# cw-lite-main.net
KiCad netlist of a schematic drawn in EAGLE
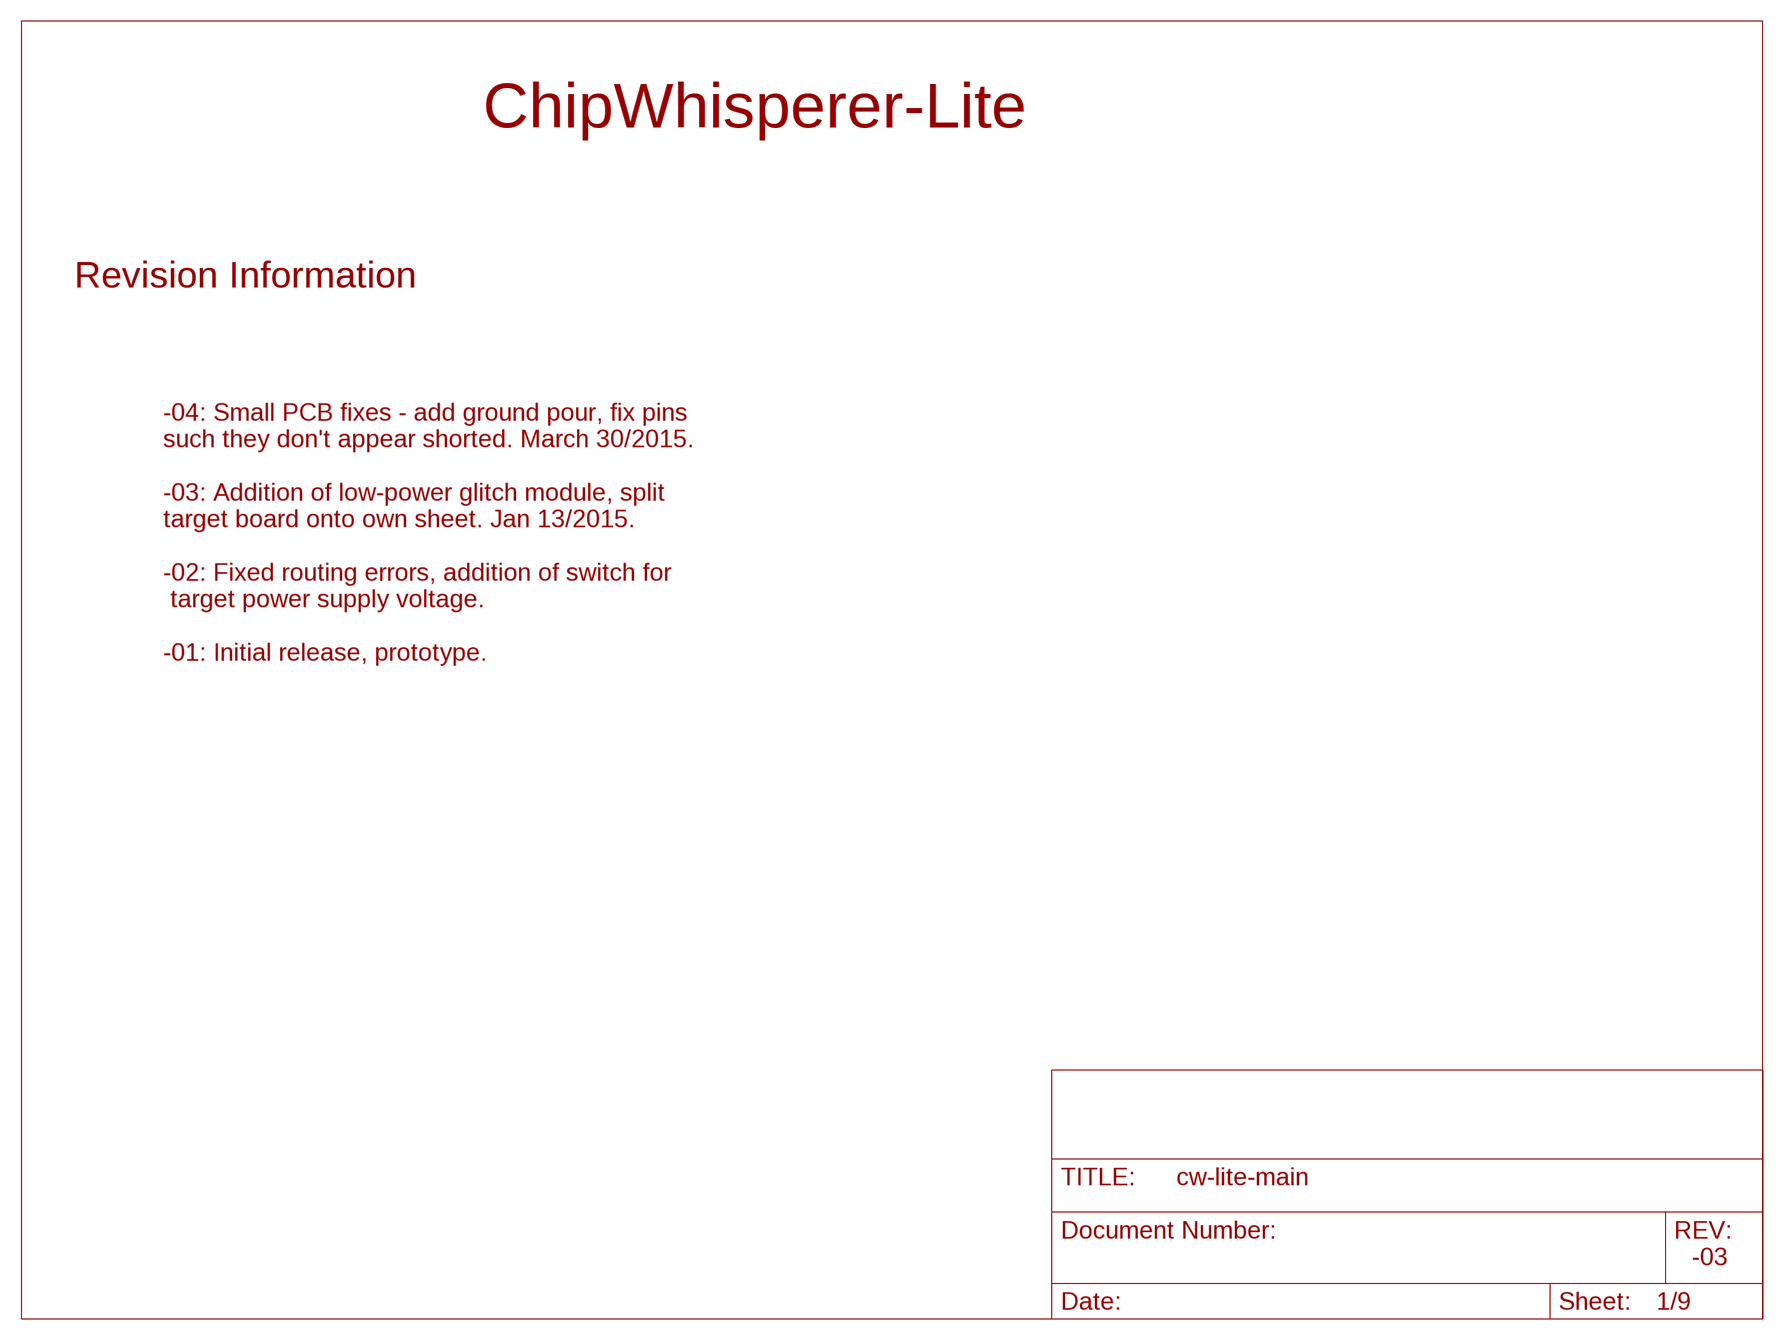
[diagram p0: schematic, sheet 1]
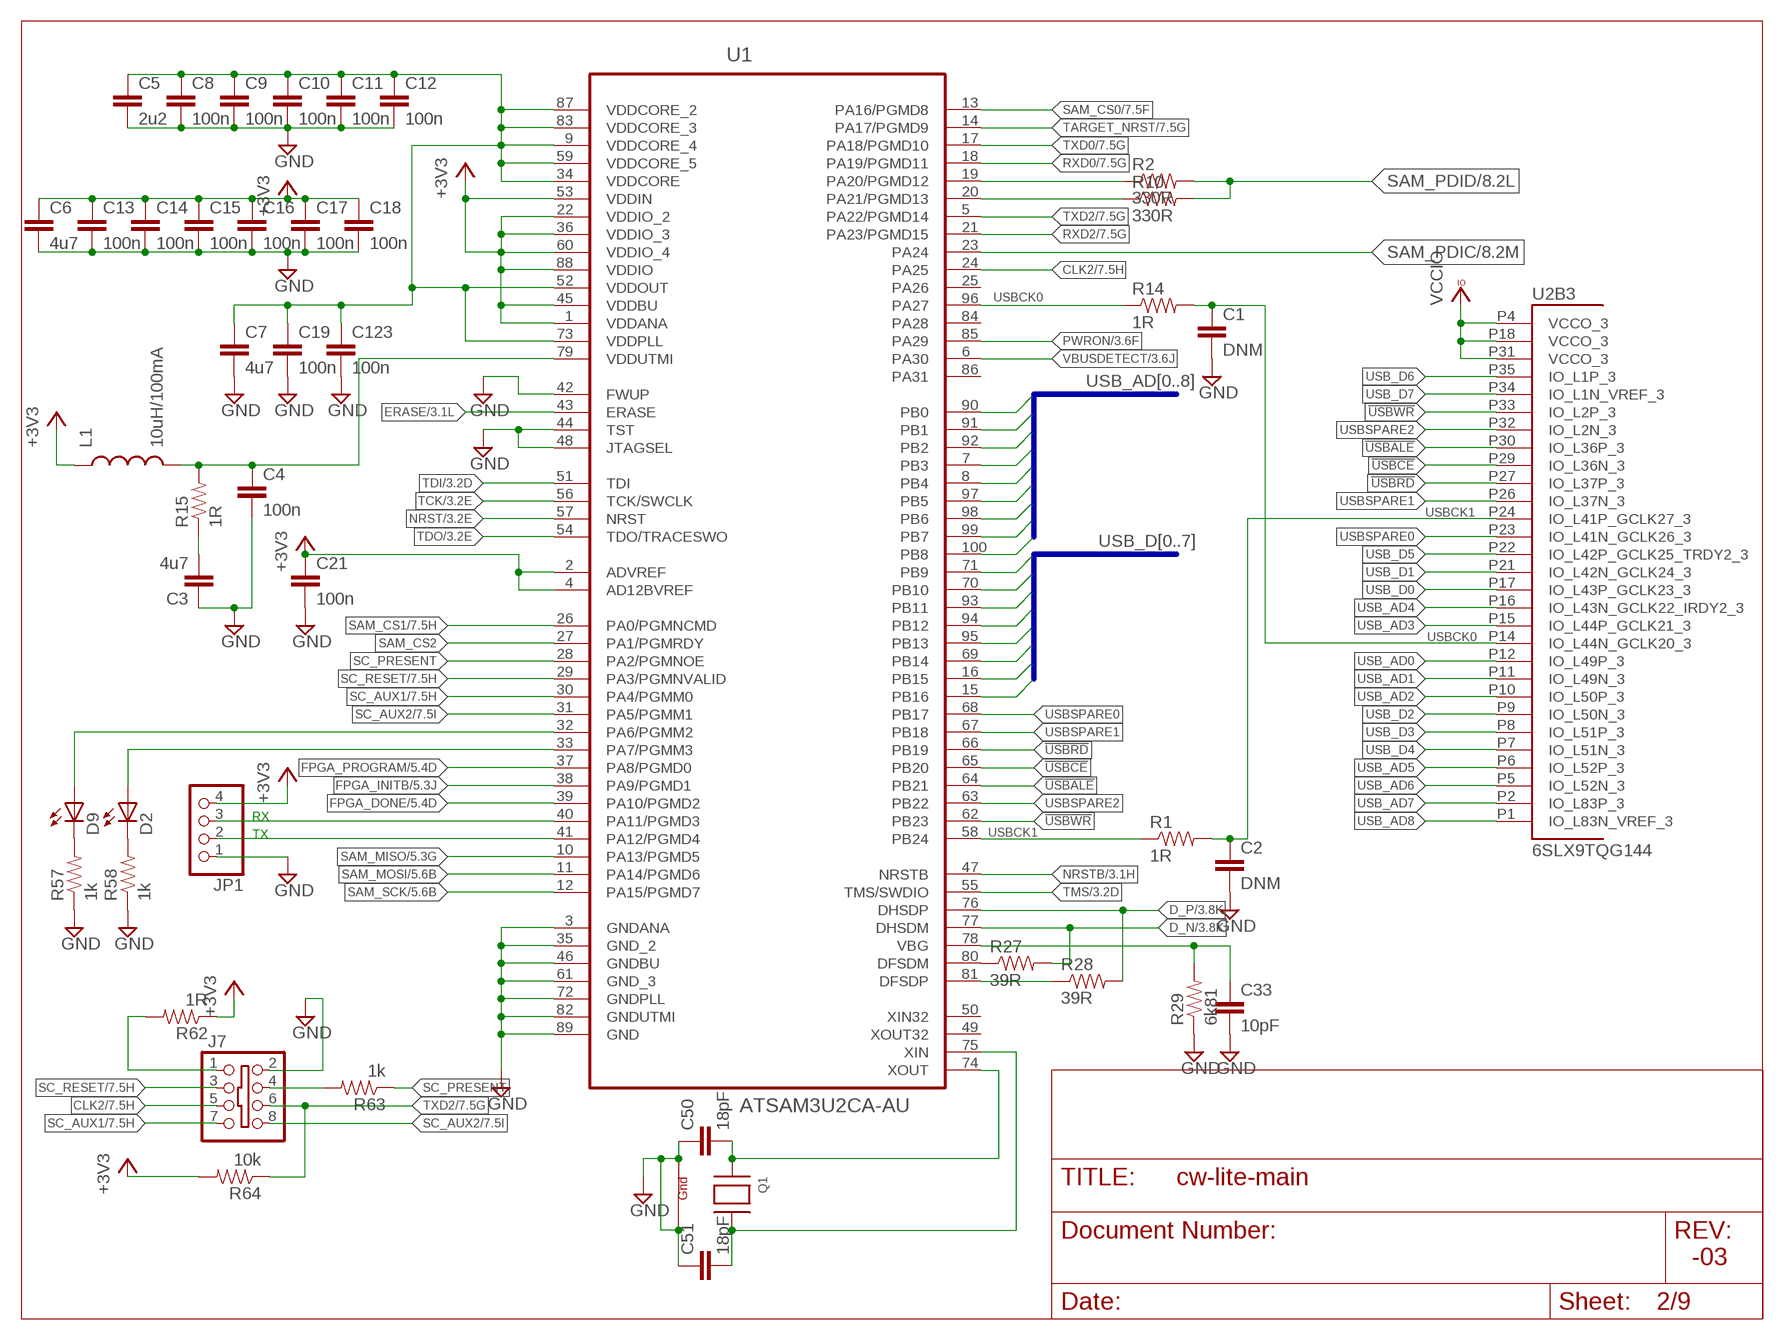
[diagram p1: schematic, sheet 2]
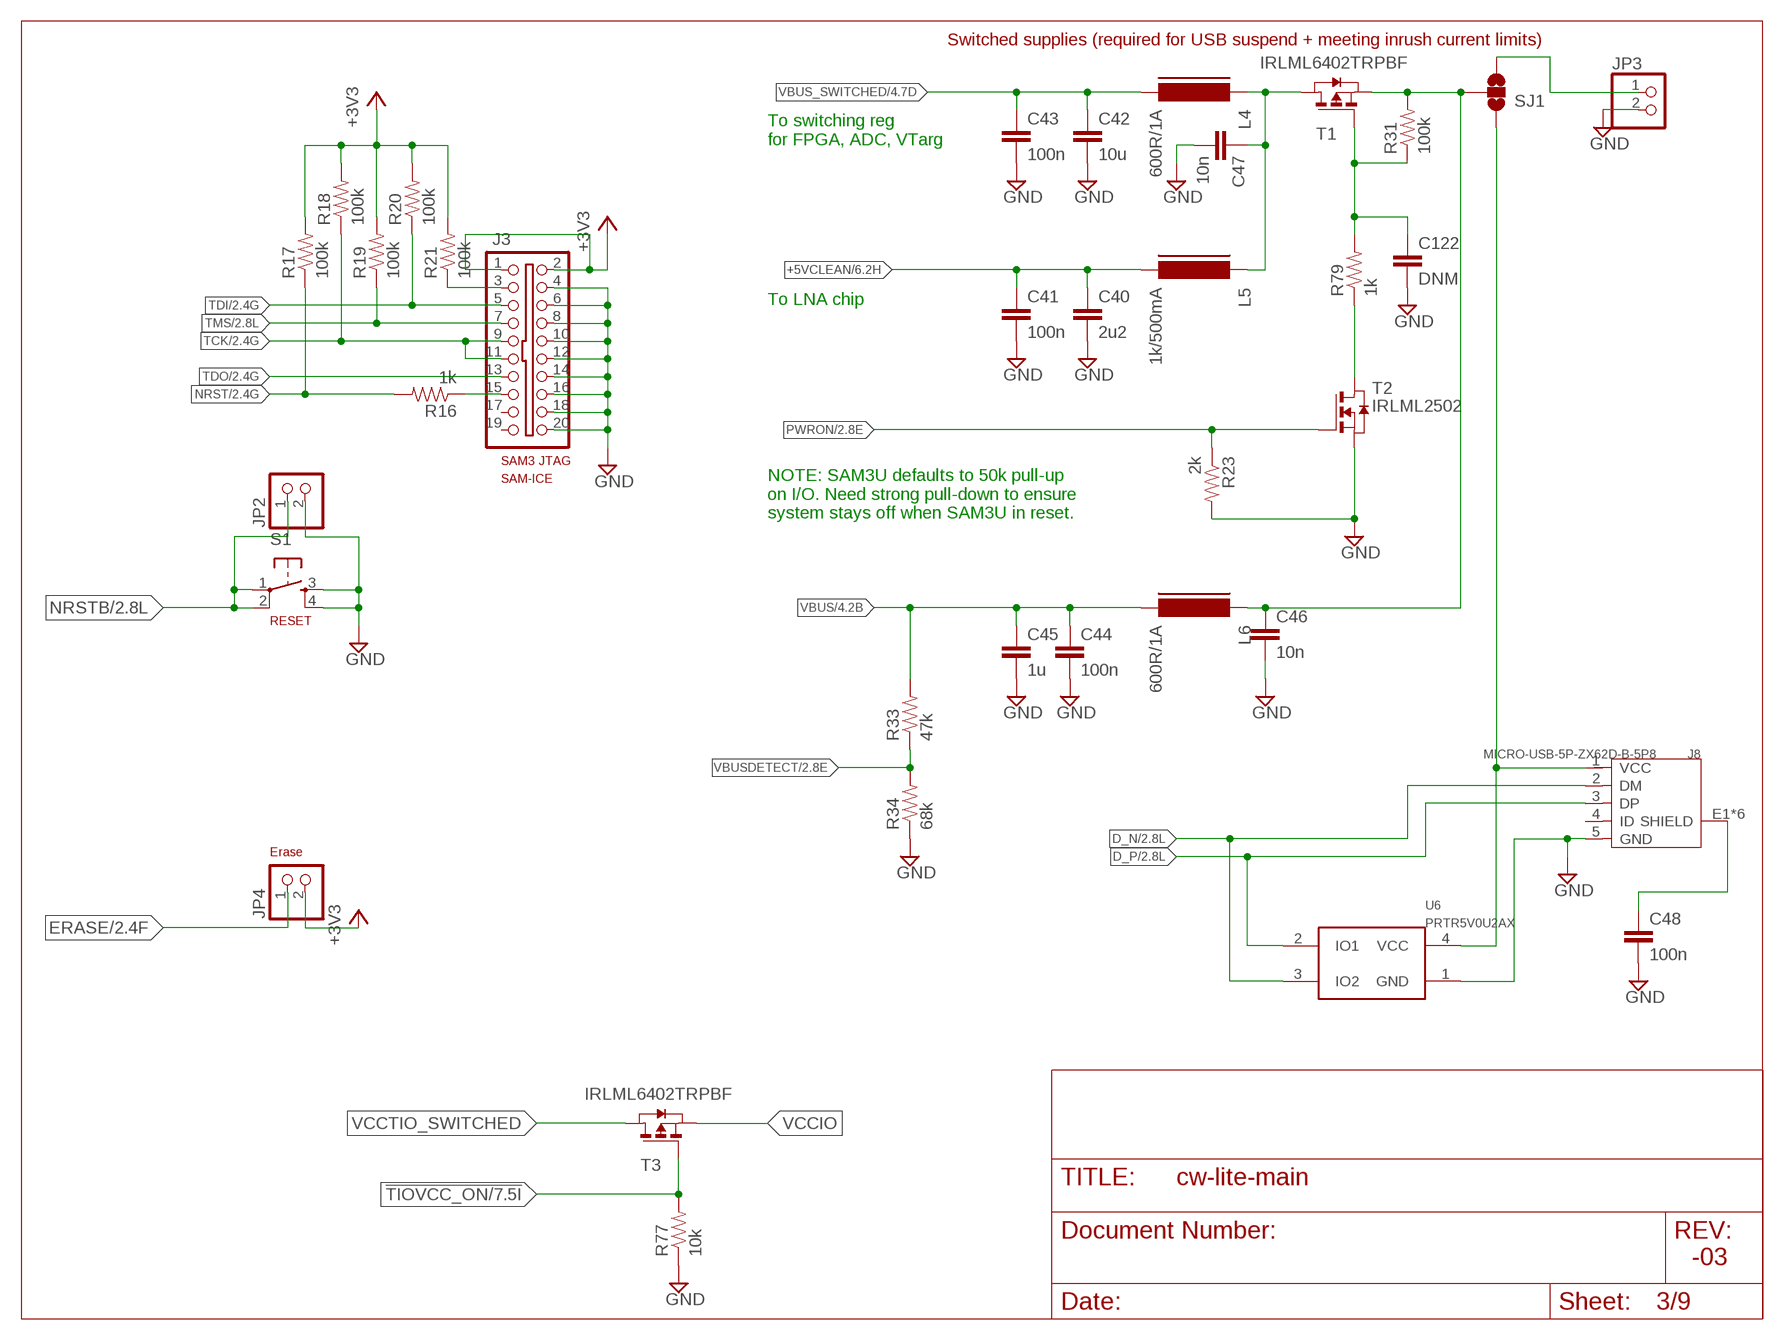
[diagram p2: schematic, sheet 3]
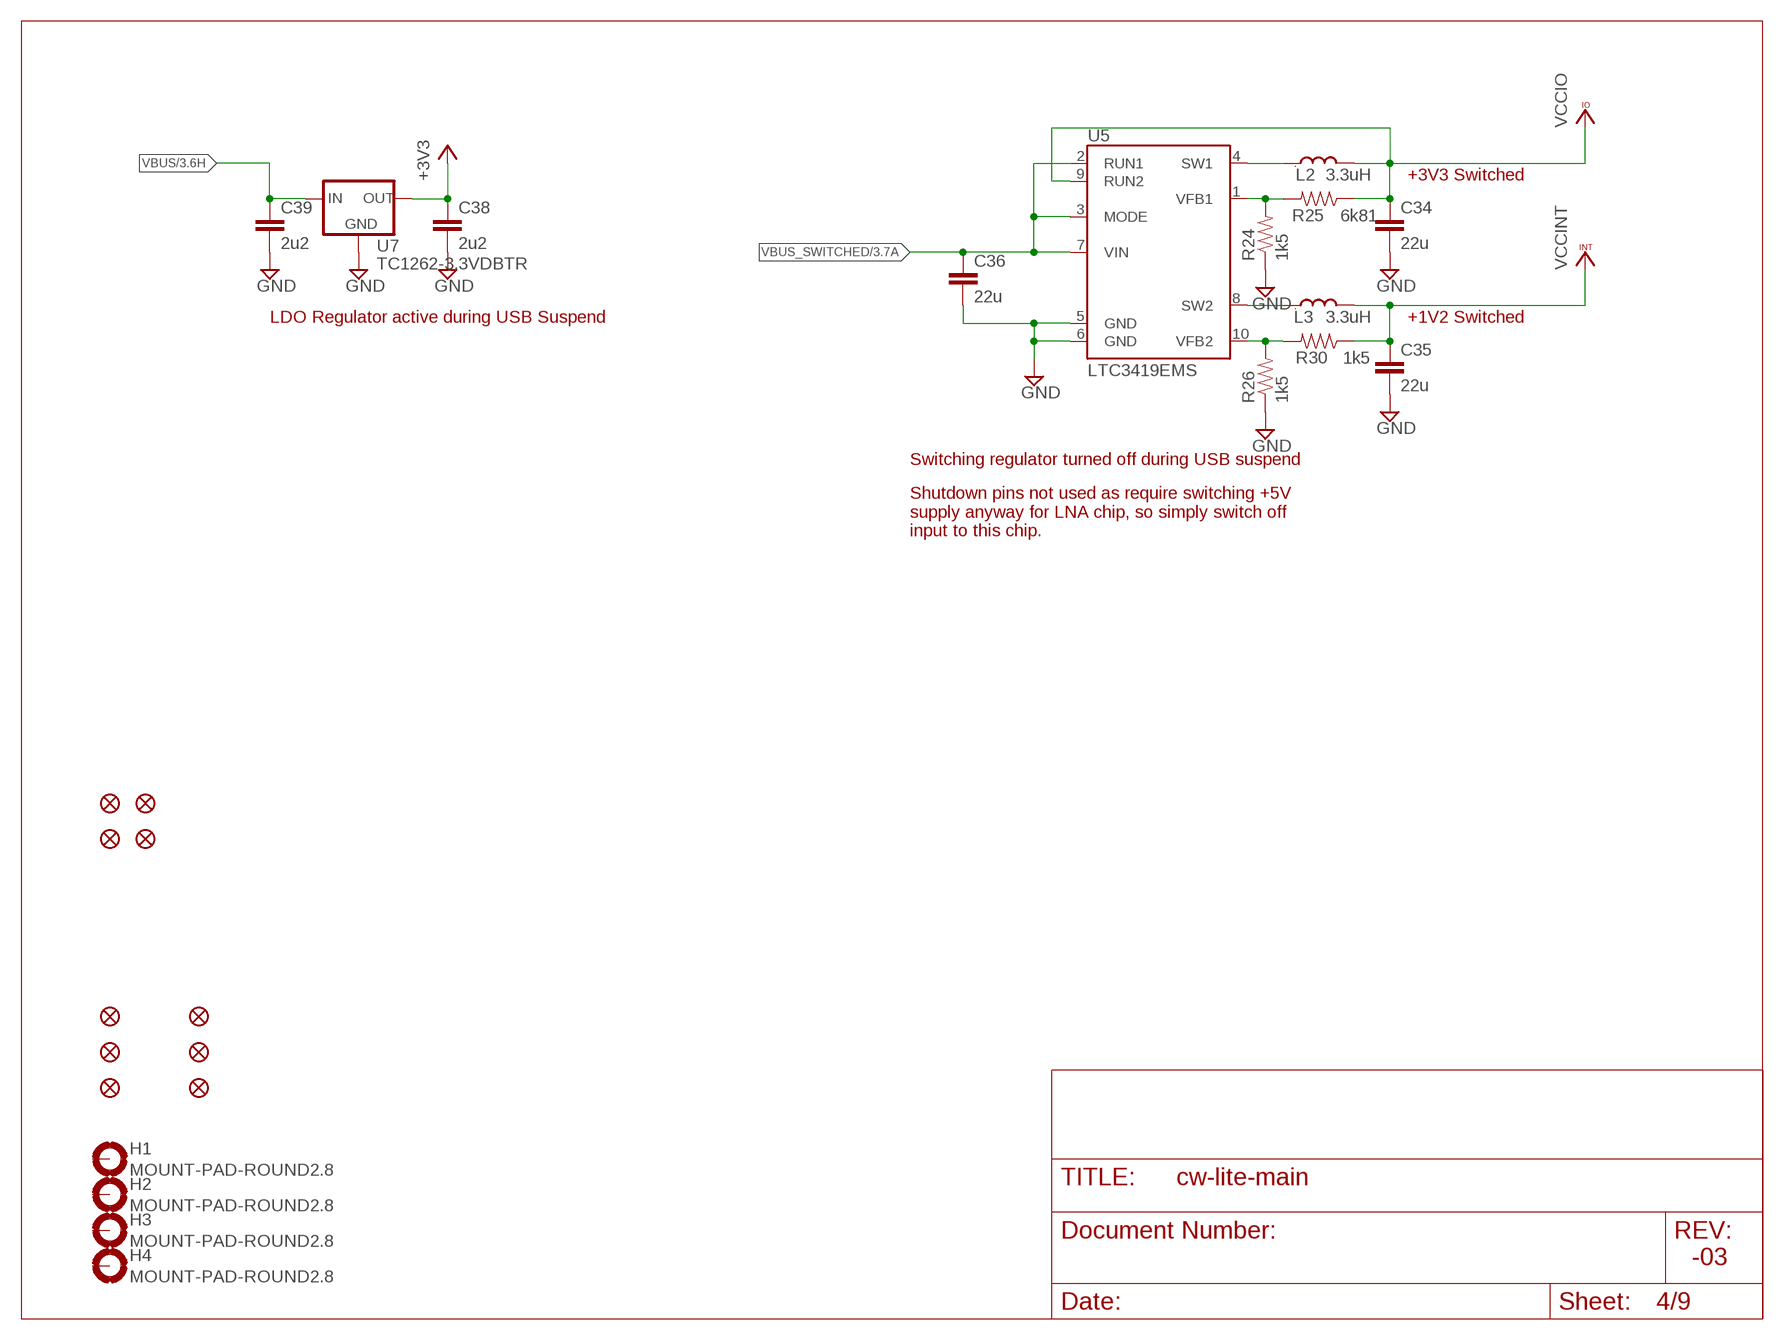
[diagram p3: schematic, sheet 4]
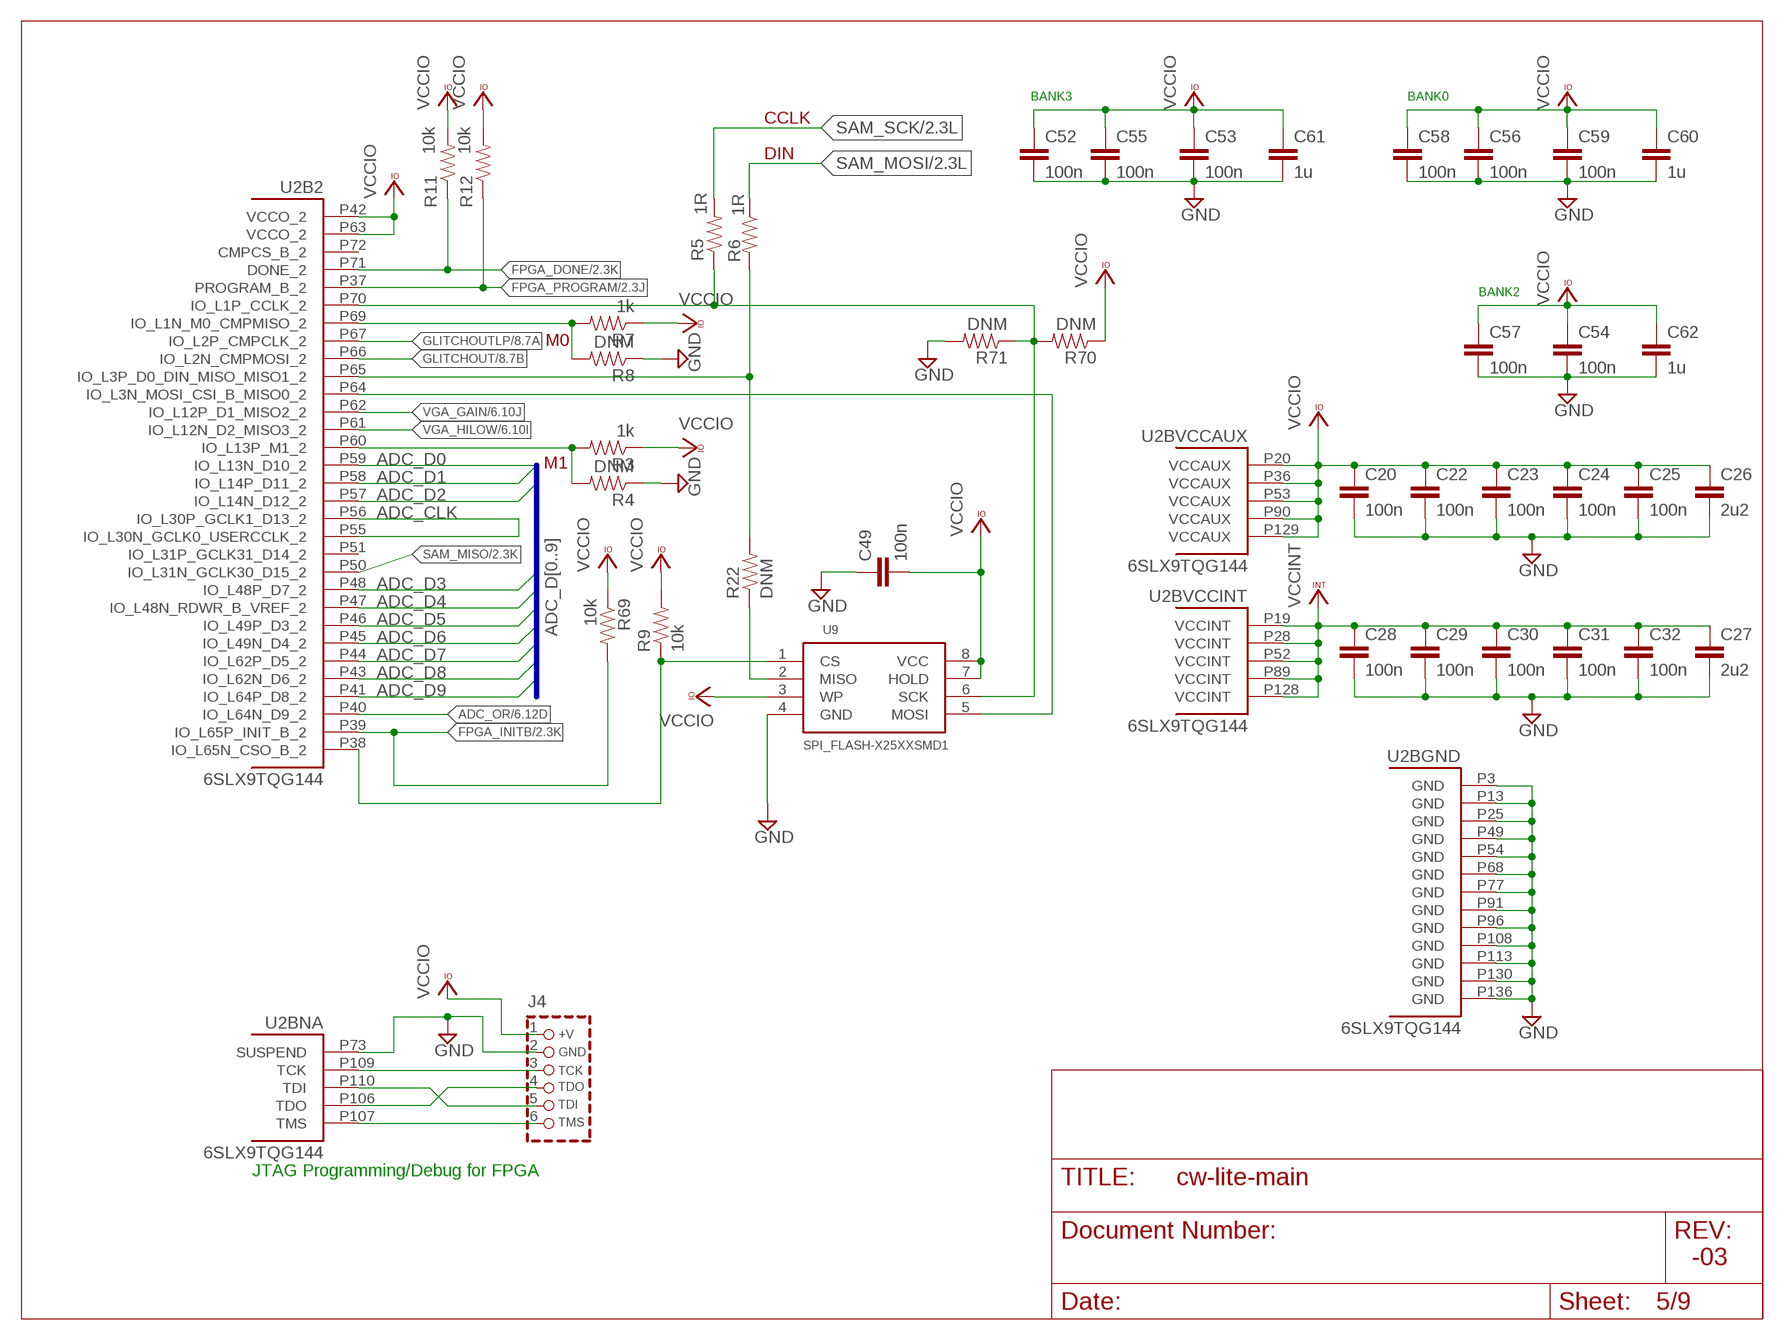
[diagram p4: schematic, sheet 5]
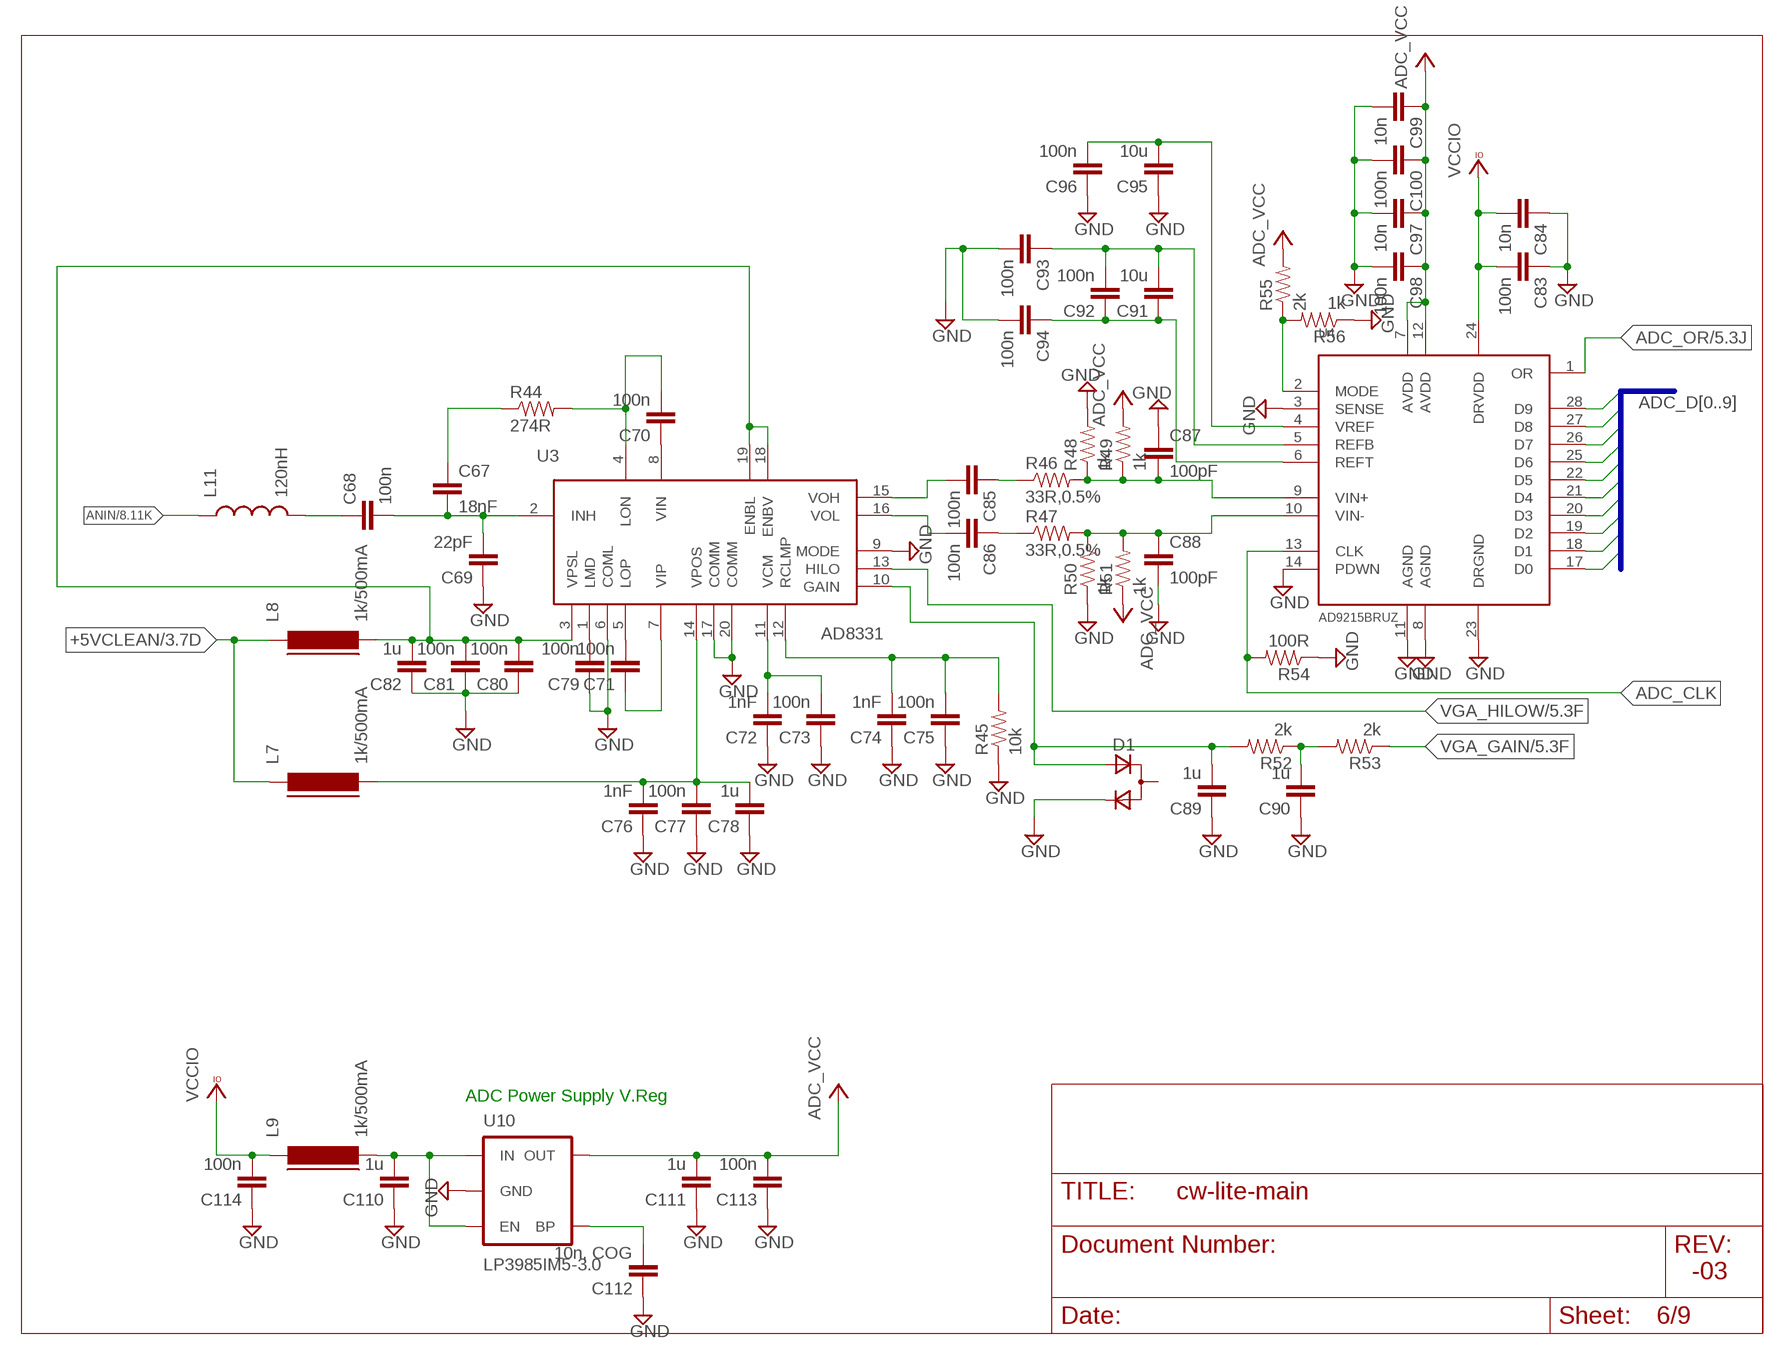
[diagram p5: schematic, sheet 6]
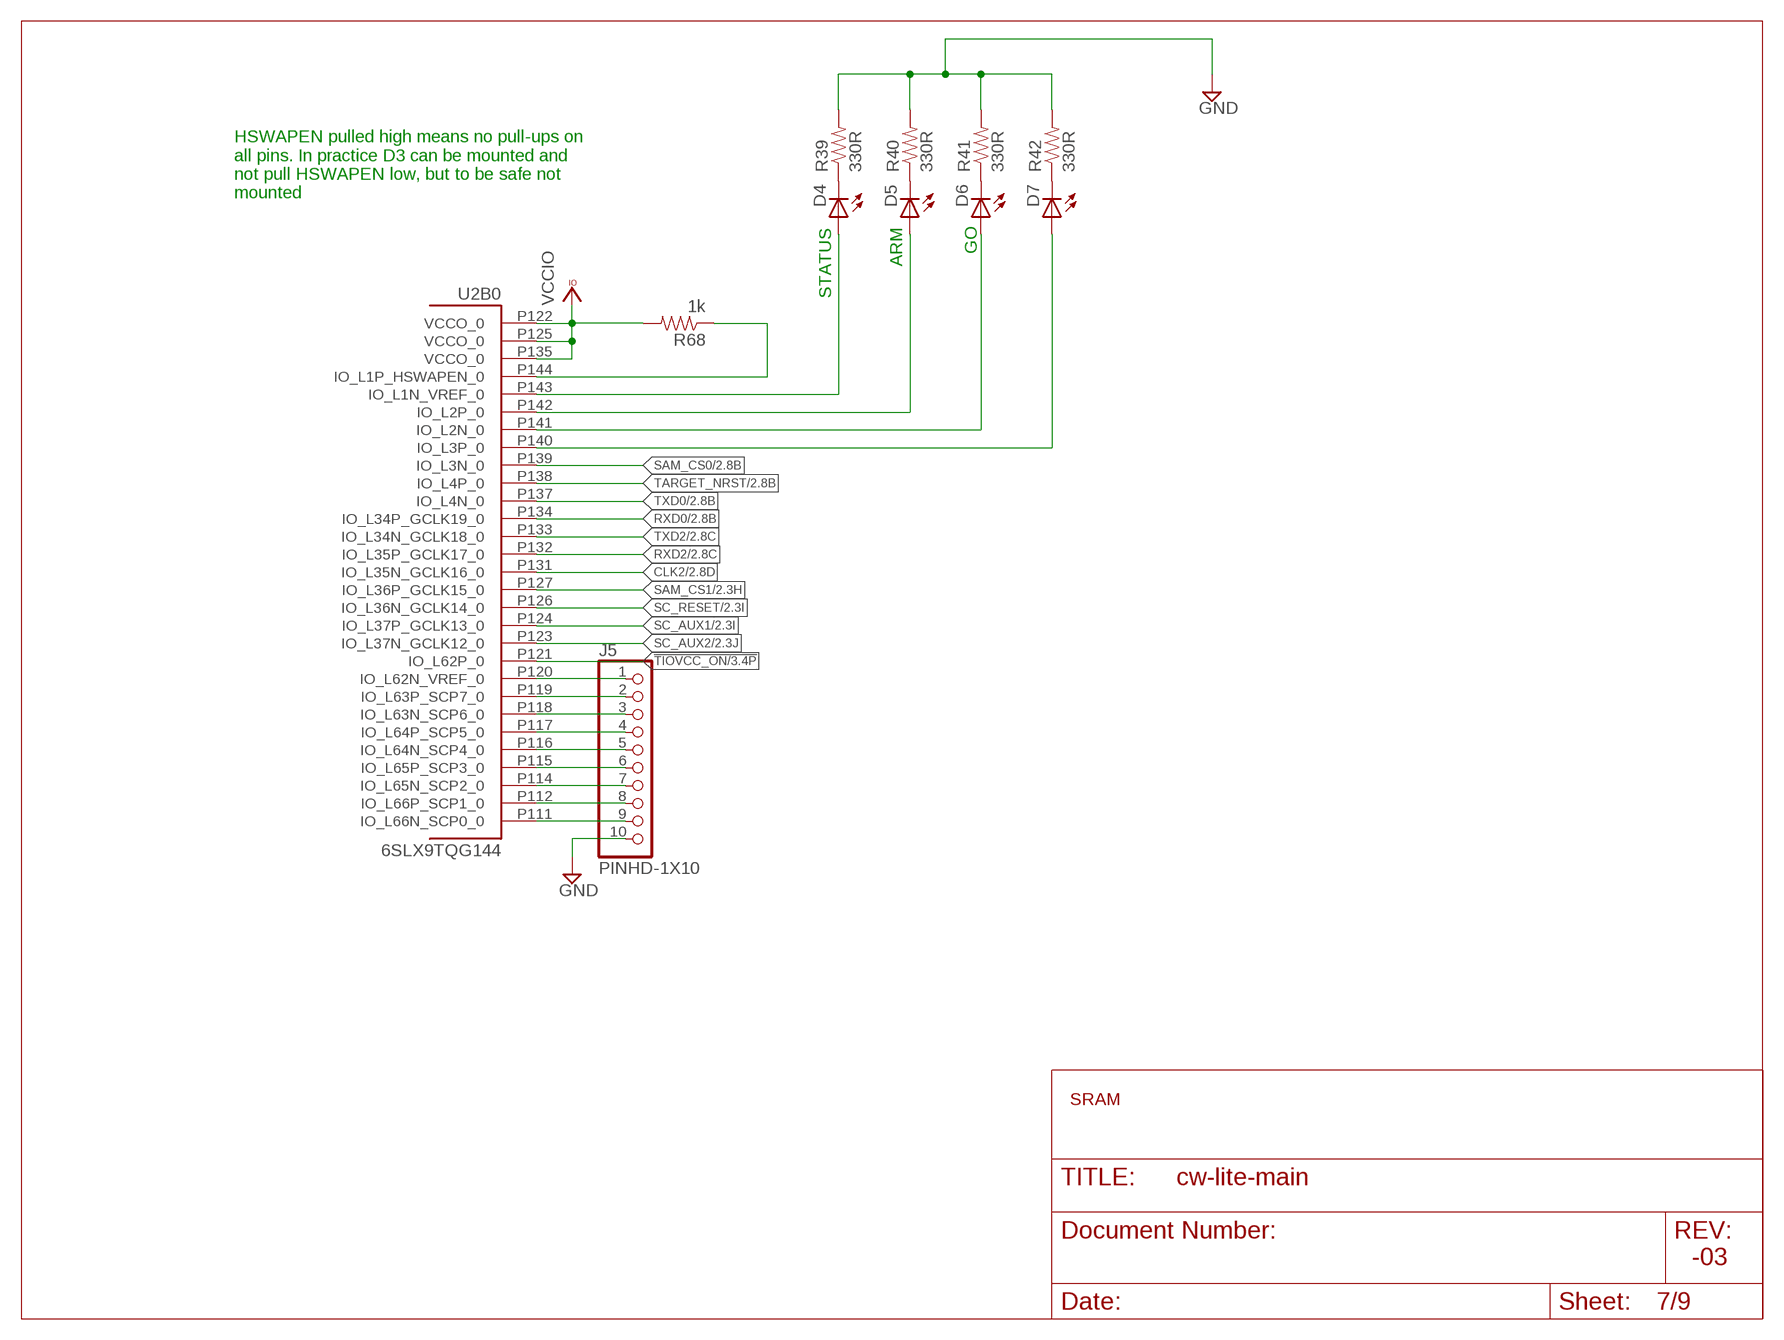
[diagram p6: schematic, sheet 7]
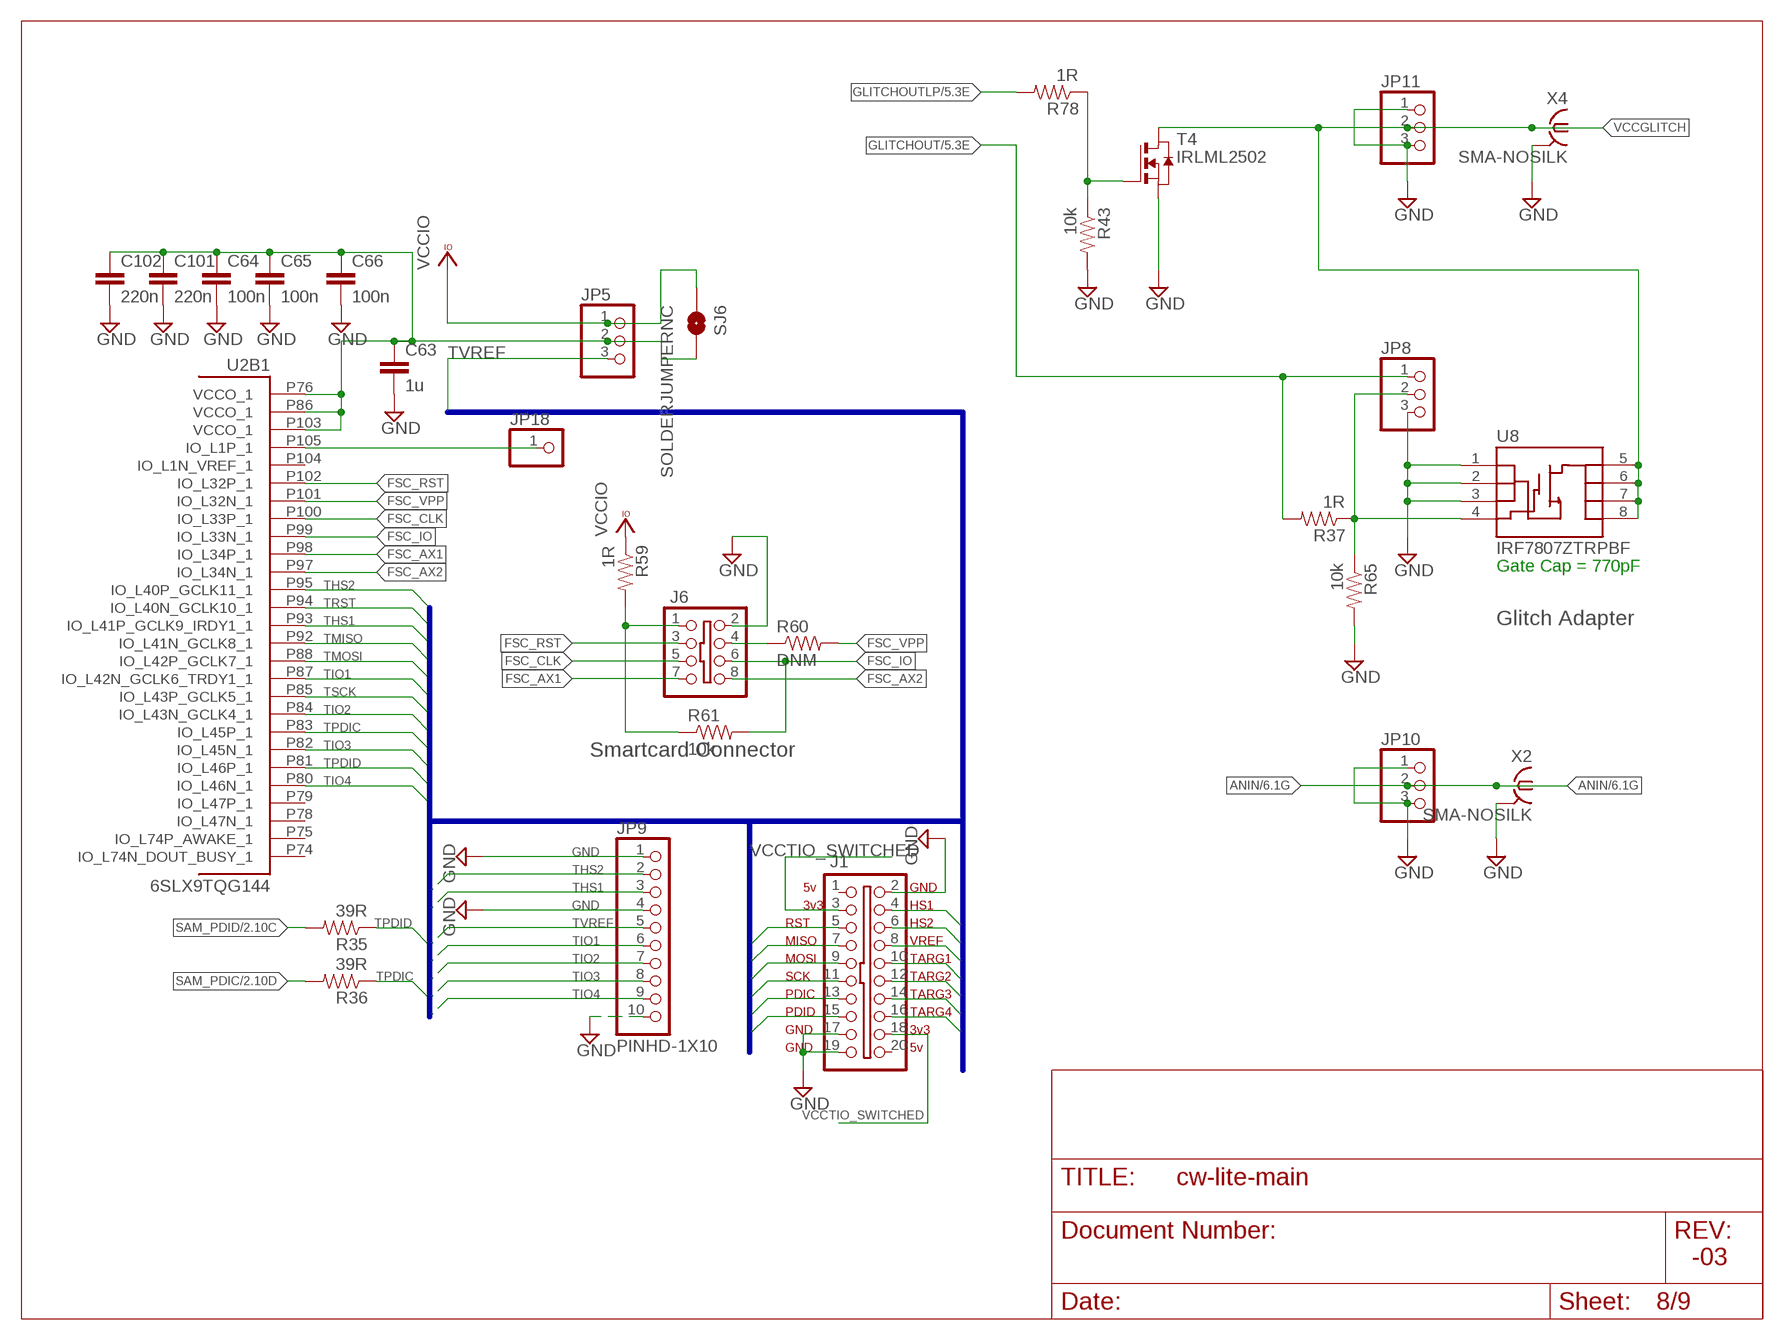
[diagram p7: schematic, sheet 8]
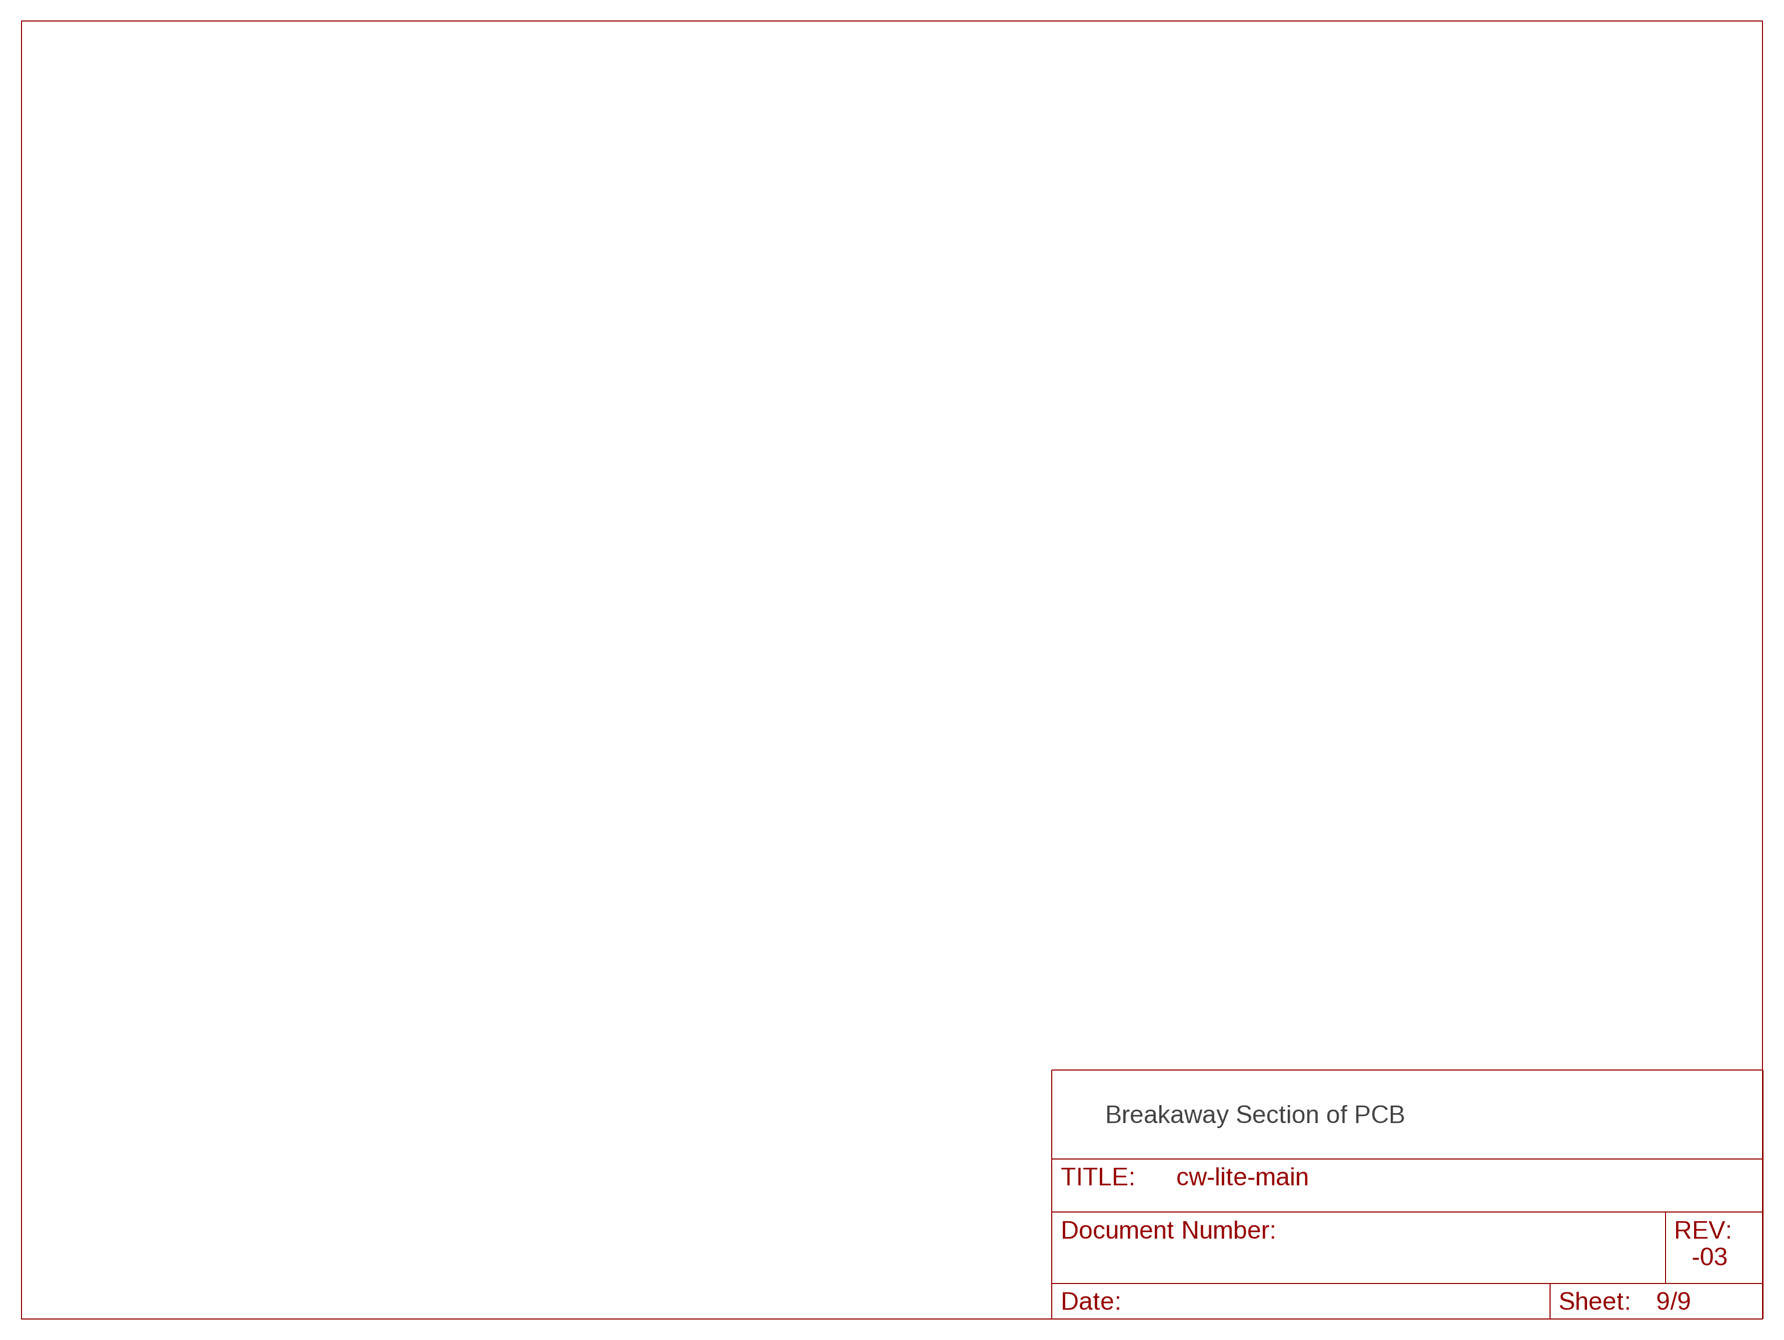
[diagram p8: schematic, sheet 9]

(export (version "E")
  (design (tool "Eeschema 10.0.6"))
  (components
    (comp (ref "C40")
      (value "2u2")
      (footprint "eagle-import:0603C")
      (libsource (lib "eagle-import") (part "custom-std_CAP0603-CAP"))
    )
    (comp (ref "C41")
      (value "100n")
      (footprint "eagle-import:0603C")
      (libsource (lib "eagle-import") (part "custom-std_CAP0603-CAP"))
    )
    (comp (ref "C42")
      (value "10u")
      (footprint "eagle-import:0603C")
      (libsource (lib "eagle-import") (part "custom-std_CAP0603-CAP"))
    )
    (comp (ref "C43")
      (value "100n")
      (footprint "eagle-import:0603C")
      (libsource (lib "eagle-import") (part "custom-std_CAP0603-CAP"))
    )
    (comp (ref "C44")
      (value "100n")
      (footprint "eagle-import:0603C")
      (libsource (lib "eagle-import") (part "custom-std_CAP0603-CAP"))
    )
    (comp (ref "C45")
      (value "1u")
      (footprint "eagle-import:0603C")
      (libsource (lib "eagle-import") (part "custom-std_CAP0603-CAP"))
    )
    (comp (ref "C46")
      (value "10n")
      (footprint "eagle-import:0603C")
      (libsource (lib "eagle-import") (part "custom-std_CAP0603-CAP"))
    )
    (comp (ref "C47")
      (value "10n")
      (footprint "eagle-import:0603C")
      (libsource (lib "eagle-import") (part "custom-std_CAP0603-CAP"))
    )
    (comp (ref "C48")
      (value "100n")
      (footprint "eagle-import:0603C")
      (libsource (lib "eagle-import") (part "custom-std_CAP0603-CAP"))
    )
    (comp (ref "C122")
      (value "DNM")
      (footprint "eagle-import:0603C")
      (libsource (lib "eagle-import") (part "custom-std_CAP0603-CAP"))
    )
    (comp (ref "J3")
      (value "SHROUD_2X10-SHROUDED")
      (footprint "eagle-import:PINSHRD_PTH_2X10")
      (libsource (lib "eagle-import") (part "SHROUD_2X10-SHROUDED"))
    )
    (comp (ref "J8")
      (value "MICRO-USB-5P-ZX62D-B-5P8")
      (footprint "eagle-import:B-SMD-5P-TH")
      (fields (field (name "MPN") "ZX62D-B-5P8") (field (name "OC_DIGIKEY") "H11610CT-ND"))
      (libsource (lib "eagle-import") (part "MICRO-USB-5P-ZX62D-B-5P8"))
    )
    (comp (ref "JP2")
      (value "PINHD-1X2")
      (footprint "eagle-import:1X02")
      (libsource (lib "eagle-import") (part "PINHD-1X2"))
    )
    (comp (ref "JP3")
      (value "PINHD-1X2")
      (footprint "eagle-import:1X02")
      (libsource (lib "eagle-import") (part "PINHD-1X2"))
    )
    (comp (ref "JP4")
      (value "PINHD-1X2")
      (footprint "eagle-import:1X02")
      (libsource (lib "eagle-import") (part "PINHD-1X2"))
    )
    (comp (ref "L4")
      (value "600R/1A")
      (footprint "eagle-import:FB603")
      (libsource (lib "eagle-import") (part "FERRITE-0603"))
    )
    (comp (ref "L5")
      (value "1k/500mA")
      (footprint "eagle-import:FB603")
      (libsource (lib "eagle-import") (part "FERRITE-0603"))
    )
    (comp (ref "L6")
      (value "600R/1A")
      (footprint "eagle-import:FB603")
      (libsource (lib "eagle-import") (part "FERRITE-0603"))
    )
    (comp (ref "R16")
      (value "1k")
      (footprint "eagle-import:0402R")
      (libsource (lib "eagle-import") (part "RES0402-RES"))
    )
    (comp (ref "R17")
      (value "100k")
      (footprint "eagle-import:0402R")
      (libsource (lib "eagle-import") (part "RES0402-RES"))
    )
    (comp (ref "R18")
      (value "100k")
      (footprint "eagle-import:0402R")
      (libsource (lib "eagle-import") (part "RES0402-RES"))
    )
    (comp (ref "R19")
      (value "100k")
      (footprint "eagle-import:0402R")
      (libsource (lib "eagle-import") (part "RES0402-RES"))
    )
    (comp (ref "R20")
      (value "100k")
      (footprint "eagle-import:0402R")
      (libsource (lib "eagle-import") (part "RES0402-RES"))
    )
    (comp (ref "R21")
      (value "100k")
      (footprint "eagle-import:0402R")
      (libsource (lib "eagle-import") (part "RES0402-RES"))
    )
    (comp (ref "R23")
      (value "2k")
      (footprint "eagle-import:0603R")
      (libsource (lib "eagle-import") (part "custom-std_RES0603-RES"))
    )
    (comp (ref "R31")
      (value "100k")
      (footprint "eagle-import:0402R")
      (libsource (lib "eagle-import") (part "custom-std_RES0402-RES"))
    )
    (comp (ref "R33")
      (value "47k")
      (footprint "eagle-import:0402R")
      (libsource (lib "eagle-import") (part "custom-std_RES0402-RES"))
    )
    (comp (ref "R34")
      (value "68k")
      (footprint "eagle-import:0402R")
      (libsource (lib "eagle-import") (part "custom-std_RES0402-RES"))
    )
    (comp (ref "R77")
      (value "10k")
      (footprint "eagle-import:0402R")
      (libsource (lib "eagle-import") (part "custom-std_RES0402-RES"))
    )
    (comp (ref "R79")
      (value "1k")
      (footprint "eagle-import:0603R")
      (libsource (lib "eagle-import") (part "custom-std_RES0603-RES"))
    )
    (comp (ref "S1")
      (value "TAC_SWITCHSMD")
      (footprint "eagle-import:TACTILE_SWITCH_SMD")
      (libsource (lib "eagle-import") (part "TAC_SWITCHSMD"))
    )
    (comp (ref "SJ1")
      (value "SOLDERJUMPER_2WAYPASTE1&2")
      (footprint "eagle-import:SJ_3_PASTE1&2")
      (libsource (lib "eagle-import") (part "SOLDERJUMPER_2WAYPASTE1&2"))
    )
    (comp (ref "T1")
      (value "IRLML6402TRPBF")
      (footprint "eagle-import:SOT-23")
      (fields (field (name "MPN") "IRLML6402TRPBF") (field (name "OC_DIGIKEY") "IRLML6402PBFCT-ND"))
      (libsource (lib "eagle-import") (part "PMOSSOT23"))
    )
    (comp (ref "T2")
      (value "IRLML2502")
      (footprint "eagle-import:SOT-23")
      (fields (field (name "MPN") "IRLML2502TRPBF") (field (name "OC_DIGIKEY") "IRLML2502PBFCT-ND"))
      (libsource (lib "eagle-import") (part "NMOSSOT23"))
    )
    (comp (ref "T3")
      (value "IRLML6402TRPBF")
      (footprint "eagle-import:SOT-23")
      (fields (field (name "MPN") "IRLML6402TRPBF") (field (name "OC_DIGIKEY") "IRLML6402PBFCT-ND"))
      (libsource (lib "eagle-import") (part "PMOSSOT23"))
    )
    (comp (ref "U6")
      (value "PRTR5V0U2AX")
      (footprint "eagle-import:SOT143B")
      (fields (field (name "MPN") "PRTR5V0U2AX,215") (field (name "OC_DIGIKEY") "568-4139-1-ND"))
      (libsource (lib "eagle-import") (part "PRTR5V0U2AX"))
    )
    (comp (ref "C1")
      (value "DNM")
      (footprint "eagle-import:0402C")
      (libsource (lib "eagle-import") (part "CAP0402-CAP"))
    )
    (comp (ref "C2")
      (value "DNM")
      (footprint "eagle-import:0402C")
      (libsource (lib "eagle-import") (part "CAP0402-CAP"))
    )
    (comp (ref "C3")
      (value "4u7")
      (footprint "eagle-import:0603C")
      (libsource (lib "eagle-import") (part "CAP0603-CAP"))
    )
    (comp (ref "C4")
      (value "100n")
      (footprint "eagle-import:0402C")
      (libsource (lib "eagle-import") (part "CAP0402-CAP"))
    )
    (comp (ref "C5")
      (value "2u2")
      (footprint "eagle-import:0603C")
      (libsource (lib "eagle-import") (part "CAP0603-CAP"))
    )
    (comp (ref "C6")
      (value "4u7")
      (footprint "eagle-import:0603C")
      (libsource (lib "eagle-import") (part "CAP0603-CAP"))
    )
    (comp (ref "C7")
      (value "4u7")
      (footprint "eagle-import:0603C")
      (libsource (lib "eagle-import") (part "CAP0603-CAP"))
    )
    (comp (ref "C8")
      (value "100n")
      (footprint "eagle-import:0402C")
      (libsource (lib "eagle-import") (part "CAP0402-CAP"))
    )
    (comp (ref "C9")
      (value "100n")
      (footprint "eagle-import:0402C")
      (libsource (lib "eagle-import") (part "CAP0402-CAP"))
    )
    (comp (ref "C10")
      (value "100n")
      (footprint "eagle-import:0402C")
      (libsource (lib "eagle-import") (part "CAP0402-CAP"))
    )
    (comp (ref "C11")
      (value "100n")
      (footprint "eagle-import:0402C")
      (libsource (lib "eagle-import") (part "CAP0402-CAP"))
    )
    (comp (ref "C12")
      (value "100n")
      (footprint "eagle-import:0402C")
      (libsource (lib "eagle-import") (part "CAP0402-CAP"))
    )
    (comp (ref "C13")
      (value "100n")
      (footprint "eagle-import:0402C")
      (libsource (lib "eagle-import") (part "CAP0402-CAP"))
    )
    (comp (ref "C14")
      (value "100n")
      (footprint "eagle-import:0402C")
      (libsource (lib "eagle-import") (part "CAP0402-CAP"))
    )
    (comp (ref "C15")
      (value "100n")
      (footprint "eagle-import:0402C")
      (libsource (lib "eagle-import") (part "CAP0402-CAP"))
    )
    (comp (ref "C16")
      (value "100n")
      (footprint "eagle-import:0402C")
      (libsource (lib "eagle-import") (part "CAP0402-CAP"))
    )
    (comp (ref "C17")
      (value "100n")
      (footprint "eagle-import:0402C")
      (libsource (lib "eagle-import") (part "CAP0402-CAP"))
    )
    (comp (ref "C18")
      (value "100n")
      (footprint "eagle-import:0402C")
      (libsource (lib "eagle-import") (part "CAP0402-CAP"))
    )
    (comp (ref "C19")
      (value "100n")
      (footprint "eagle-import:0402C")
      (libsource (lib "eagle-import") (part "CAP0402-CAP"))
    )
    (comp (ref "C21")
      (value "100n")
      (footprint "eagle-import:0402C")
      (libsource (lib "eagle-import") (part "CAP0402-CAP"))
    )
    (comp (ref "C33")
      (value "10pF")
      (footprint "eagle-import:0603C")
      (libsource (lib "eagle-import") (part "CAP0603-CAP"))
    )
    (comp (ref "C50")
      (value "18pF")
      (footprint "eagle-import:0402C")
      (libsource (lib "eagle-import") (part "CAP0402-CAP"))
    )
    (comp (ref "C51")
      (value "18pF")
      (footprint "eagle-import:0402C")
      (libsource (lib "eagle-import") (part "CAP0402-CAP"))
    )
    (comp (ref "C123")
      (value "100n")
      (footprint "eagle-import:0402C")
      (libsource (lib "eagle-import") (part "CAP0402-CAP"))
    )
    (comp (ref "D2")
      (value "LED0603")
      (footprint "eagle-import:LED-0603")
      (libsource (lib "eagle-import") (part "LED0603"))
    )
    (comp (ref "D9")
      (value "LED0603")
      (footprint "eagle-import:LED-0603")
      (libsource (lib "eagle-import") (part "LED0603"))
    )
    (comp (ref "J7")
      (value "SHROUD_2X4EDGE")
      (footprint "eagle-import:PINSHRD_EDGE_2X04.PAC")
      (libsource (lib "eagle-import") (part "SHROUD_2X4EDGE"))
    )
    (comp (ref "JP1")
      (value "PINHD-1X4")
      (footprint "eagle-import:1X04")
      (libsource (lib "eagle-import") (part "PINHD-1X4"))
    )
    (comp (ref "L1")
      (value "10uH/100mA")
      (footprint "eagle-import:0603")
      (libsource (lib "eagle-import") (part "INDUCTOR0603"))
    )
    (comp (ref "Q1")
      (value "XTAL-4ABM8G")
      (footprint "eagle-import:NX3225")
      (fields (field (name "MPN") "ABM8G-12.000MHZ-4Y-T3") (field (name "OC_DIGIKEY") "535-10901-1-ND"))
      (libsource (lib "eagle-import") (part "XTAL-4ABM8G"))
    )
    (comp (ref "R1")
      (value "1R")
      (footprint "eagle-import:0402R")
      (libsource (lib "eagle-import") (part "RES0402-RES"))
    )
    (comp (ref "R2")
      (value "330R")
      (footprint "eagle-import:0402R")
      (libsource (lib "eagle-import") (part "RES0402-RES"))
    )
    (comp (ref "R10")
      (value "330R")
      (footprint "eagle-import:0402R")
      (libsource (lib "eagle-import") (part "RES0402-RES"))
    )
    (comp (ref "R14")
      (value "1R")
      (footprint "eagle-import:0402R")
      (libsource (lib "eagle-import") (part "RES0402-RES"))
    )
    (comp (ref "R15")
      (value "1R")
      (footprint "eagle-import:0603R")
      (libsource (lib "eagle-import") (part "RES0603-RES"))
    )
    (comp (ref "R27")
      (value "39R")
      (footprint "eagle-import:0603R")
      (libsource (lib "eagle-import") (part "RES0603-RES"))
    )
    (comp (ref "R28")
      (value "39R")
      (footprint "eagle-import:0603R")
      (libsource (lib "eagle-import") (part "RES0603-RES"))
    )
    (comp (ref "R29")
      (value "6k81")
      (footprint "eagle-import:0402R")
      (libsource (lib "eagle-import") (part "RES0402-RES"))
    )
    (comp (ref "R57")
      (value "1k")
      (footprint "eagle-import:0603R")
      (libsource (lib "eagle-import") (part "RES0603-RES"))
    )
    (comp (ref "R58")
      (value "1k")
      (footprint "eagle-import:0603R")
      (libsource (lib "eagle-import") (part "RES0603-RES"))
    )
    (comp (ref "R62")
      (value "1R")
      (footprint "eagle-import:0603R")
      (libsource (lib "eagle-import") (part "RES0603-RES"))
    )
    (comp (ref "R63")
      (value "1k")
      (footprint "eagle-import:0603R")
      (libsource (lib "eagle-import") (part "RES0603-RES"))
    )
    (comp (ref "R64")
      (value "10k")
      (footprint "eagle-import:0603R")
      (libsource (lib "eagle-import") (part "RES0603-RES"))
    )
    (comp (ref "U1")
      (value "ATSAM3U2CA-AU")
      (footprint "eagle-import:QFP50P1600X1600X160-100N")
      (fields (field (name "OC_DIGIKEY") "ATSAM3U2CA-AU-ND"))
      (libsource (lib "eagle-import") (part "ATSAM3U2CA-AU"))
    )
    (comp (ref "U2")
      (value "6SLX9TQG144")
      (footprint "eagle-import:TQ144")
      (fields (field (name "MPN") "XC6SLX9-3TQG144C") (field (name "OC_DIGIKEY") "122-1748-ND"))
      (libsource (lib "eagle-import") (part "6SLX9TQG144"))
    )
    (comp (ref "C67")
      (value "18nF")
      (footprint "eagle-import:0603C")
      (libsource (lib "eagle-import") (part "custom-std_CAP0603-CAP"))
    )
    (comp (ref "C68")
      (value "100n")
      (footprint "eagle-import:0603C")
      (libsource (lib "eagle-import") (part "custom-std_CAP0603-CAP"))
    )
    (comp (ref "C69")
      (value "22pF")
      (footprint "eagle-import:0603C")
      (libsource (lib "eagle-import") (part "custom-std_CAP0603-CAP"))
    )
    (comp (ref "C70")
      (value "100n")
      (footprint "eagle-import:0402C")
      (libsource (lib "eagle-import") (part "custom-std_CAP0402-CAP"))
    )
    (comp (ref "C71")
      (value "100n")
      (footprint "eagle-import:0402C")
      (libsource (lib "eagle-import") (part "custom-std_CAP0402-CAP"))
    )
    (comp (ref "C72")
      (value "1nF")
      (footprint "eagle-import:0402C")
      (libsource (lib "eagle-import") (part "custom-std_CAP0402-CAP"))
    )
    (comp (ref "C73")
      (value "100n")
      (footprint "eagle-import:0402C")
      (libsource (lib "eagle-import") (part "custom-std_CAP0402-CAP"))
    )
    (comp (ref "C74")
      (value "1nF")
      (footprint "eagle-import:0402C")
      (libsource (lib "eagle-import") (part "custom-std_CAP0402-CAP"))
    )
    (comp (ref "C75")
      (value "100n")
      (footprint "eagle-import:0402C")
      (libsource (lib "eagle-import") (part "custom-std_CAP0402-CAP"))
    )
    (comp (ref "C76")
      (value "1nF")
      (footprint "eagle-import:0402C")
      (libsource (lib "eagle-import") (part "custom-std_CAP0402-CAP"))
    )
    (comp (ref "C77")
      (value "100n")
      (footprint "eagle-import:0402C")
      (libsource (lib "eagle-import") (part "custom-std_CAP0402-CAP"))
    )
    (comp (ref "C78")
      (value "1u")
      (footprint "eagle-import:0603C")
      (libsource (lib "eagle-import") (part "custom-std_CAP0603-CAP"))
    )
    (comp (ref "C79")
      (value "100n")
      (footprint "eagle-import:0402C")
      (libsource (lib "eagle-import") (part "custom-std_CAP0402-CAP"))
    )
    (comp (ref "C80")
      (value "100n")
      (footprint "eagle-import:0402C")
      (libsource (lib "eagle-import") (part "custom-std_CAP0402-CAP"))
    )
    (comp (ref "C81")
      (value "100n")
      (footprint "eagle-import:0402C")
      (libsource (lib "eagle-import") (part "custom-std_CAP0402-CAP"))
    )
    (comp (ref "C82")
      (value "1u")
      (footprint "eagle-import:0603C")
      (libsource (lib "eagle-import") (part "custom-std_CAP0603-CAP"))
    )
    (comp (ref "C83")
      (value "100n")
      (footprint "eagle-import:0402C")
      (libsource (lib "eagle-import") (part "custom-std_CAP0402-CAP"))
    )
    (comp (ref "C84")
      (value "10n")
      (footprint "eagle-import:0402C")
      (libsource (lib "eagle-import") (part "custom-std_CAP0402-CAP"))
    )
    (comp (ref "C85")
      (value "100n")
      (footprint "eagle-import:0603C")
      (libsource (lib "eagle-import") (part "custom-std_CAP0603-CAP"))
    )
    (comp (ref "C86")
      (value "100n")
      (footprint "eagle-import:0603C")
      (libsource (lib "eagle-import") (part "custom-std_CAP0603-CAP"))
    )
    (comp (ref "C87")
      (value "100pF")
      (footprint "eagle-import:0603C")
      (libsource (lib "eagle-import") (part "custom-std_CAP0603-CAP"))
    )
    (comp (ref "C88")
      (value "100pF")
      (footprint "eagle-import:0603C")
      (libsource (lib "eagle-import") (part "custom-std_CAP0603-CAP"))
    )
    (comp (ref "C89")
      (value "1u")
      (footprint "eagle-import:0603C")
      (libsource (lib "eagle-import") (part "custom-std_CAP0603-CAP"))
    )
    (comp (ref "C90")
      (value "1u")
      (footprint "eagle-import:0603C")
      (libsource (lib "eagle-import") (part "custom-std_CAP0603-CAP"))
    )
    (comp (ref "C91")
      (value "10u")
      (footprint "eagle-import:0603C")
      (libsource (lib "eagle-import") (part "custom-std_CAP0603-CAP"))
    )
    (comp (ref "C92")
      (value "100n")
      (footprint "eagle-import:0402C")
      (libsource (lib "eagle-import") (part "custom-std_CAP0402-CAP"))
    )
    (comp (ref "C93")
      (value "100n")
      (footprint "eagle-import:0402C")
      (libsource (lib "eagle-import") (part "custom-std_CAP0402-CAP"))
    )
    (comp (ref "C94")
      (value "100n")
      (footprint "eagle-import:0402C")
      (libsource (lib "eagle-import") (part "custom-std_CAP0402-CAP"))
    )
    (comp (ref "C95")
      (value "10u")
      (footprint "eagle-import:0603C")
      (libsource (lib "eagle-import") (part "custom-std_CAP0603-CAP"))
    )
    (comp (ref "C96")
      (value "100n")
      (footprint "eagle-import:0402C")
      (libsource (lib "eagle-import") (part "custom-std_CAP0402-CAP"))
    )
    (comp (ref "C97")
      (value "10n")
      (footprint "eagle-import:0402C")
      (libsource (lib "eagle-import") (part "custom-std_CAP0402-CAP"))
    )
    (comp (ref "C98")
      (value "100n")
      (footprint "eagle-import:0402C")
      (libsource (lib "eagle-import") (part "custom-std_CAP0402-CAP"))
    )
    (comp (ref "C99")
      (value "10n")
      (footprint "eagle-import:0402C")
      (libsource (lib "eagle-import") (part "custom-std_CAP0402-CAP"))
    )
    (comp (ref "C100")
      (value "100n")
      (footprint "eagle-import:0402C")
      (libsource (lib "eagle-import") (part "custom-std_CAP0402-CAP"))
    )
    (comp (ref "C110")
      (value "1u")
      (footprint "eagle-import:0603C")
      (libsource (lib "eagle-import") (part "custom-std_CAP0603-CAP"))
    )
    (comp (ref "C111")
      (value "1u")
      (footprint "eagle-import:0603C")
      (libsource (lib "eagle-import") (part "custom-std_CAP0603-CAP"))
    )
    (comp (ref "C112")
      (value "10n, COG")
      (footprint "eagle-import:0402C")
      (libsource (lib "eagle-import") (part "custom-std_CAP0402-CAP"))
    )
    (comp (ref "C113")
      (value "100n")
      (footprint "eagle-import:0402C")
      (libsource (lib "eagle-import") (part "custom-std_CAP0402-CAP"))
    )
    (comp (ref "C114")
      (value "100n")
      (footprint "eagle-import:0402C")
      (libsource (lib "eagle-import") (part "custom-std_CAP0402-CAP"))
    )
    (comp (ref "D1")
      (value "D_ACACSOT23")
      (footprint "eagle-import:SOT-23")
      (fields (field (name "MPN") "BAV99-7F"))
      (libsource (lib "eagle-import") (part "D_ACACSOT23"))
    )
    (comp (ref "L7")
      (value "1k/500mA")
      (footprint "eagle-import:FB603")
      (libsource (lib "eagle-import") (part "FERRITE-0603"))
    )
    (comp (ref "L8")
      (value "1k/500mA")
      (footprint "eagle-import:FB603")
      (libsource (lib "eagle-import") (part "FERRITE-0603"))
    )
    (comp (ref "L9")
      (value "1k/500mA")
      (footprint "eagle-import:FB603")
      (libsource (lib "eagle-import") (part "FERRITE-0603"))
    )
    (comp (ref "L11")
      (value "120nH")
      (footprint "eagle-import:0603")
      (libsource (lib "eagle-import") (part "INDUCTOR0603"))
    )
    (comp (ref "R44")
      (value "274R")
      (footprint "eagle-import:0603R")
      (libsource (lib "eagle-import") (part "custom-std_RES0603-RES"))
    )
    (comp (ref "R45")
      (value "10k")
      (footprint "eagle-import:0603R")
      (libsource (lib "eagle-import") (part "custom-std_RES0603-RES"))
    )
    (comp (ref "R46")
      (value "33R,0.5%")
      (footprint "eagle-import:0603R")
      (libsource (lib "eagle-import") (part "custom-std_RES0603-RES"))
    )
    (comp (ref "R47")
      (value "33R,0.5%")
      (footprint "eagle-import:0603R")
      (libsource (lib "eagle-import") (part "custom-std_RES0603-RES"))
    )
    (comp (ref "R48")
      (value "1k")
      (footprint "eagle-import:0402R")
      (libsource (lib "eagle-import") (part "custom-std_RES0402-RES"))
    )
    (comp (ref "R49")
      (value "1k")
      (footprint "eagle-import:0402R")
      (libsource (lib "eagle-import") (part "custom-std_RES0402-RES"))
    )
    (comp (ref "R50")
      (value "1k")
      (footprint "eagle-import:0402R")
      (libsource (lib "eagle-import") (part "custom-std_RES0402-RES"))
    )
    (comp (ref "R51")
      (value "1k")
      (footprint "eagle-import:0402R")
      (libsource (lib "eagle-import") (part "custom-std_RES0402-RES"))
    )
    (comp (ref "R52")
      (value "2k")
      (footprint "eagle-import:0603R")
      (libsource (lib "eagle-import") (part "custom-std_RES0603-RES"))
    )
    (comp (ref "R53")
      (value "2k")
      (footprint "eagle-import:0603R")
      (libsource (lib "eagle-import") (part "custom-std_RES0603-RES"))
    )
    (comp (ref "R54")
      (value "100R")
      (footprint "eagle-import:0603R")
      (libsource (lib "eagle-import") (part "custom-std_RES0603-RES"))
    )
    (comp (ref "R55")
      (value "2k")
      (footprint "eagle-import:0603R")
      (libsource (lib "eagle-import") (part "custom-std_RES0603-RES"))
    )
    (comp (ref "R56")
      (value "1k")
      (footprint "eagle-import:0603R")
      (libsource (lib "eagle-import") (part "custom-std_RES0603-RES"))
    )
    (comp (ref "U3")
      (value "AD8331")
      (footprint "eagle-import:QSOP20")
      (fields (field (name "MPN") "AD8331ARQZ") (field (name "OC_DIGIKEY") "AD8331ARQZ-R7CT-ND"))
      (libsource (lib "eagle-import") (part "AD8331"))
    )
    (comp (ref "U4")
      (value "AD9215BRUZ")
      (footprint "eagle-import:TSSOP28")
      (fields (field (name "MPN") "AD9215BRUZ-105") (field (name "OC_DIGIKEY") "AD9215BRUZ-105-ND"))
      (libsource (lib "eagle-import") (part "AD9215BRUZ"))
    )
    (comp (ref "U10")
      (value "LP3985IM5-3.0")
      (footprint "eagle-import:SOT23-5")
      (fields
        (field (name "MPN") "LP3985IM5X-3.0/NOPB")
        (field (name "OC_DIGIKEY") "LP3985IM5X-3.0/NOPBCT-ND")
      )
      (libsource (lib "eagle-import") (part "V_REG_LDOSMD"))
    )
    (comp (ref "C20")
      (value "100n")
      (footprint "eagle-import:0402C")
      (libsource (lib "eagle-import") (part "CAP0402-CAP"))
    )
    (comp (ref "C22")
      (value "100n")
      (footprint "eagle-import:0402C")
      (libsource (lib "eagle-import") (part "CAP0402-CAP"))
    )
    (comp (ref "C23")
      (value "100n")
      (footprint "eagle-import:0402C")
      (libsource (lib "eagle-import") (part "CAP0402-CAP"))
    )
    (comp (ref "C24")
      (value "100n")
      (footprint "eagle-import:0402C")
      (libsource (lib "eagle-import") (part "CAP0402-CAP"))
    )
    (comp (ref "C25")
      (value "100n")
      (footprint "eagle-import:0402C")
      (libsource (lib "eagle-import") (part "CAP0402-CAP"))
    )
    (comp (ref "C26")
      (value "2u2")
      (footprint "eagle-import:0603C")
      (libsource (lib "eagle-import") (part "CAP0603-CAP"))
    )
    (comp (ref "C27")
      (value "2u2")
      (footprint "eagle-import:0603C")
      (libsource (lib "eagle-import") (part "CAP0603-CAP"))
    )
    (comp (ref "C28")
      (value "100n")
      (footprint "eagle-import:0402C")
      (libsource (lib "eagle-import") (part "CAP0402-CAP"))
    )
    (comp (ref "C29")
      (value "100n")
      (footprint "eagle-import:0402C")
      (libsource (lib "eagle-import") (part "CAP0402-CAP"))
    )
    (comp (ref "C30")
      (value "100n")
      (footprint "eagle-import:0402C")
      (libsource (lib "eagle-import") (part "CAP0402-CAP"))
    )
    (comp (ref "C31")
      (value "100n")
      (footprint "eagle-import:0402C")
      (libsource (lib "eagle-import") (part "CAP0402-CAP"))
    )
    (comp (ref "C32")
      (value "100n")
      (footprint "eagle-import:0402C")
      (libsource (lib "eagle-import") (part "CAP0402-CAP"))
    )
    (comp (ref "C49")
      (value "100n")
      (footprint "eagle-import:0603C")
      (libsource (lib "eagle-import") (part "CAP0603-CAP"))
    )
    (comp (ref "C52")
      (value "100n")
      (footprint "eagle-import:0402C")
      (libsource (lib "eagle-import") (part "custom-std_CAP0402-CAP"))
    )
    (comp (ref "C53")
      (value "100n")
      (footprint "eagle-import:0402C")
      (libsource (lib "eagle-import") (part "custom-std_CAP0402-CAP"))
    )
    (comp (ref "C54")
      (value "100n")
      (footprint "eagle-import:0402C")
      (libsource (lib "eagle-import") (part "custom-std_CAP0402-CAP"))
    )
    (comp (ref "C55")
      (value "100n")
      (footprint "eagle-import:0402C")
      (libsource (lib "eagle-import") (part "custom-std_CAP0402-CAP"))
    )
    (comp (ref "C56")
      (value "100n")
      (footprint "eagle-import:0402C")
      (libsource (lib "eagle-import") (part "custom-std_CAP0402-CAP"))
    )
    (comp (ref "C57")
      (value "100n")
      (footprint "eagle-import:0402C")
      (libsource (lib "eagle-import") (part "custom-std_CAP0402-CAP"))
    )
    (comp (ref "C58")
      (value "100n")
      (footprint "eagle-import:0402C")
      (libsource (lib "eagle-import") (part "custom-std_CAP0402-CAP"))
    )
    (comp (ref "C59")
      (value "100n")
      (footprint "eagle-import:0402C")
      (libsource (lib "eagle-import") (part "custom-std_CAP0402-CAP"))
    )
    (comp (ref "C60")
      (value "1u")
      (footprint "eagle-import:0603C")
      (libsource (lib "eagle-import") (part "custom-std_CAP0603-CAP"))
    )
    (comp (ref "C61")
      (value "1u")
      (footprint "eagle-import:0603C")
      (libsource (lib "eagle-import") (part "custom-std_CAP0603-CAP"))
    )
    (comp (ref "C62")
      (value "1u")
      (footprint "eagle-import:0603C")
      (libsource (lib "eagle-import") (part "custom-std_CAP0603-CAP"))
    )
    (comp (ref "J4")
      (value "CON_HEADER_PRG_XILINX_JTAG6")
      (footprint "eagle-import:HEADER_PRG_1X06")
      (libsource (lib "eagle-import") (part "CON_HEADER_PRG_XILINX_JTAG6"))
    )
    (comp (ref "R3")
      (value "1k")
      (footprint "eagle-import:0603R")
      (libsource (lib "eagle-import") (part "RES0603-RES"))
    )
    (comp (ref "R4")
      (value "DNM")
      (footprint "eagle-import:0603R")
      (libsource (lib "eagle-import") (part "RES0603-RES"))
    )
    (comp (ref "R5")
      (value "1R")
      (footprint "eagle-import:0402R")
      (libsource (lib "eagle-import") (part "RES0402-RES"))
    )
    (comp (ref "R6")
      (value "1R")
      (footprint "eagle-import:0402R")
      (libsource (lib "eagle-import") (part "RES0402-RES"))
    )
    (comp (ref "R7")
      (value "1k")
      (footprint "eagle-import:0603R")
      (libsource (lib "eagle-import") (part "RES0603-RES"))
    )
    (comp (ref "R8")
      (value "DNM")
      (footprint "eagle-import:0603R")
      (libsource (lib "eagle-import") (part "RES0603-RES"))
    )
    (comp (ref "R9")
      (value "10k")
      (footprint "eagle-import:0402R")
      (libsource (lib "eagle-import") (part "RES0402-RES"))
    )
    (comp (ref "R11")
      (value "10k")
      (footprint "eagle-import:0402R")
      (libsource (lib "eagle-import") (part "RES0402-RES"))
    )
    (comp (ref "R12")
      (value "10k")
      (footprint "eagle-import:0402R")
      (libsource (lib "eagle-import") (part "RES0402-RES"))
    )
    (comp (ref "R22")
      (value "DNM")
      (footprint "eagle-import:0603R")
      (libsource (lib "eagle-import") (part "RES0603-RES"))
    )
    (comp (ref "R69")
      (value "10k")
      (footprint "eagle-import:0402R")
      (libsource (lib "eagle-import") (part "RES0402-RES"))
    )
    (comp (ref "R70")
      (value "DNM")
      (footprint "eagle-import:0402R")
      (libsource (lib "eagle-import") (part "RES0402-RES"))
    )
    (comp (ref "R71")
      (value "DNM")
      (footprint "eagle-import:0402R")
      (libsource (lib "eagle-import") (part "RES0402-RES"))
    )
    (comp (ref "U9")
      (value "SPI_FLASH-X25XXSMD1")
      (footprint "eagle-import:SO08-EIAJ")
      (libsource (lib "eagle-import") (part "SPI_FLASH-X25XXSMD1"))
    )
    (comp (ref "C63")
      (value "1u")
      (footprint "eagle-import:0603C")
      (libsource (lib "eagle-import") (part "custom-std_CAP0603-CAP"))
    )
    (comp (ref "C64")
      (value "100n")
      (footprint "eagle-import:0402C")
      (libsource (lib "eagle-import") (part "custom-std_CAP0402-CAP"))
    )
    (comp (ref "C65")
      (value "100n")
      (footprint "eagle-import:0402C")
      (libsource (lib "eagle-import") (part "custom-std_CAP0402-CAP"))
    )
    (comp (ref "C66")
      (value "100n")
      (footprint "eagle-import:0402C")
      (libsource (lib "eagle-import") (part "custom-std_CAP0402-CAP"))
    )
    (comp (ref "C101")
      (value "220n")
      (footprint "eagle-import:0402C")
      (libsource (lib "eagle-import") (part "custom-std_CAP0402-CAP"))
    )
    (comp (ref "C102")
      (value "220n")
      (footprint "eagle-import:0402C")
      (libsource (lib "eagle-import") (part "custom-std_CAP0402-CAP"))
    )
    (comp (ref "J1")
      (value "SHROUD_2X10-SHROUDED")
      (footprint "eagle-import:PINSHRD_PTH_2X10")
      (libsource (lib "eagle-import") (part "SHROUD_2X10-SHROUDED"))
    )
    (comp (ref "J6")
      (value "SHROUD_2X4SHROUD")
      (footprint "eagle-import:PINSHRD_PTH_2X04")
      (libsource (lib "eagle-import") (part "SHROUD_2X4SHROUD"))
    )
    (comp (ref "JP5")
      (value "PINHD-1X3")
      (footprint "eagle-import:1X03")
      (libsource (lib "eagle-import") (part "pinhead_PINHD-1X3"))
    )
    (comp (ref "JP8")
      (value "PINHD-1X3")
      (footprint "eagle-import:1X03")
      (libsource (lib "eagle-import") (part "PINHD-1X3"))
    )
    (comp (ref "JP9")
      (value "PINHD-1X10")
      (footprint "eagle-import:1X10-BIG")
      (libsource (lib "eagle-import") (part "PINHD-1X10"))
    )
    (comp (ref "JP10")
      (value "PINHD-1X3")
      (footprint "eagle-import:1X03")
      (libsource (lib "eagle-import") (part "PINHD-1X3"))
    )
    (comp (ref "JP11")
      (value "PINHD-1X3")
      (footprint "eagle-import:1X03")
      (libsource (lib "eagle-import") (part "PINHD-1X3"))
    )
    (comp (ref "JP18")
      (value "PINHD-1X1")
      (footprint "eagle-import:1X01")
      (libsource (lib "eagle-import") (part "PINHD-1X1"))
    )
    (comp (ref "R35")
      (value "39R")
      (footprint "eagle-import:0603R")
      (libsource (lib "eagle-import") (part "custom-std_RES0603-RES"))
    )
    (comp (ref "R36")
      (value "39R")
      (footprint "eagle-import:0603R")
      (libsource (lib "eagle-import") (part "custom-std_RES0603-RES"))
    )
    (comp (ref "R37")
      (value "1R")
      (footprint "eagle-import:0603R")
      (libsource (lib "eagle-import") (part "custom-std_RES0603-RES"))
    )
    (comp (ref "R43")
      (value "10k")
      (footprint "eagle-import:0603R")
      (libsource (lib "eagle-import") (part "custom-std_RES0603-RES"))
    )
    (comp (ref "R59")
      (value "1R")
      (footprint "eagle-import:0603R")
      (libsource (lib "eagle-import") (part "custom-std_RES0603-RES"))
    )
    (comp (ref "R60")
      (value "DNM")
      (footprint "eagle-import:0603R")
      (libsource (lib "eagle-import") (part "custom-std_RES0603-RES"))
    )
    (comp (ref "R61")
      (value "10k")
      (footprint "eagle-import:0603R")
      (libsource (lib "eagle-import") (part "custom-std_RES0603-RES"))
    )
    (comp (ref "R65")
      (value "10k")
      (footprint "eagle-import:0603R")
      (libsource (lib "eagle-import") (part "custom-std_RES0603-RES"))
    )
    (comp (ref "R78")
      (value "1R")
      (footprint "eagle-import:0603R")
      (libsource (lib "eagle-import") (part "custom-std_RES0603-RES"))
    )
    (comp (ref "SJ6")
      (value "SOLDERJUMPERNC")
      (footprint "eagle-import:SJ_2S")
      (libsource (lib "eagle-import") (part "SOLDERJUMPERNC"))
    )
    (comp (ref "T4")
      (value "IRLML2502")
      (footprint "eagle-import:SOT-23")
      (fields (field (name "MPN") "IRLML2502TRPBF") (field (name "OC_DIGIKEY") "IRLML2502PBFCT-ND"))
      (libsource (lib "eagle-import") (part "NMOSSOT23"))
    )
    (comp (ref "U8")
      (value "IRF7807ZTRPBF")
      (footprint "eagle-import:SO08")
      (libsource (lib "eagle-import") (part "MOSFET-NCHANNEL-SOIC8"))
    )
    (comp (ref "X2")
      (value "SMA-NOSILK")
      (footprint "eagle-import:J502-ND-142-0711-821_826-NOSILK")
      (libsource (lib "eagle-import") (part "SMA-NOSILK"))
    )
    (comp (ref "X4")
      (value "SMA-NOSILK")
      (footprint "eagle-import:J502-ND-142-0711-821_826-NOSILK")
      (libsource (lib "eagle-import") (part "SMA-NOSILK"))
    )
    (comp (ref "C34")
      (value "22u")
      (footprint "eagle-import:0805")
      (libsource (lib "eagle-import") (part "custom-std_CAP0805"))
    )
    (comp (ref "C35")
      (value "22u")
      (footprint "eagle-import:0805")
      (libsource (lib "eagle-import") (part "custom-std_CAP0805"))
    )
    (comp (ref "C36")
      (value "22u")
      (footprint "eagle-import:0805")
      (libsource (lib "eagle-import") (part "custom-std_CAP0805"))
    )
    (comp (ref "C38")
      (value "2u2")
      (footprint "eagle-import:0603C")
      (libsource (lib "eagle-import") (part "custom-std_CAP0603-CAP"))
    )
    (comp (ref "C39")
      (value "2u2")
      (footprint "eagle-import:0603C")
      (libsource (lib "eagle-import") (part "custom-std_CAP0603-CAP"))
    )
    (comp (ref "FID1")
      (value "FIDUCIAL1.5X3")
      (footprint "eagle-import:FIDUCIAL-1.5X3")
      (libsource (lib "eagle-import") (part "FIDUCIAL1.5X3"))
    )
    (comp (ref "FID2")
      (value "FIDUCIAL1.5X3")
      (footprint "eagle-import:FIDUCIAL-1.5X3")
      (libsource (lib "eagle-import") (part "FIDUCIAL1.5X3"))
    )
    (comp (ref "FID3")
      (value "FIDUCIAL1.5X3")
      (footprint "eagle-import:FIDUCIAL-1.5X3")
      (libsource (lib "eagle-import") (part "FIDUCIAL1.5X3"))
    )
    (comp (ref "FID4")
      (value "FIDUCIAL1.5X3")
      (footprint "eagle-import:FIDUCIAL-1.5X3")
      (libsource (lib "eagle-import") (part "FIDUCIAL1.5X3"))
    )
    (comp (ref "FID5")
      (value "FIDUCIAL1.5X3")
      (footprint "eagle-import:FIDUCIAL-1.5X3")
      (libsource (lib "eagle-import") (part "FIDUCIAL1.5X3"))
    )
    (comp (ref "FID6")
      (value "FIDUCIAL1.5X3")
      (footprint "eagle-import:FIDUCIAL-1.5X3")
      (libsource (lib "eagle-import") (part "FIDUCIAL1.5X3"))
    )
    (comp (ref "H1")
      (value "MOUNT-PAD-ROUND2.8")
      (footprint "eagle-import:2,8-PAD")
      (libsource (lib "eagle-import") (part "MOUNT-PAD-ROUND2.8"))
    )
    (comp (ref "H2")
      (value "MOUNT-PAD-ROUND2.8")
      (footprint "eagle-import:2,8-PAD")
      (libsource (lib "eagle-import") (part "MOUNT-PAD-ROUND2.8"))
    )
    (comp (ref "H3")
      (value "MOUNT-PAD-ROUND2.8")
      (footprint "eagle-import:2,8-PAD")
      (libsource (lib "eagle-import") (part "MOUNT-PAD-ROUND2.8"))
    )
    (comp (ref "H4")
      (value "MOUNT-PAD-ROUND2.8")
      (footprint "eagle-import:2,8-PAD")
      (libsource (lib "eagle-import") (part "MOUNT-PAD-ROUND2.8"))
    )
    (comp (ref "L2")
      (value "3.3uH")
      (footprint "eagle-import:VLS3015")
      (fields (field (name "OC_DIGIKEY") "445-6677-1-ND"))
      (libsource (lib "eagle-import") (part "L_VLS3015"))
    )
    (comp (ref "L3")
      (value "3.3uH")
      (footprint "eagle-import:VLS3015")
      (fields (field (name "MPN") "VLS3015ET-3R3M") (field (name "OC_DIGIKEY") "445-6677-1-ND"))
      (libsource (lib "eagle-import") (part "L_VLS3015"))
    )
    (comp (ref "MFID1")
      (value "FIDUCIALUFIDUCIAL")
      (footprint "eagle-import:MICRO-FIDUCIAL")
      (libsource (lib "eagle-import") (part "FIDUCIALUFIDUCIAL"))
    )
    (comp (ref "MFID2")
      (value "FIDUCIALUFIDUCIAL")
      (footprint "eagle-import:MICRO-FIDUCIAL")
      (libsource (lib "eagle-import") (part "FIDUCIALUFIDUCIAL"))
    )
    (comp (ref "MFID3")
      (value "FIDUCIALUFIDUCIAL")
      (footprint "eagle-import:MICRO-FIDUCIAL")
      (libsource (lib "eagle-import") (part "FIDUCIALUFIDUCIAL"))
    )
    (comp (ref "MFID4")
      (value "FIDUCIALUFIDUCIAL")
      (footprint "eagle-import:MICRO-FIDUCIAL")
      (libsource (lib "eagle-import") (part "FIDUCIALUFIDUCIAL"))
    )
    (comp (ref "R24")
      (value "1k5")
      (footprint "eagle-import:0402R")
      (libsource (lib "eagle-import") (part "custom-std_RES0402-RES"))
    )
    (comp (ref "R25")
      (value "6k81")
      (footprint "eagle-import:0402R")
      (libsource (lib "eagle-import") (part "custom-std_RES0402-RES"))
    )
    (comp (ref "R26")
      (value "1k5")
      (footprint "eagle-import:0402R")
      (libsource (lib "eagle-import") (part "custom-std_RES0402-RES"))
    )
    (comp (ref "R30")
      (value "1k5")
      (footprint "eagle-import:0402R")
      (libsource (lib "eagle-import") (part "custom-std_RES0402-RES"))
    )
    (comp (ref "U5")
      (value "LTC3419EMS")
      (footprint "eagle-import:MSOP10")
      (fields (field (name "MPN") "LTC3419EMS#PBF") (field (name "OC_DIGIKEY") "LTC3419EMS#PBF-ND"))
      (libsource (lib "eagle-import") (part "LTC3419MSE"))
    )
    (comp (ref "U7")
      (value "TC1262-3.3VDBTR")
      (footprint "eagle-import:SOT223")
      (fields (field (name "MPN") "TC1262-3.3VDBTR") (field (name "OC_DIGIKEY") "TC1262-3.3VDBCT-ND"))
      (libsource (lib "eagle-import") (part "V_REG_MIC2920"))
    )
    (comp (ref "D4")
      (value "LED0603")
      (footprint "eagle-import:LED-0603")
      (libsource (lib "eagle-import") (part "LED0603"))
    )
    (comp (ref "D5")
      (value "LED0603")
      (footprint "eagle-import:LED-0603")
      (libsource (lib "eagle-import") (part "LED0603"))
    )
    (comp (ref "D6")
      (value "LED0603")
      (footprint "eagle-import:LED-0603")
      (libsource (lib "eagle-import") (part "LED0603"))
    )
    (comp (ref "D7")
      (value "LED0603")
      (footprint "eagle-import:LED-0603")
      (libsource (lib "eagle-import") (part "LED0603"))
    )
    (comp (ref "J5")
      (value "PINHD-1X10")
      (footprint "eagle-import:1X10-BIG")
      (libsource (lib "eagle-import") (part "PINHD-1X10"))
    )
    (comp (ref "R39")
      (value "330R")
      (footprint "eagle-import:0402R")
      (libsource (lib "eagle-import") (part "custom-std_RES0402-RES"))
    )
    (comp (ref "R40")
      (value "330R")
      (footprint "eagle-import:0402R")
      (libsource (lib "eagle-import") (part "custom-std_RES0402-RES"))
    )
    (comp (ref "R41")
      (value "330R")
      (footprint "eagle-import:0402R")
      (libsource (lib "eagle-import") (part "custom-std_RES0402-RES"))
    )
    (comp (ref "R42")
      (value "330R")
      (footprint "eagle-import:0402R")
      (libsource (lib "eagle-import") (part "custom-std_RES0402-RES"))
    )
    (comp (ref "R68")
      (value "1k")
      (footprint "eagle-import:0402R")
      (libsource (lib "eagle-import") (part "custom-std_RES0402-RES"))
    )
  )
  (nets
    (net (code "1") (name "+3V3") (class "Default")
      (node (ref "C13") (pin "1") (pinfunction "1_1") (pintype "passive"))
      (node (ref "C14") (pin "1") (pinfunction "1_1") (pintype "passive"))
      (node (ref "C15") (pin "1") (pinfunction "1_1") (pintype "passive"))
      (node (ref "C16") (pin "1") (pinfunction "1_1") (pintype "passive"))
      (node (ref "C17") (pin "1") (pinfunction "1_1") (pintype "passive"))
      (node (ref "C18") (pin "1") (pinfunction "1_1") (pintype "passive"))
      (node (ref "C21") (pin "1") (pinfunction "1_1") (pintype "passive"))
      (node (ref "C38") (pin "1") (pinfunction "1_1") (pintype "passive"))
      (node (ref "C6") (pin "1") (pinfunction "1_1") (pintype "passive"))
      (node (ref "J3") (pin "1") (pinfunction "1_1") (pintype "passive"))
      (node (ref "J3") (pin "2") (pinfunction "2_2") (pintype "passive"))
      (node (ref "JP1") (pin "4") (pinfunction "4_4") (pintype "passive"))
      (node (ref "JP4") (pin "2") (pinfunction "2_2") (pintype "passive"))
      (node (ref "L1") (pin "1") (pinfunction "1_1") (pintype "passive"))
      (node (ref "R17") (pin "2") (pinfunction "2_2") (pintype "passive"))
      (node (ref "R18") (pin "2") (pinfunction "2_2") (pintype "passive"))
      (node (ref "R19") (pin "2") (pinfunction "2_2") (pintype "passive"))
      (node (ref "R20") (pin "2") (pinfunction "2_2") (pintype "passive"))
      (node (ref "R21") (pin "2") (pinfunction "2_2") (pintype "passive"))
      (node (ref "R62") (pin "1") (pinfunction "1_1") (pintype "passive"))
      (node (ref "R64") (pin "2") (pinfunction "2_2") (pintype "passive"))
      (node (ref "U1") (pin "1") (pinfunction "VDDANA_1") (pintype "power_in"))
      (node (ref "U1") (pin "2") (pinfunction "ADVREF_2") (pintype "passive"))
      (node (ref "U1") (pin "22") (pinfunction "VDDIO_2_22") (pintype "power_in"))
      (node (ref "U1") (pin "36") (pinfunction "VDDIO_3_36") (pintype "power_in"))
      (node (ref "U1") (pin "4") (pinfunction "AD12BVREF_4") (pintype "passive"))
      (node (ref "U1") (pin "45") (pinfunction "VDDBU_45") (pintype "power_in"))
      (node (ref "U1") (pin "53") (pinfunction "VDDIN_53") (pintype "power_in"))
      (node (ref "U1") (pin "60") (pinfunction "VDDIO_4_60") (pintype "power_in"))
      (node (ref "U1") (pin "88") (pinfunction "VDDIO_88") (pintype "power_in"))
      (node (ref "U7") (pin "3") (pinfunction "OUT_3") (pintype "output"))
    )
    (net (code "2") (name "+5VCLEAN") (class "Default")
      (node (ref "C40") (pin "1") (pinfunction "1_1") (pintype "passive"))
      (node (ref "C41") (pin "1") (pinfunction "1_1") (pintype "passive"))
      (node (ref "L5") (pin "2") (pinfunction "2_2") (pintype "passive"))
      (node (ref "L7") (pin "1") (pinfunction "1_1") (pintype "passive"))
      (node (ref "L8") (pin "1") (pinfunction "1_1") (pintype "passive"))
    )
    (net (code "7") (name "ADC_CLK") (class "Default")
      (node (ref "R54") (pin "2") (pinfunction "2_2") (pintype "passive"))
      (node (ref "U2") (pin "P55") (pinfunction "IO_L30N_GCLK0_USERCCLK_2_P55") (pintype "bidirectional"))
      (node (ref "U2") (pin "P56") (pinfunction "IO_L30P_GCLK1_D13_2_P56") (pintype "bidirectional"))
      (node (ref "U4") (pin "13") (pinfunction "CLK_13") (pintype "bidirectional"))
    )
    (net (code "8") (name "ADC_D0") (class "Default")
      (node (ref "U2") (pin "P59") (pinfunction "IO_L13N_D10_2_P59") (pintype "bidirectional"))
      (node (ref "U4") (pin "17") (pinfunction "D0_17") (pintype "bidirectional"))
    )
    (net (code "9") (name "ADC_D1") (class "Default")
      (node (ref "U2") (pin "P58") (pinfunction "IO_L14P_D11_2_P58") (pintype "bidirectional"))
      (node (ref "U4") (pin "18") (pinfunction "D1_18") (pintype "bidirectional"))
    )
    (net (code "10") (name "ADC_D2") (class "Default")
      (node (ref "U2") (pin "P57") (pinfunction "IO_L14N_D12_2_P57") (pintype "bidirectional"))
      (node (ref "U4") (pin "19") (pinfunction "D2_19") (pintype "bidirectional"))
    )
    (net (code "11") (name "ADC_D3") (class "Default")
      (node (ref "U2") (pin "P48") (pinfunction "IO_L48P_D7_2_P48") (pintype "bidirectional"))
      (node (ref "U4") (pin "20") (pinfunction "D3_20") (pintype "bidirectional"))
    )
    (net (code "12") (name "ADC_D4") (class "Default")
      (node (ref "U2") (pin "P47") (pinfunction "IO_L48N_RDWR_B_VREF_2_P47") (pintype "bidirectional"))
      (node (ref "U4") (pin "21") (pinfunction "D4_21") (pintype "bidirectional"))
    )
    (net (code "13") (name "ADC_D5") (class "Default")
      (node (ref "U2") (pin "P46") (pinfunction "IO_L49P_D3_2_P46") (pintype "bidirectional"))
      (node (ref "U4") (pin "22") (pinfunction "D5_22") (pintype "bidirectional"))
    )
    (net (code "14") (name "ADC_D6") (class "Default")
      (node (ref "U2") (pin "P45") (pinfunction "IO_L49N_D4_2_P45") (pintype "bidirectional"))
      (node (ref "U4") (pin "25") (pinfunction "D6_25") (pintype "bidirectional"))
    )
    (net (code "15") (name "ADC_D7") (class "Default")
      (node (ref "U2") (pin "P44") (pinfunction "IO_L62P_D5_2_P44") (pintype "bidirectional"))
      (node (ref "U4") (pin "26") (pinfunction "D7_26") (pintype "bidirectional"))
    )
    (net (code "16") (name "ADC_D8") (class "Default")
      (node (ref "U2") (pin "P43") (pinfunction "IO_L62N_D6_2_P43") (pintype "bidirectional"))
      (node (ref "U4") (pin "27") (pinfunction "D8_27") (pintype "bidirectional"))
    )
    (net (code "17") (name "ADC_D9") (class "Default")
      (node (ref "U2") (pin "P41") (pinfunction "IO_L64P_D8_2_P41") (pintype "bidirectional"))
      (node (ref "U4") (pin "28") (pinfunction "D9_28") (pintype "bidirectional"))
    )
    (net (code "18") (name "ADC_OR") (class "Default")
      (node (ref "U2") (pin "P40") (pinfunction "IO_L64N_D9_2_P40") (pintype "bidirectional"))
      (node (ref "U4") (pin "1") (pinfunction "OR_1") (pintype "bidirectional"))
    )
    (net (code "19") (name "ADC_VCC") (class "Default")
      (node (ref "C100") (pin "1") (pinfunction "1_1") (pintype "passive"))
      (node (ref "C111") (pin "2") (pinfunction "2_2") (pintype "passive"))
      (node (ref "C113") (pin "2") (pinfunction "2_2") (pintype "passive"))
      (node (ref "C97") (pin "1") (pinfunction "1_1") (pintype "passive"))
      (node (ref "C98") (pin "1") (pinfunction "1_1") (pintype "passive"))
      (node (ref "C99") (pin "1") (pinfunction "1_1") (pintype "passive"))
      (node (ref "R49") (pin "2") (pinfunction "2_2") (pintype "passive"))
      (node (ref "R51") (pin "1") (pinfunction "1_1") (pintype "passive"))
      (node (ref "R55") (pin "2") (pinfunction "2_2") (pintype "passive"))
      (node (ref "U10") (pin "5") (pinfunction "OUT_5") (pintype "passive"))
      (node (ref "U4") (pin "12") (pinfunction "AVDD_12") (pintype "bidirectional"))
      (node (ref "U4") (pin "7") (pinfunction "AVDD_7") (pintype "bidirectional"))
    )
    (net (code "20") (name "ANIN") (class "Default")
      (node (ref "JP10") (pin "2") (pinfunction "2_2") (pintype "passive"))
      (node (ref "L11") (pin "1") (pinfunction "1_1") (pintype "passive"))
      (node (ref "X2") (pin "1") (pinfunction "1_1") (pintype "passive"))
    )
    (net (code "21") (name "CLK2") (class "Default")
      (node (ref "J7") (pin "5") (pinfunction "5_5") (pintype "passive"))
      (node (ref "U1") (pin "24") (pinfunction "PA25_24") (pintype "bidirectional"))
      (node (ref "U2") (pin "P131") (pinfunction "IO_L35N_GCLK16_0_P131") (pintype "bidirectional"))
    )
    (net (code "22") (name "D_N") (class "Default")
      (node (ref "J8") (pin "2") (pinfunction "DM_2") (pintype "bidirectional"))
      (node (ref "R27") (pin "2") (pinfunction "2_2") (pintype "passive"))
      (node (ref "U1") (pin "77") (pinfunction "DHSDM_77") (pintype "bidirectional"))
      (node (ref "U6") (pin "3") (pinfunction "IO2_3") (pintype "bidirectional"))
    )
    (net (code "23") (name "D_P") (class "Default")
      (node (ref "J8") (pin "3") (pinfunction "DP_3") (pintype "bidirectional"))
      (node (ref "R28") (pin "2") (pinfunction "2_2") (pintype "passive"))
      (node (ref "U1") (pin "76") (pinfunction "DHSDP_76") (pintype "bidirectional"))
      (node (ref "U6") (pin "2") (pinfunction "IO1_2") (pintype "bidirectional"))
    )
    (net (code "24") (name "ERASE") (class "Default")
      (node (ref "JP4") (pin "1") (pinfunction "1_1") (pintype "passive"))
      (node (ref "U1") (pin "43") (pinfunction "ERASE_43") (pintype "input"))
    )
    (net (code "25") (name "FPGA_DONE") (class "Default")
      (node (ref "R11") (pin "1") (pinfunction "1_1") (pintype "passive"))
      (node (ref "U1") (pin "39") (pinfunction "PA10/PGMD2_39") (pintype "bidirectional"))
      (node (ref "U2") (pin "P71") (pinfunction "DONE_2_P71") (pintype "bidirectional"))
    )
    (net (code "26") (name "FPGA_INITB") (class "Default")
      (node (ref "R69") (pin "2") (pinfunction "2_2") (pintype "passive"))
      (node (ref "U1") (pin "38") (pinfunction "PA9/PGMD1_38") (pintype "bidirectional"))
      (node (ref "U2") (pin "P39") (pinfunction "IO_L65P_INIT_B_2_P39") (pintype "bidirectional"))
    )
    (net (code "27") (name "FPGA_PROGRAM") (class "Default")
      (node (ref "R12") (pin "1") (pinfunction "1_1") (pintype "passive"))
      (node (ref "U1") (pin "37") (pinfunction "PA8/PGMD0_37") (pintype "bidirectional"))
      (node (ref "U2") (pin "P37") (pinfunction "PROGRAM_B_2_P37") (pintype "input"))
    )
    (net (code "28") (name "FSC_AX1") (class "Default")
      (node (ref "J6") (pin "7") (pinfunction "7_7") (pintype "passive"))
      (node (ref "U2") (pin "P98") (pinfunction "IO_L34P_1_P98") (pintype "bidirectional"))
    )
    (net (code "29") (name "FSC_AX2") (class "Default")
      (node (ref "J6") (pin "8") (pinfunction "8_8") (pintype "passive"))
      (node (ref "U2") (pin "P97") (pinfunction "IO_L34N_1_P97") (pintype "bidirectional"))
    )
    (net (code "30") (name "FSC_CLK") (class "Default")
      (node (ref "J6") (pin "5") (pinfunction "5_5") (pintype "passive"))
      (node (ref "U2") (pin "P100") (pinfunction "IO_L33P_1_P100") (pintype "bidirectional"))
    )
    (net (code "31") (name "FSC_IO") (class "Default")
      (node (ref "J6") (pin "6") (pinfunction "6_6") (pintype "passive"))
      (node (ref "R61") (pin "2") (pinfunction "2_2") (pintype "passive"))
      (node (ref "U2") (pin "P99") (pinfunction "IO_L33N_1_P99") (pintype "bidirectional"))
    )
    (net (code "32") (name "FSC_RST") (class "Default")
      (node (ref "J6") (pin "3") (pinfunction "3_3") (pintype "passive"))
      (node (ref "U2") (pin "P102") (pinfunction "IO_L32P_1_P102") (pintype "bidirectional"))
    )
    (net (code "33") (name "FSC_VPP") (class "Default")
      (node (ref "R60") (pin "2") (pinfunction "2_2") (pintype "passive"))
      (node (ref "U2") (pin "P101") (pinfunction "IO_L32N_1_P101") (pintype "bidirectional"))
    )
    (net (code "34") (name "GLITCHOUT") (class "Default")
      (node (ref "JP8") (pin "1") (pinfunction "1_1") (pintype "passive"))
      (node (ref "R37") (pin "2") (pinfunction "2_2") (pintype "passive"))
      (node (ref "U2") (pin "P66") (pinfunction "IO_L2N_CMPMOSI_2_P66") (pintype "bidirectional"))
    )
    (net (code "35") (name "GLITCHOUTLP") (class "Default")
      (node (ref "R78") (pin "2") (pinfunction "2_2") (pintype "passive"))
      (node (ref "U2") (pin "P67") (pinfunction "IO_L2P_CMPCLK_2_P67") (pintype "bidirectional"))
    )
    (net (code "36") (name "GND") (class "Default")
      (node (ref "C1") (pin "2") (pinfunction "2_2") (pintype "passive"))
      (node (ref "C10") (pin "2") (pinfunction "2_2") (pintype "passive"))
      (node (ref "C100") (pin "2") (pinfunction "2_2") (pintype "passive"))
      (node (ref "C101") (pin "2") (pinfunction "2_2") (pintype "passive"))
      (node (ref "C102") (pin "2") (pinfunction "2_2") (pintype "passive"))
      (node (ref "C11") (pin "2") (pinfunction "2_2") (pintype "passive"))
      (node (ref "C110") (pin "1") (pinfunction "1_1") (pintype "passive"))
      (node (ref "C111") (pin "1") (pinfunction "1_1") (pintype "passive"))
      (node (ref "C112") (pin "1") (pinfunction "1_1") (pintype "passive"))
      (node (ref "C113") (pin "1") (pinfunction "1_1") (pintype "passive"))
      (node (ref "C114") (pin "1") (pinfunction "1_1") (pintype "passive"))
      (node (ref "C12") (pin "2") (pinfunction "2_2") (pintype "passive"))
      (node (ref "C122") (pin "2") (pinfunction "2_2") (pintype "passive"))
      (node (ref "C123") (pin "2") (pinfunction "2_2") (pintype "passive"))
      (node (ref "C13") (pin "2") (pinfunction "2_2") (pintype "passive"))
      (node (ref "C14") (pin "2") (pinfunction "2_2") (pintype "passive"))
      (node (ref "C15") (pin "2") (pinfunction "2_2") (pintype "passive"))
      (node (ref "C16") (pin "2") (pinfunction "2_2") (pintype "passive"))
      (node (ref "C17") (pin "2") (pinfunction "2_2") (pintype "passive"))
      (node (ref "C18") (pin "2") (pinfunction "2_2") (pintype "passive"))
      (node (ref "C19") (pin "2") (pinfunction "2_2") (pintype "passive"))
      (node (ref "C2") (pin "2") (pinfunction "2_2") (pintype "passive"))
      (node (ref "C20") (pin "2") (pinfunction "2_2") (pintype "passive"))
      (node (ref "C21") (pin "2") (pinfunction "2_2") (pintype "passive"))
      (node (ref "C22") (pin "2") (pinfunction "2_2") (pintype "passive"))
      (node (ref "C23") (pin "2") (pinfunction "2_2") (pintype "passive"))
      (node (ref "C24") (pin "2") (pinfunction "2_2") (pintype "passive"))
      (node (ref "C25") (pin "2") (pinfunction "2_2") (pintype "passive"))
      (node (ref "C26") (pin "2") (pinfunction "2_2") (pintype "passive"))
      (node (ref "C27") (pin "2") (pinfunction "2_2") (pintype "passive"))
      (node (ref "C28") (pin "2") (pinfunction "2_2") (pintype "passive"))
      (node (ref "C29") (pin "2") (pinfunction "2_2") (pintype "passive"))
      (node (ref "C3") (pin "1") (pinfunction "1_1") (pintype "passive"))
      (node (ref "C30") (pin "2") (pinfunction "2_2") (pintype "passive"))
      (node (ref "C31") (pin "2") (pinfunction "2_2") (pintype "passive"))
      (node (ref "C32") (pin "2") (pinfunction "2_2") (pintype "passive"))
      (node (ref "C33") (pin "2") (pinfunction "2_2") (pintype "passive"))
      (node (ref "C34") (pin "2") (pinfunction "2_2") (pintype "passive"))
      (node (ref "C35") (pin "2") (pinfunction "2_2") (pintype "passive"))
      (node (ref "C36") (pin "2") (pinfunction "2_2") (pintype "passive"))
      (node (ref "C38") (pin "2") (pinfunction "2_2") (pintype "passive"))
      (node (ref "C39") (pin "2") (pinfunction "2_2") (pintype "passive"))
      (node (ref "C4") (pin "2") (pinfunction "2_2") (pintype "passive"))
      (node (ref "C40") (pin "2") (pinfunction "2_2") (pintype "passive"))
      (node (ref "C41") (pin "2") (pinfunction "2_2") (pintype "passive"))
      (node (ref "C42") (pin "2") (pinfunction "2_2") (pintype "passive"))
      (node (ref "C43") (pin "2") (pinfunction "2_2") (pintype "passive"))
      (node (ref "C44") (pin "2") (pinfunction "2_2") (pintype "passive"))
      (node (ref "C45") (pin "2") (pinfunction "2_2") (pintype "passive"))
      (node (ref "C46") (pin "2") (pinfunction "2_2") (pintype "passive"))
      (node (ref "C47") (pin "2") (pinfunction "2_2") (pintype "passive"))
      (node (ref "C48") (pin "2") (pinfunction "2_2") (pintype "passive"))
      (node (ref "C49") (pin "1") (pinfunction "1_1") (pintype "passive"))
      (node (ref "C5") (pin "2") (pinfunction "2_2") (pintype "passive"))
      (node (ref "C50") (pin "1") (pinfunction "1_1") (pintype "passive"))
      (node (ref "C51") (pin "1") (pinfunction "1_1") (pintype "passive"))
      (node (ref "C52") (pin "2") (pinfunction "2_2") (pintype "passive"))
      (node (ref "C53") (pin "2") (pinfunction "2_2") (pintype "passive"))
      (node (ref "C54") (pin "2") (pinfunction "2_2") (pintype "passive"))
      (node (ref "C55") (pin "2") (pinfunction "2_2") (pintype "passive"))
      (node (ref "C56") (pin "2") (pinfunction "2_2") (pintype "passive"))
      (node (ref "C57") (pin "2") (pinfunction "2_2") (pintype "passive"))
      (node (ref "C58") (pin "2") (pinfunction "2_2") (pintype "passive"))
      (node (ref "C59") (pin "2") (pinfunction "2_2") (pintype "passive"))
      (node (ref "C6") (pin "2") (pinfunction "2_2") (pintype "passive"))
      (node (ref "C60") (pin "2") (pinfunction "2_2") (pintype "passive"))
      (node (ref "C61") (pin "2") (pinfunction "2_2") (pintype "passive"))
      (node (ref "C62") (pin "2") (pinfunction "2_2") (pintype "passive"))
      (node (ref "C63") (pin "2") (pinfunction "2_2") (pintype "passive"))
      (node (ref "C64") (pin "2") (pinfunction "2_2") (pintype "passive"))
      (node (ref "C65") (pin "2") (pinfunction "2_2") (pintype "passive"))
      (node (ref "C66") (pin "2") (pinfunction "2_2") (pintype "passive"))
      (node (ref "C69") (pin "1") (pinfunction "1_1") (pintype "passive"))
      (node (ref "C7") (pin "2") (pinfunction "2_2") (pintype "passive"))
      (node (ref "C72") (pin "1") (pinfunction "1_1") (pintype "passive"))
      (node (ref "C73") (pin "1") (pinfunction "1_1") (pintype "passive"))
      (node (ref "C74") (pin "1") (pinfunction "1_1") (pintype "passive"))
      (node (ref "C75") (pin "1") (pinfunction "1_1") (pintype "passive"))
      (node (ref "C76") (pin "1") (pinfunction "1_1") (pintype "passive"))
      (node (ref "C77") (pin "1") (pinfunction "1_1") (pintype "passive"))
      (node (ref "C78") (pin "1") (pinfunction "1_1") (pintype "passive"))
      (node (ref "C79") (pin "1") (pinfunction "1_1") (pintype "passive"))
      (node (ref "C8") (pin "2") (pinfunction "2_2") (pintype "passive"))
      (node (ref "C80") (pin "1") (pinfunction "1_1") (pintype "passive"))
      (node (ref "C81") (pin "1") (pinfunction "1_1") (pintype "passive"))
      (node (ref "C82") (pin "1") (pinfunction "1_1") (pintype "passive"))
      (node (ref "C83") (pin "1") (pinfunction "1_1") (pintype "passive"))
      (node (ref "C84") (pin "1") (pinfunction "1_1") (pintype "passive"))
      (node (ref "C87") (pin "1") (pinfunction "1_1") (pintype "passive"))
      (node (ref "C88") (pin "2") (pinfunction "2_2") (pintype "passive"))
      (node (ref "C89") (pin "1") (pinfunction "1_1") (pintype "passive"))
      (node (ref "C9") (pin "2") (pinfunction "2_2") (pintype "passive"))
      (node (ref "C90") (pin "1") (pinfunction "1_1") (pintype "passive"))
      (node (ref "C93") (pin "2") (pinfunction "2_2") (pintype "passive"))
      (node (ref "C94") (pin "2") (pinfunction "2_2") (pintype "passive"))
      (node (ref "C95") (pin "1") (pinfunction "1_1") (pintype "passive"))
      (node (ref "C96") (pin "1") (pinfunction "1_1") (pintype "passive"))
      (node (ref "C97") (pin "2") (pinfunction "2_2") (pintype "passive"))
      (node (ref "C98") (pin "2") (pinfunction "2_2") (pintype "passive"))
      (node (ref "C99") (pin "2") (pinfunction "2_2") (pintype "passive"))
      (node (ref "D1") (pin "2") (pinfunction "C_2") (pintype "passive"))
      (node (ref "J1") (pin "17") (pinfunction "17_17") (pintype "passive"))
      (node (ref "J1") (pin "19") (pinfunction "19_19") (pintype "passive"))
      (node (ref "J1") (pin "2") (pinfunction "2_2") (pintype "passive"))
      (node (ref "J3") (pin "10") (pinfunction "10_10") (pintype "passive"))
      (node (ref "J3") (pin "12") (pinfunction "12_12") (pintype "passive"))
      (node (ref "J3") (pin "14") (pinfunction "14_14") (pintype "passive"))
      (node (ref "J3") (pin "16") (pinfunction "16_16") (pintype "passive"))
      (node (ref "J3") (pin "18") (pinfunction "18_18") (pintype "passive"))
      (node (ref "J3") (pin "20") (pinfunction "20_20") (pintype "passive"))
      (node (ref "J3") (pin "4") (pinfunction "4_4") (pintype "passive"))
      (node (ref "J3") (pin "6") (pinfunction "6_6") (pintype "passive"))
      (node (ref "J3") (pin "8") (pinfunction "8_8") (pintype "passive"))
      (node (ref "J4") (pin "2") (pinfunction "GND_2") (pintype "passive"))
      (node (ref "J5") (pin "10") (pinfunction "10_10") (pintype "passive"))
      (node (ref "J6") (pin "2") (pinfunction "2_2") (pintype "passive"))
      (node (ref "J7") (pin "2") (pinfunction "2_2") (pintype "passive"))
      (node (ref "J8") (pin "5") (pinfunction "GND_5") (pintype "bidirectional"))
      (node (ref "JP1") (pin "1") (pinfunction "1_1") (pintype "passive"))
      (node (ref "JP10") (pin "1") (pinfunction "1_1") (pintype "passive"))
      (node (ref "JP10") (pin "3") (pinfunction "3_3") (pintype "passive"))
      (node (ref "JP11") (pin "1") (pinfunction "1_1") (pintype "passive"))
      (node (ref "JP11") (pin "3") (pinfunction "3_3") (pintype "passive"))
      (node (ref "JP2") (pin "2") (pinfunction "2_2") (pintype "passive"))
      (node (ref "JP3") (pin "2") (pinfunction "2_2") (pintype "passive"))
      (node (ref "JP8") (pin "3") (pinfunction "3_3") (pintype "passive"))
      (node (ref "JP9") (pin "1") (pinfunction "1_1") (pintype "passive"))
      (node (ref "JP9") (pin "10") (pinfunction "10_10") (pintype "passive"))
      (node (ref "JP9") (pin "4") (pinfunction "4_4") (pintype "passive"))
      (node (ref "Q1") (pin "2") (pinfunction "G1_2") (pintype "power_in"))
      (node (ref "Q1") (pin "4") (pinfunction "G2_4") (pintype "power_in"))
      (node (ref "R23") (pin "2") (pinfunction "2_2") (pintype "passive"))
      (node (ref "R24") (pin "1") (pinfunction "1_1") (pintype "passive"))
      (node (ref "R26") (pin "1") (pinfunction "1_1") (pintype "passive"))
      (node (ref "R29") (pin "1") (pinfunction "1_1") (pintype "passive"))
      (node (ref "R34") (pin "1") (pinfunction "1_1") (pintype "passive"))
      (node (ref "R39") (pin "2") (pinfunction "2_2") (pintype "passive"))
      (node (ref "R4") (pin "1") (pinfunction "1_1") (pintype "passive"))
      (node (ref "R40") (pin "2") (pinfunction "2_2") (pintype "passive"))
      (node (ref "R41") (pin "2") (pinfunction "2_2") (pintype "passive"))
      (node (ref "R42") (pin "2") (pinfunction "2_2") (pintype "passive"))
      (node (ref "R43") (pin "2") (pinfunction "2_2") (pintype "passive"))
      (node (ref "R45") (pin "1") (pinfunction "1_1") (pintype "passive"))
      (node (ref "R48") (pin "2") (pinfunction "2_2") (pintype "passive"))
      (node (ref "R50") (pin "1") (pinfunction "1_1") (pintype "passive"))
      (node (ref "R54") (pin "1") (pinfunction "1_1") (pintype "passive"))
      (node (ref "R56") (pin "1") (pinfunction "1_1") (pintype "passive"))
      (node (ref "R57") (pin "1") (pinfunction "1_1") (pintype "passive"))
      (node (ref "R58") (pin "1") (pinfunction "1_1") (pintype "passive"))
      (node (ref "R65") (pin "2") (pinfunction "2_2") (pintype "passive"))
      (node (ref "R71") (pin "2") (pinfunction "2_2") (pintype "passive"))
      (node (ref "R77") (pin "1") (pinfunction "1_1") (pintype "passive"))
      (node (ref "R8") (pin "1") (pinfunction "1_1") (pintype "passive"))
      (node (ref "S1") (pin "3") (pinfunction "3_3") (pintype "passive"))
      (node (ref "S1") (pin "4") (pinfunction "4_4") (pintype "passive"))
      (node (ref "T2") (pin "2") (pinfunction "S_2") (pintype "passive"))
      (node (ref "T4") (pin "2") (pinfunction "S_2") (pintype "passive"))
      (node (ref "U1") (pin "3") (pinfunction "GNDANA_3") (pintype "passive"))
      (node (ref "U1") (pin "35") (pinfunction "GND_2_35") (pintype "passive"))
      (node (ref "U1") (pin "42") (pinfunction "FWUP_42") (pintype "input"))
      (node (ref "U1") (pin "44") (pinfunction "TST_44") (pintype "input"))
      (node (ref "U1") (pin "46") (pinfunction "GNDBU_46") (pintype "passive"))
      (node (ref "U1") (pin "48") (pinfunction "JTAGSEL_48") (pintype "input"))
      (node (ref "U1") (pin "61") (pinfunction "GND_3_61") (pintype "passive"))
      (node (ref "U1") (pin "72") (pinfunction "GNDPLL_72") (pintype "passive"))
      (node (ref "U1") (pin "82") (pinfunction "GNDUTMI_82") (pintype "passive"))
      (node (ref "U1") (pin "89") (pinfunction "GND_89") (pintype "passive"))
      (node (ref "U10") (pin "2") (pinfunction "GND_2") (pintype "input"))
      (node (ref "U2") (pin "P108") (pinfunction "GND_P108") (pintype "power_in"))
      (node (ref "U2") (pin "P113") (pinfunction "GND_P113") (pintype "power_in"))
      (node (ref "U2") (pin "P13") (pinfunction "GND_P13") (pintype "power_in"))
      (node (ref "U2") (pin "P130") (pinfunction "GND_P130") (pintype "power_in"))
      (node (ref "U2") (pin "P136") (pinfunction "GND_P136") (pintype "power_in"))
      (node (ref "U2") (pin "P25") (pinfunction "GND_P25") (pintype "power_in"))
      (node (ref "U2") (pin "P3") (pinfunction "GND_P3") (pintype "power_in"))
      (node (ref "U2") (pin "P49") (pinfunction "GND_P49") (pintype "power_in"))
      (node (ref "U2") (pin "P54") (pinfunction "GND_P54") (pintype "power_in"))
      (node (ref "U2") (pin "P68") (pinfunction "GND_P68") (pintype "power_in"))
      (node (ref "U2") (pin "P73") (pinfunction "SUSPEND_P73") (pintype "input"))
      (node (ref "U2") (pin "P77") (pinfunction "GND_P77") (pintype "power_in"))
      (node (ref "U2") (pin "P91") (pinfunction "GND_P91") (pintype "power_in"))
      (node (ref "U2") (pin "P96") (pinfunction "GND_P96") (pintype "power_in"))
      (node (ref "U3") (pin "17") (pinfunction "COMM_17") (pintype "bidirectional"))
      (node (ref "U3") (pin "20") (pinfunction "COMM_20") (pintype "bidirectional"))
      (node (ref "U3") (pin "6") (pinfunction "COML_6") (pintype "bidirectional"))
      (node (ref "U3") (pin "9") (pinfunction "MODE_9") (pintype "bidirectional"))
      (node (ref "U4") (pin "11") (pinfunction "AGND_11") (pintype "bidirectional"))
      (node (ref "U4") (pin "14") (pinfunction "PDWN_14") (pintype "bidirectional"))
      (node (ref "U4") (pin "23") (pinfunction "DRGND_23") (pintype "bidirectional"))
      (node (ref "U4") (pin "3") (pinfunction "SENSE_3") (pintype "bidirectional"))
      (node (ref "U4") (pin "8") (pinfunction "AGND_8") (pintype "bidirectional"))
      (node (ref "U5") (pin "5") (pinfunction "GND_5") (pintype "power_in"))
      (node (ref "U5") (pin "6") (pinfunction "GND_6") (pintype "power_in"))
      (node (ref "U6") (pin "1") (pinfunction "GND_1") (pintype "bidirectional"))
      (node (ref "U7") (pin "2") (pinfunction "GND_2") (pintype "input"))
      (node (ref "U8") (pin "1") (pinfunction "S_1") (pintype "bidirectional"))
      (node (ref "U8") (pin "2") (pinfunction "S_2") (pintype "bidirectional"))
      (node (ref "U8") (pin "3") (pinfunction "S_3") (pintype "bidirectional"))
      (node (ref "U9") (pin "4") (pinfunction "GND_4") (pintype "bidirectional"))
      (node (ref "X2") (pin "G@1") (pinfunction "2_G@1") (pintype "passive"))
      (node (ref "X2") (pin "G@2") (pinfunction "2_G@2") (pintype "passive"))
      (node (ref "X2") (pin "G@3") (pinfunction "2_G@3") (pintype "passive"))
      (node (ref "X2") (pin "G@4") (pinfunction "2_G@4") (pintype "passive"))
      (node (ref "X4") (pin "G@1") (pinfunction "2_G@1") (pintype "passive"))
      (node (ref "X4") (pin "G@2") (pinfunction "2_G@2") (pintype "passive"))
      (node (ref "X4") (pin "G@3") (pinfunction "2_G@3") (pintype "passive"))
      (node (ref "X4") (pin "G@4") (pinfunction "2_G@4") (pintype "passive"))
    )
    (net (code "37") (name "NRST") (class "Default")
      (node (ref "R16") (pin "2") (pinfunction "2_2") (pintype "passive"))
      (node (ref "R17") (pin "1") (pinfunction "1_1") (pintype "passive"))
      (node (ref "U1") (pin "57") (pinfunction "NRST_57") (pintype "input"))
    )
    (net (code "38") (name "NRSTB") (class "Default")
      (node (ref "JP2") (pin "1") (pinfunction "1_1") (pintype "passive"))
      (node (ref "S1") (pin "1") (pinfunction "1_1") (pintype "passive"))
      (node (ref "S1") (pin "2") (pinfunction "2_2") (pintype "passive"))
      (node (ref "U1") (pin "47") (pinfunction "NRSTB_47") (pintype "bidirectional"))
    )
    (net (code "39") (name "Net-(C3-Pad2)") (class "Default")
      (node (ref "C3") (pin "2") (pinfunction "2_2") (pintype "passive"))
      (node (ref "R15") (pin "1") (pinfunction "1_1") (pintype "passive"))
    )
    (net (code "40") (name "Net-(C48-Pad1)") (class "Default")
      (node (ref "C48") (pin "1") (pinfunction "1_1") (pintype "passive"))
      (node (ref "J8") (pin "E1") (pinfunction "SHIELD_E1") (pintype "bidirectional"))
      (node (ref "J8") (pin "E2") (pinfunction "SHIELD_E2") (pintype "bidirectional"))
      (node (ref "J8") (pin "P$1") (pinfunction "SHIELD_P$1") (pintype "bidirectional"))
      (node (ref "J8") (pin "P$2") (pinfunction "SHIELD_P$2") (pintype "bidirectional"))
      (node (ref "J8") (pin "P$3") (pinfunction "SHIELD_P$3") (pintype "bidirectional"))
      (node (ref "J8") (pin "P$4") (pinfunction "SHIELD_P$4") (pintype "bidirectional"))
    )
    (net (code "41") (name "Net-(C67-Pad1)") (class "Default")
      (node (ref "C67") (pin "1") (pinfunction "1_1") (pintype "passive"))
      (node (ref "R44") (pin "1") (pinfunction "1_1") (pintype "passive"))
    )
    (net (code "42") (name "Net-(C68-Pad1)") (class "Default")
      (node (ref "C68") (pin "1") (pinfunction "1_1") (pintype "passive"))
      (node (ref "L11") (pin "2") (pinfunction "2_2") (pintype "passive"))
    )
    (net (code "43") (name "Net-(C85-Pad1)") (class "Default")
      (node (ref "C85") (pin "1") (pinfunction "1_1") (pintype "passive"))
      (node (ref "R46") (pin "1") (pinfunction "1_1") (pintype "passive"))
    )
    (net (code "44") (name "Net-(C86-Pad1)") (class "Default")
      (node (ref "C86") (pin "1") (pinfunction "1_1") (pintype "passive"))
      (node (ref "R47") (pin "1") (pinfunction "1_1") (pintype "passive"))
    )
    (net (code "45") (name "Net-(C90-Pad2)") (class "Default")
      (node (ref "C90") (pin "2") (pinfunction "2_2") (pintype "passive"))
      (node (ref "R52") (pin "1") (pinfunction "1_1") (pintype "passive"))
      (node (ref "R53") (pin "2") (pinfunction "2_2") (pintype "passive"))
    )
    (net (code "46") (name "Net-(C101-Pad1)") (class "Default")
      (node (ref "C101") (pin "1") (pinfunction "1_1") (pintype "passive"))
      (node (ref "C102") (pin "1") (pinfunction "1_1") (pintype "passive"))
      (node (ref "C63") (pin "1") (pinfunction "1_1") (pintype "passive"))
      (node (ref "C64") (pin "1") (pinfunction "1_1") (pintype "passive"))
      (node (ref "C65") (pin "1") (pinfunction "1_1") (pintype "passive"))
      (node (ref "C66") (pin "1") (pinfunction "1_1") (pintype "passive"))
      (node (ref "JP5") (pin "2") (pinfunction "2_2") (pintype "passive"))
      (node (ref "SJ6") (pin "2") (pinfunction "2_2") (pintype "passive"))
      (node (ref "U2") (pin "P103") (pinfunction "VCCO_1_P103") (pintype "input"))
      (node (ref "U2") (pin "P76") (pinfunction "VCCO_1_P76") (pintype "input"))
      (node (ref "U2") (pin "P86") (pinfunction "VCCO_1_P86") (pintype "input"))
    )
    (net (code "47") (name "Net-(D1-A)") (class "Default")
      (node (ref "C89") (pin "2") (pinfunction "2_2") (pintype "passive"))
      (node (ref "D1") (pin "3") (pinfunction "A_3") (pintype "passive"))
      (node (ref "R52") (pin "2") (pinfunction "2_2") (pintype "passive"))
      (node (ref "U3") (pin "10") (pinfunction "GAIN_10") (pintype "bidirectional"))
    )
    (net (code "48") (name "Net-(D2-PadC)") (class "Default")
      (node (ref "D2") (pin "C") (pinfunction "C_C") (pintype "passive"))
      (node (ref "R58") (pin "2") (pinfunction "2_2") (pintype "passive"))
    )
    (net (code "49") (name "Net-(D4-PadC)") (class "Default")
      (node (ref "D4") (pin "C") (pinfunction "C_C") (pintype "passive"))
      (node (ref "R39") (pin "1") (pinfunction "1_1") (pintype "passive"))
    )
    (net (code "50") (name "Net-(D5-PadC)") (class "Default")
      (node (ref "D5") (pin "C") (pinfunction "C_C") (pintype "passive"))
      (node (ref "R40") (pin "1") (pinfunction "1_1") (pintype "passive"))
    )
    (net (code "51") (name "Net-(D6-PadC)") (class "Default")
      (node (ref "D6") (pin "C") (pinfunction "C_C") (pintype "passive"))
      (node (ref "R41") (pin "1") (pinfunction "1_1") (pintype "passive"))
    )
    (net (code "52") (name "Net-(D7-PadC)") (class "Default")
      (node (ref "D7") (pin "C") (pinfunction "C_C") (pintype "passive"))
      (node (ref "R42") (pin "1") (pinfunction "1_1") (pintype "passive"))
    )
    (net (code "53") (name "Net-(D9-PadC)") (class "Default")
      (node (ref "D9") (pin "C") (pinfunction "C_C") (pintype "passive"))
      (node (ref "R57") (pin "2") (pinfunction "2_2") (pintype "passive"))
    )
    (net (code "54") (name "Net-(J3-Pad3)") (class "Default")
      (node (ref "J3") (pin "3") (pinfunction "3_3") (pintype "passive"))
      (node (ref "R21") (pin "1") (pinfunction "1_1") (pintype "passive"))
    )
    (net (code "55") (name "Net-(J3-Pad15)") (class "Default")
      (node (ref "J3") (pin "15") (pinfunction "15_15") (pintype "passive"))
      (node (ref "R16") (pin "1") (pinfunction "1_1") (pintype "passive"))
    )
    (net (code "56") (name "Net-(J4-TCK)") (class "Default")
      (node (ref "J4") (pin "3") (pinfunction "TCK_3") (pintype "passive"))
      (node (ref "U2") (pin "P109") (pinfunction "TCK_P109") (pintype "input"))
    )
    (net (code "57") (name "Net-(J4-TDI)") (class "Default")
      (node (ref "J4") (pin "5") (pinfunction "TDI_5") (pintype "passive"))
      (node (ref "U2") (pin "P110") (pinfunction "TDI_P110") (pintype "input"))
    )
    (net (code "58") (name "Net-(J4-TDO)") (class "Default")
      (node (ref "J4") (pin "4") (pinfunction "TDO_4") (pintype "passive"))
      (node (ref "U2") (pin "P106") (pinfunction "TDO_P106") (pintype "output"))
    )
    (net (code "59") (name "Net-(J4-TMS)") (class "Default")
      (node (ref "J4") (pin "6") (pinfunction "TMS_6") (pintype "passive"))
      (node (ref "U2") (pin "P107") (pinfunction "TMS_P107") (pintype "input"))
    )
    (net (code "60") (name "Net-(J6-Pad1)") (class "Default")
      (node (ref "J6") (pin "1") (pinfunction "1_1") (pintype "passive"))
      (node (ref "R59") (pin "2") (pinfunction "2_2") (pintype "passive"))
      (node (ref "R61") (pin "1") (pinfunction "1_1") (pintype "passive"))
    )
    (net (code "61") (name "Net-(J6-Pad4)") (class "Default")
      (node (ref "J6") (pin "4") (pinfunction "4_4") (pintype "passive"))
      (node (ref "R60") (pin "1") (pinfunction "1_1") (pintype "passive"))
    )
    (net (code "62") (name "Net-(J7-Pad1)") (class "Default")
      (node (ref "J7") (pin "1") (pinfunction "1_1") (pintype "passive"))
      (node (ref "R62") (pin "2") (pinfunction "2_2") (pintype "passive"))
    )
    (net (code "63") (name "Net-(J7-Pad4)") (class "Default")
      (node (ref "J7") (pin "4") (pinfunction "4_4") (pintype "passive"))
      (node (ref "R63") (pin "2") (pinfunction "2_2") (pintype "passive"))
    )
    (net (code "64") (name "Net-(J8-VCC)") (class "Default")
      (node (ref "J8") (pin "1") (pinfunction "VCC_1") (pintype "bidirectional"))
      (node (ref "SJ1") (pin "1") (pinfunction "1_1") (pintype "passive"))
      (node (ref "U6") (pin "4") (pinfunction "VCC_4") (pintype "bidirectional"))
    )
    (net (code "65") (name "Net-(JP3-Pad1)") (class "Default")
      (node (ref "JP3") (pin "1") (pinfunction "1_1") (pintype "passive"))
      (node (ref "SJ1") (pin "3") (pinfunction "3_3") (pintype "passive"))
    )
    (net (code "66") (name "Net-(Q1-X1)") (class "Default")
      (node (ref "C50") (pin "2") (pinfunction "2_2") (pintype "passive"))
      (node (ref "Q1") (pin "1") (pinfunction "X1_1") (pintype "bidirectional"))
      (node (ref "U1") (pin "74") (pinfunction "XOUT_74") (pintype "output"))
    )
    (net (code "67") (name "Net-(Q1-X2)") (class "Default")
      (node (ref "C51") (pin "2") (pinfunction "2_2") (pintype "passive"))
      (node (ref "Q1") (pin "3") (pinfunction "X2_3") (pintype "bidirectional"))
      (node (ref "U1") (pin "75") (pinfunction "XIN_75") (pintype "input"))
    )
    (net (code "68") (name "Net-(T1-D)") (class "Default")
      (node (ref "C47") (pin "1") (pinfunction "1_1") (pintype "passive"))
      (node (ref "L4") (pin "1") (pinfunction "1_1") (pintype "passive"))
      (node (ref "L5") (pin "1") (pinfunction "1_1") (pintype "passive"))
      (node (ref "T1") (pin "1") (pinfunction "D_1") (pintype "passive"))
    )
    (net (code "69") (name "Net-(T1-G)") (class "Default")
      (node (ref "C122") (pin "1") (pinfunction "1_1") (pintype "passive"))
      (node (ref "R31") (pin "1") (pinfunction "1_1") (pintype "passive"))
      (node (ref "R79") (pin "2") (pinfunction "2_2") (pintype "passive"))
      (node (ref "T1") (pin "3") (pinfunction "G_3") (pintype "passive"))
    )
    (net (code "70") (name "Net-(T1-S)") (class "Default")
      (node (ref "C46") (pin "1") (pinfunction "1_1") (pintype "passive"))
      (node (ref "L6") (pin "1") (pinfunction "1_1") (pintype "passive"))
      (node (ref "R31") (pin "2") (pinfunction "2_2") (pintype "passive"))
      (node (ref "SJ1") (pin "2") (pinfunction "2_2") (pintype "passive"))
      (node (ref "T1") (pin "2") (pinfunction "S_2") (pintype "passive"))
    )
    (net (code "71") (name "Net-(T2-D)") (class "Default")
      (node (ref "R79") (pin "1") (pinfunction "1_1") (pintype "passive"))
      (node (ref "T2") (pin "1") (pinfunction "D_1") (pintype "passive"))
    )
    (net (code "72") (name "Net-(T4-G)") (class "Default")
      (node (ref "R43") (pin "1") (pinfunction "1_1") (pintype "passive"))
      (node (ref "R78") (pin "1") (pinfunction "1_1") (pintype "passive"))
      (node (ref "T4") (pin "3") (pinfunction "G_3") (pintype "passive"))
    )
    (net (code "73") (name "Net-(U1-DFSDM)") (class "Default")
      (node (ref "R27") (pin "1") (pinfunction "1_1") (pintype "passive"))
      (node (ref "U1") (pin "80") (pinfunction "DFSDM_80") (pintype "bidirectional"))
    )
    (net (code "74") (name "Net-(U1-DFSDP)") (class "Default")
      (node (ref "R28") (pin "1") (pinfunction "1_1") (pintype "passive"))
      (node (ref "U1") (pin "81") (pinfunction "DFSDP_81") (pintype "bidirectional"))
    )
    (net (code "75") (name "Net-(U1-PA6{slash}PGMM2)") (class "Default")
      (node (ref "D9") (pin "A") (pinfunction "A_A") (pintype "passive"))
      (node (ref "U1") (pin "32") (pinfunction "PA6/PGMM2_32") (pintype "bidirectional"))
    )
    (net (code "76") (name "Net-(U1-PA7{slash}PGMM3)") (class "Default")
      (node (ref "D2") (pin "A") (pinfunction "A_A") (pintype "passive"))
      (node (ref "U1") (pin "33") (pinfunction "PA7/PGMM3_33") (pintype "bidirectional"))
    )
    (net (code "77") (name "Net-(U1-PA11{slash}PGMD3)") (class "Default")
      (node (ref "JP1") (pin "3") (pinfunction "3_3") (pintype "passive"))
      (node (ref "U1") (pin "40") (pinfunction "PA11/PGMD3_40") (pintype "bidirectional"))
    )
    (net (code "78") (name "Net-(U1-PA12{slash}PGMD4)") (class "Default")
      (node (ref "JP1") (pin "2") (pinfunction "2_2") (pintype "passive"))
      (node (ref "U1") (pin "41") (pinfunction "PA12/PGMD4_41") (pintype "bidirectional"))
    )
    (net (code "79") (name "Net-(U1-PA20{slash}PGMD12)") (class "Default")
      (node (ref "R2") (pin "1") (pinfunction "1_1") (pintype "passive"))
      (node (ref "U1") (pin "19") (pinfunction "PA20/PGMD12_19") (pintype "bidirectional"))
    )
    (net (code "80") (name "Net-(U1-PA21{slash}PGMD13)") (class "Default")
      (node (ref "R10") (pin "1") (pinfunction "1_1") (pintype "passive"))
      (node (ref "U1") (pin "20") (pinfunction "PA21/PGMD13_20") (pintype "bidirectional"))
    )
    (net (code "81") (name "Net-(U1-PA27)") (class "Default")
      (node (ref "R14") (pin "1") (pinfunction "1_1") (pintype "passive"))
      (node (ref "U1") (pin "96") (pinfunction "PA27_96") (pintype "bidirectional"))
    )
    (net (code "82") (name "Net-(U1-PB24)") (class "Default")
      (node (ref "R1") (pin "1") (pinfunction "1_1") (pintype "passive"))
      (node (ref "U1") (pin "58") (pinfunction "PB24_58") (pintype "bidirectional"))
    )
    (net (code "83") (name "Net-(U1-VBG)") (class "Default")
      (node (ref "C33") (pin "1") (pinfunction "1_1") (pintype "passive"))
      (node (ref "R29") (pin "2") (pinfunction "2_2") (pintype "passive"))
      (node (ref "U1") (pin "78") (pinfunction "VBG_78") (pintype "bidirectional"))
    )
    (net (code "84") (name "Net-(U1-VDDCORE)") (class "Default")
      (node (ref "C10") (pin "1") (pinfunction "1_1") (pintype "passive"))
      (node (ref "C11") (pin "1") (pinfunction "1_1") (pintype "passive"))
      (node (ref "C12") (pin "1") (pinfunction "1_1") (pintype "passive"))
      (node (ref "C123") (pin "1") (pinfunction "1_1") (pintype "passive"))
      (node (ref "C19") (pin "1") (pinfunction "1_1") (pintype "passive"))
      (node (ref "C5") (pin "1") (pinfunction "1_1") (pintype "passive"))
      (node (ref "C7") (pin "1") (pinfunction "1_1") (pintype "passive"))
      (node (ref "C8") (pin "1") (pinfunction "1_1") (pintype "passive"))
      (node (ref "C9") (pin "1") (pinfunction "1_1") (pintype "passive"))
      (node (ref "U1") (pin "34") (pinfunction "VDDCORE_34") (pintype "power_in"))
      (node (ref "U1") (pin "52") (pinfunction "VDDOUT_52") (pintype "power_in"))
      (node (ref "U1") (pin "59") (pinfunction "VDDCORE_5_59") (pintype "power_in"))
      (node (ref "U1") (pin "73") (pinfunction "VDDPLL_73") (pintype "power_in"))
      (node (ref "U1") (pin "83") (pinfunction "VDDCORE_3_83") (pintype "power_in"))
      (node (ref "U1") (pin "87") (pinfunction "VDDCORE_2_87") (pintype "power_in"))
      (node (ref "U1") (pin "9") (pinfunction "VDDCORE_4_9") (pintype "power_in"))
    )
    (net (code "85") (name "Net-(U1-VDDUTMI)") (class "Default")
      (node (ref "C4") (pin "1") (pinfunction "1_1") (pintype "passive"))
      (node (ref "L1") (pin "2") (pinfunction "2_2") (pintype "passive"))
      (node (ref "R15") (pin "2") (pinfunction "2_2") (pintype "passive"))
      (node (ref "U1") (pin "79") (pinfunction "VDDUTMI_79") (pintype "power_in"))
    )
    (net (code "86") (name "Net-(U2A-IO_L1N_VREF_0)") (class "Default")
      (node (ref "D4") (pin "A") (pinfunction "A_A") (pintype "passive"))
      (node (ref "U2") (pin "P143") (pinfunction "IO_L1N_VREF_0_P143") (pintype "bidirectional"))
    )
    (net (code "87") (name "Net-(U2A-IO_L1P_HSWAPEN_0)") (class "Default")
      (node (ref "R68") (pin "1") (pinfunction "1_1") (pintype "passive"))
      (node (ref "U2") (pin "P144") (pinfunction "IO_L1P_HSWAPEN_0_P144") (pintype "bidirectional"))
    )
    (net (code "88") (name "Net-(U2A-IO_L2N_0)") (class "Default")
      (node (ref "D6") (pin "A") (pinfunction "A_A") (pintype "passive"))
      (node (ref "U2") (pin "P141") (pinfunction "IO_L2N_0_P141") (pintype "bidirectional"))
    )
    (net (code "89") (name "Net-(U2A-IO_L2P_0)") (class "Default")
      (node (ref "D5") (pin "A") (pinfunction "A_A") (pintype "passive"))
      (node (ref "U2") (pin "P142") (pinfunction "IO_L2P_0_P142") (pintype "bidirectional"))
    )
    (net (code "90") (name "Net-(U2A-IO_L3P_0)") (class "Default")
      (node (ref "D7") (pin "A") (pinfunction "A_A") (pintype "passive"))
      (node (ref "U2") (pin "P140") (pinfunction "IO_L3P_0_P140") (pintype "bidirectional"))
    )
    (net (code "91") (name "Net-(U2A-IO_L62N_VREF_0)") (class "Default")
      (node (ref "J5") (pin "1") (pinfunction "1_1") (pintype "passive"))
      (node (ref "U2") (pin "P120") (pinfunction "IO_L62N_VREF_0_P120") (pintype "bidirectional"))
    )
    (net (code "92") (name "Net-(U2A-IO_L63N_SCP6_0)") (class "Default")
      (node (ref "J5") (pin "3") (pinfunction "3_3") (pintype "passive"))
      (node (ref "U2") (pin "P118") (pinfunction "IO_L63N_SCP6_0_P118") (pintype "bidirectional"))
    )
    (net (code "93") (name "Net-(U2A-IO_L63P_SCP7_0)") (class "Default")
      (node (ref "J5") (pin "2") (pinfunction "2_2") (pintype "passive"))
      (node (ref "U2") (pin "P119") (pinfunction "IO_L63P_SCP7_0_P119") (pintype "bidirectional"))
    )
    (net (code "94") (name "Net-(U2A-IO_L64N_SCP4_0)") (class "Default")
      (node (ref "J5") (pin "5") (pinfunction "5_5") (pintype "passive"))
      (node (ref "U2") (pin "P116") (pinfunction "IO_L64N_SCP4_0_P116") (pintype "bidirectional"))
    )
    (net (code "95") (name "Net-(U2A-IO_L64P_SCP5_0)") (class "Default")
      (node (ref "J5") (pin "4") (pinfunction "4_4") (pintype "passive"))
      (node (ref "U2") (pin "P117") (pinfunction "IO_L64P_SCP5_0_P117") (pintype "bidirectional"))
    )
    (net (code "96") (name "Net-(U2A-IO_L65N_SCP2_0)") (class "Default")
      (node (ref "J5") (pin "7") (pinfunction "7_7") (pintype "passive"))
      (node (ref "U2") (pin "P114") (pinfunction "IO_L65N_SCP2_0_P114") (pintype "bidirectional"))
    )
    (net (code "97") (name "Net-(U2A-IO_L65P_SCP3_0)") (class "Default")
      (node (ref "J5") (pin "6") (pinfunction "6_6") (pintype "passive"))
      (node (ref "U2") (pin "P115") (pinfunction "IO_L65P_SCP3_0_P115") (pintype "bidirectional"))
    )
    (net (code "98") (name "Net-(U2A-IO_L66N_SCP0_0)") (class "Default")
      (node (ref "J5") (pin "9") (pinfunction "9_9") (pintype "passive"))
      (node (ref "U2") (pin "P111") (pinfunction "IO_L66N_SCP0_0_P111") (pintype "bidirectional"))
    )
    (net (code "99") (name "Net-(U2A-IO_L66P_SCP1_0)") (class "Default")
      (node (ref "J5") (pin "8") (pinfunction "8_8") (pintype "passive"))
      (node (ref "U2") (pin "P112") (pinfunction "IO_L66P_SCP1_0_P112") (pintype "bidirectional"))
    )
    (net (code "100") (name "Net-(U2B-IO_L1P_1)") (class "Default")
      (node (ref "JP18") (pin "1") (pinfunction "1_1") (pintype "passive"))
      (node (ref "U2") (pin "P105") (pinfunction "IO_L1P_1_P105") (pintype "bidirectional"))
    )
    (net (code "101") (name "Net-(U2C-IO_L1N_M0_CMPMISO_2)") (class "Default")
      (node (ref "R7") (pin "2") (pinfunction "2_2") (pintype "passive"))
      (node (ref "R8") (pin "2") (pinfunction "2_2") (pintype "passive"))
      (node (ref "U2") (pin "P69") (pinfunction "IO_L1N_M0_CMPMISO_2_P69") (pintype "bidirectional"))
    )
    (net (code "102") (name "Net-(U2C-IO_L1P_CCLK_2)") (class "Default")
      (node (ref "R5") (pin "1") (pinfunction "1_1") (pintype "passive"))
      (node (ref "R70") (pin "2") (pinfunction "2_2") (pintype "passive"))
      (node (ref "R71") (pin "1") (pinfunction "1_1") (pintype "passive"))
      (node (ref "U2") (pin "P70") (pinfunction "IO_L1P_CCLK_2_P70") (pintype "bidirectional"))
      (node (ref "U9") (pin "6") (pinfunction "SCK_6") (pintype "bidirectional"))
    )
    (net (code "103") (name "Net-(U2C-IO_L3N_MOSI_CSI_B_MISO0_2)") (class "Default")
      (node (ref "U2") (pin "P64") (pinfunction "IO_L3N_MOSI_CSI_B_MISO0_2_P64") (pintype "bidirectional"))
      (node (ref "U9") (pin "5") (pinfunction "MOSI_5") (pintype "bidirectional"))
    )
    (net (code "104") (name "Net-(U2C-IO_L3P_D0_DIN_MISO_MISO1_2)") (class "Default")
      (node (ref "R22") (pin "2") (pinfunction "2_2") (pintype "passive"))
      (node (ref "R6") (pin "2") (pinfunction "2_2") (pintype "passive"))
      (node (ref "U2") (pin "P65") (pinfunction "IO_L3P_D0_DIN_MISO_MISO1_2_P65") (pintype "bidirectional"))
    )
    (net (code "105") (name "Net-(U2C-IO_L13P_M1_2)") (class "Default")
      (node (ref "R3") (pin "2") (pinfunction "2_2") (pintype "passive"))
      (node (ref "R4") (pin "2") (pinfunction "2_2") (pintype "passive"))
      (node (ref "U2") (pin "P60") (pinfunction "IO_L13P_M1_2_P60") (pintype "bidirectional"))
    )
    (net (code "106") (name "Net-(U2C-IO_L65N_CSO_B_2)") (class "Default")
      (node (ref "R9") (pin "1") (pinfunction "1_1") (pintype "passive"))
      (node (ref "U2") (pin "P38") (pinfunction "IO_L65N_CSO_B_2_P38") (pintype "bidirectional"))
      (node (ref "U9") (pin "1") (pinfunction "CS_1") (pintype "bidirectional"))
    )
    (net (code "107") (name "Net-(U3-ENBL)") (class "Default")
      (node (ref "C80") (pin "2") (pinfunction "2_2") (pintype "passive"))
      (node (ref "C81") (pin "2") (pinfunction "2_2") (pintype "passive"))
      (node (ref "C82") (pin "2") (pinfunction "2_2") (pintype "passive"))
      (node (ref "L8") (pin "2") (pinfunction "2_2") (pintype "passive"))
      (node (ref "U3") (pin "18") (pinfunction "ENBV_18") (pintype "bidirectional"))
      (node (ref "U3") (pin "19") (pinfunction "ENBL_19") (pintype "bidirectional"))
      (node (ref "U3") (pin "3") (pinfunction "VPSL_3") (pintype "bidirectional"))
    )
    (net (code "108") (name "Net-(U3-INH)") (class "Default")
      (node (ref "C67") (pin "2") (pinfunction "2_2") (pintype "passive"))
      (node (ref "C68") (pin "2") (pinfunction "2_2") (pintype "passive"))
      (node (ref "C69") (pin "2") (pinfunction "2_2") (pintype "passive"))
      (node (ref "U3") (pin "2") (pinfunction "INH_2") (pintype "bidirectional"))
    )
    (net (code "109") (name "Net-(U3-LMD)") (class "Default")
      (node (ref "C79") (pin "2") (pinfunction "2_2") (pintype "passive"))
      (node (ref "U3") (pin "1") (pinfunction "LMD_1") (pintype "bidirectional"))
    )
    (net (code "110") (name "Net-(U3-LON)") (class "Default")
      (node (ref "C70") (pin "2") (pinfunction "2_2") (pintype "passive"))
      (node (ref "R44") (pin "2") (pinfunction "2_2") (pintype "passive"))
      (node (ref "U3") (pin "4") (pinfunction "LON_4") (pintype "bidirectional"))
    )
    (net (code "111") (name "Net-(U3-LOP)") (class "Default")
      (node (ref "C71") (pin "2") (pinfunction "2_2") (pintype "passive"))
      (node (ref "U3") (pin "5") (pinfunction "LOP_5") (pintype "bidirectional"))
    )
    (net (code "112") (name "Net-(U3-RCLMP)") (class "Default")
      (node (ref "C74") (pin "2") (pinfunction "2_2") (pintype "passive"))
      (node (ref "C75") (pin "2") (pinfunction "2_2") (pintype "passive"))
      (node (ref "R45") (pin "2") (pinfunction "2_2") (pintype "passive"))
      (node (ref "U3") (pin "12") (pinfunction "RCLMP_12") (pintype "bidirectional"))
    )
    (net (code "113") (name "Net-(U3-VCM)") (class "Default")
      (node (ref "C72") (pin "2") (pinfunction "2_2") (pintype "passive"))
      (node (ref "C73") (pin "2") (pinfunction "2_2") (pintype "passive"))
      (node (ref "U3") (pin "11") (pinfunction "VCM_11") (pintype "bidirectional"))
    )
    (net (code "114") (name "Net-(U3-VIN)") (class "Default")
      (node (ref "C70") (pin "1") (pinfunction "1_1") (pintype "passive"))
      (node (ref "U3") (pin "8") (pinfunction "VIN_8") (pintype "bidirectional"))
    )
    (net (code "115") (name "Net-(U3-VIP)") (class "Default")
      (node (ref "C71") (pin "1") (pinfunction "1_1") (pintype "passive"))
      (node (ref "U3") (pin "7") (pinfunction "VIP_7") (pintype "bidirectional"))
    )
    (net (code "116") (name "Net-(U3-VOH)") (class "Default")
      (node (ref "C85") (pin "2") (pinfunction "2_2") (pintype "passive"))
      (node (ref "U3") (pin "15") (pinfunction "VOH_15") (pintype "bidirectional"))
    )
    (net (code "117") (name "Net-(U3-VOL)") (class "Default")
      (node (ref "C86") (pin "2") (pinfunction "2_2") (pintype "passive"))
      (node (ref "U3") (pin "16") (pinfunction "VOL_16") (pintype "bidirectional"))
    )
    (net (code "118") (name "Net-(U3-VPOS)") (class "Default")
      (node (ref "C76") (pin "2") (pinfunction "2_2") (pintype "passive"))
      (node (ref "C77") (pin "2") (pinfunction "2_2") (pintype "passive"))
      (node (ref "C78") (pin "2") (pinfunction "2_2") (pintype "passive"))
      (node (ref "L7") (pin "2") (pinfunction "2_2") (pintype "passive"))
      (node (ref "U3") (pin "14") (pinfunction "VPOS_14") (pintype "bidirectional"))
    )
    (net (code "119") (name "Net-(U4-MODE)") (class "Default")
      (node (ref "R55") (pin "1") (pinfunction "1_1") (pintype "passive"))
      (node (ref "R56") (pin "2") (pinfunction "2_2") (pintype "passive"))
      (node (ref "U4") (pin "2") (pinfunction "MODE_2") (pintype "bidirectional"))
    )
    (net (code "120") (name "Net-(U4-REFB)") (class "Default")
      (node (ref "C91") (pin "2") (pinfunction "2_2") (pintype "passive"))
      (node (ref "C92") (pin "2") (pinfunction "2_2") (pintype "passive"))
      (node (ref "C93") (pin "1") (pinfunction "1_1") (pintype "passive"))
      (node (ref "U4") (pin "5") (pinfunction "REFB_5") (pintype "bidirectional"))
    )
    (net (code "121") (name "Net-(U4-REFT)") (class "Default")
      (node (ref "C91") (pin "1") (pinfunction "1_1") (pintype "passive"))
      (node (ref "C92") (pin "1") (pinfunction "1_1") (pintype "passive"))
      (node (ref "C94") (pin "1") (pinfunction "1_1") (pintype "passive"))
      (node (ref "U4") (pin "6") (pinfunction "REFT_6") (pintype "bidirectional"))
    )
    (net (code "122") (name "Net-(U4-VIN+)") (class "Default")
      (node (ref "C87") (pin "2") (pinfunction "2_2") (pintype "passive"))
      (node (ref "R46") (pin "2") (pinfunction "2_2") (pintype "passive"))
      (node (ref "R48") (pin "1") (pinfunction "1_1") (pintype "passive"))
      (node (ref "R49") (pin "1") (pinfunction "1_1") (pintype "passive"))
      (node (ref "U4") (pin "9") (pinfunction "VIN+_9") (pintype "bidirectional"))
    )
    (net (code "123") (name "Net-(U4-VIN-)") (class "Default")
      (node (ref "C88") (pin "1") (pinfunction "1_1") (pintype "passive"))
      (node (ref "R47") (pin "2") (pinfunction "2_2") (pintype "passive"))
      (node (ref "R50") (pin "2") (pinfunction "2_2") (pintype "passive"))
      (node (ref "R51") (pin "2") (pinfunction "2_2") (pintype "passive"))
      (node (ref "U4") (pin "10") (pinfunction "VIN-_10") (pintype "bidirectional"))
    )
    (net (code "124") (name "Net-(U4-VREF)") (class "Default")
      (node (ref "C95") (pin "2") (pinfunction "2_2") (pintype "passive"))
      (node (ref "C96") (pin "2") (pinfunction "2_2") (pintype "passive"))
      (node (ref "U4") (pin "4") (pinfunction "VREF_4") (pintype "bidirectional"))
    )
    (net (code "125") (name "Net-(U5-SW1)") (class "Default")
      (node (ref "L2") (pin "1") (pinfunction "1_1") (pintype "passive"))
      (node (ref "U5") (pin "4") (pinfunction "SW1_4") (pintype "output"))
    )
    (net (code "126") (name "Net-(U5-SW2)") (class "Default")
      (node (ref "L3") (pin "1") (pinfunction "1_1") (pintype "passive"))
      (node (ref "U5") (pin "8") (pinfunction "SW2_8") (pintype "output"))
    )
    (net (code "127") (name "Net-(U5-VFB1)") (class "Default")
      (node (ref "R24") (pin "2") (pinfunction "2_2") (pintype "passive"))
      (node (ref "R25") (pin "2") (pinfunction "2_2") (pintype "passive"))
      (node (ref "U5") (pin "1") (pinfunction "VFB1_1") (pintype "input"))
    )
    (net (code "128") (name "Net-(U5-VFB2)") (class "Default")
      (node (ref "R26") (pin "2") (pinfunction "2_2") (pintype "passive"))
      (node (ref "R30") (pin "2") (pinfunction "2_2") (pintype "passive"))
      (node (ref "U5") (pin "10") (pinfunction "VFB2_10") (pintype "input"))
    )
    (net (code "129") (name "Net-(U8-G)") (class "Default")
      (node (ref "JP8") (pin "2") (pinfunction "2_2") (pintype "passive"))
      (node (ref "R37") (pin "1") (pinfunction "1_1") (pintype "passive"))
      (node (ref "R65") (pin "1") (pinfunction "1_1") (pintype "passive"))
      (node (ref "U8") (pin "4") (pinfunction "G_4") (pintype "bidirectional"))
    )
    (net (code "130") (name "Net-(U9-MISO)") (class "Default")
      (node (ref "R22") (pin "1") (pinfunction "1_1") (pintype "passive"))
      (node (ref "U9") (pin "2") (pinfunction "MISO_2") (pintype "bidirectional"))
    )
    (net (code "131") (name "Net-(U10-BP)") (class "Default")
      (node (ref "C112") (pin "2") (pinfunction "2_2") (pintype "passive"))
      (node (ref "U10") (pin "4") (pinfunction "BP_4") (pintype "input"))
    )
    (net (code "132") (name "Net-(U10-EN)") (class "Default")
      (node (ref "C110") (pin "2") (pinfunction "2_2") (pintype "passive"))
      (node (ref "L9") (pin "2") (pinfunction "2_2") (pintype "passive"))
      (node (ref "U10") (pin "1") (pinfunction "IN_1") (pintype "input"))
      (node (ref "U10") (pin "3") (pinfunction "EN_3") (pintype "input"))
    )
    (net (code "133") (name "PWRON") (class "Default")
      (node (ref "R23") (pin "1") (pinfunction "1_1") (pintype "passive"))
      (node (ref "T2") (pin "3") (pinfunction "G_3") (pintype "passive"))
      (node (ref "U1") (pin "85") (pinfunction "PA29_85") (pintype "bidirectional"))
    )
    (net (code "134") (name "RXD0") (class "Default")
      (node (ref "U1") (pin "18") (pinfunction "PA19/PGMD11_18") (pintype "bidirectional"))
      (node (ref "U2") (pin "P134") (pinfunction "IO_L34P_GCLK19_0_P134") (pintype "bidirectional"))
    )
    (net (code "135") (name "RXD2") (class "Default")
      (node (ref "U1") (pin "21") (pinfunction "PA23/PGMD15_21") (pintype "bidirectional"))
      (node (ref "U2") (pin "P132") (pinfunction "IO_L35P_GCLK17_0_P132") (pintype "bidirectional"))
    )
    (net (code "136") (name "SAM_CS0") (class "Default")
      (node (ref "U1") (pin "13") (pinfunction "PA16/PGMD8_13") (pintype "bidirectional"))
      (node (ref "U2") (pin "P139") (pinfunction "IO_L3N_0_P139") (pintype "bidirectional"))
    )
    (net (code "137") (name "SAM_CS1") (class "Default")
      (node (ref "U1") (pin "26") (pinfunction "PA0/PGMNCMD_26") (pintype "bidirectional"))
      (node (ref "U2") (pin "P127") (pinfunction "IO_L36P_GCLK15_0_P127") (pintype "bidirectional"))
    )
    (net (code "138") (name "SAM_CS2") (class "Default")
      (node (ref "U1") (pin "27") (pinfunction "PA1/PGMRDY_27") (pintype "bidirectional"))
    )
    (net (code "139") (name "SAM_MISO") (class "Default")
      (node (ref "U1") (pin "10") (pinfunction "PA13/PGMD5_10") (pintype "bidirectional"))
      (node (ref "U2") (pin "P50") (pinfunction "IO_L31N_GCLK30_D15_2_P50") (pintype "bidirectional"))
    )
    (net (code "140") (name "SAM_MOSI") (class "Default")
      (node (ref "R6") (pin "1") (pinfunction "1_1") (pintype "passive"))
      (node (ref "U1") (pin "11") (pinfunction "PA14/PGMD6_11") (pintype "bidirectional"))
    )
    (net (code "141") (name "SAM_PDIC") (class "Default")
      (node (ref "R36") (pin "2") (pinfunction "2_2") (pintype "passive"))
      (node (ref "U1") (pin "23") (pinfunction "PA24_23") (pintype "bidirectional"))
    )
    (net (code "142") (name "SAM_PDID") (class "Default")
      (node (ref "R10") (pin "2") (pinfunction "2_2") (pintype "passive"))
      (node (ref "R2") (pin "2") (pinfunction "2_2") (pintype "passive"))
      (node (ref "R35") (pin "2") (pinfunction "2_2") (pintype "passive"))
    )
    (net (code "143") (name "SAM_SCK") (class "Default")
      (node (ref "R5") (pin "2") (pinfunction "2_2") (pintype "passive"))
      (node (ref "U1") (pin "12") (pinfunction "PA15/PGMD7_12") (pintype "bidirectional"))
    )
    (net (code "144") (name "SC_AUX1") (class "Default")
      (node (ref "J7") (pin "7") (pinfunction "7_7") (pintype "passive"))
      (node (ref "U1") (pin "30") (pinfunction "PA4/PGMM0_30") (pintype "bidirectional"))
      (node (ref "U2") (pin "P124") (pinfunction "IO_L37P_GCLK13_0_P124") (pintype "bidirectional"))
    )
    (net (code "145") (name "SC_AUX2") (class "Default")
      (node (ref "J7") (pin "8") (pinfunction "8_8") (pintype "passive"))
      (node (ref "U1") (pin "31") (pinfunction "PA5/PGMM1_31") (pintype "bidirectional"))
      (node (ref "U2") (pin "P123") (pinfunction "IO_L37N_GCLK12_0_P123") (pintype "bidirectional"))
    )
    (net (code "146") (name "SC_PRESENT") (class "Default")
      (node (ref "R63") (pin "1") (pinfunction "1_1") (pintype "passive"))
      (node (ref "U1") (pin "28") (pinfunction "PA2/PGMNOE_28") (pintype "bidirectional"))
    )
    (net (code "147") (name "SC_RESET") (class "Default")
      (node (ref "J7") (pin "3") (pinfunction "3_3") (pintype "passive"))
      (node (ref "U1") (pin "29") (pinfunction "PA3/PGMNVALID_29") (pintype "bidirectional"))
      (node (ref "U2") (pin "P126") (pinfunction "IO_L36N_GCLK14_0_P126") (pintype "bidirectional"))
    )
    (net (code "148") (name "TARGET_NRST") (class "Default")
      (node (ref "U1") (pin "14") (pinfunction "PA17/PGMD9_14") (pintype "bidirectional"))
      (node (ref "U2") (pin "P138") (pinfunction "IO_L4P_0_P138") (pintype "bidirectional"))
    )
    (net (code "149") (name "TCK") (class "Default")
      (node (ref "J3") (pin "11") (pinfunction "11_11") (pintype "passive"))
      (node (ref "J3") (pin "9") (pinfunction "9_9") (pintype "passive"))
      (node (ref "R18") (pin "1") (pinfunction "1_1") (pintype "passive"))
      (node (ref "U1") (pin "56") (pinfunction "TCK/SWCLK_56") (pintype "input"))
    )
    (net (code "150") (name "TDI") (class "Default")
      (node (ref "J3") (pin "5") (pinfunction "5_5") (pintype "passive"))
      (node (ref "R20") (pin "1") (pinfunction "1_1") (pintype "passive"))
      (node (ref "U1") (pin "51") (pinfunction "TDI_51") (pintype "input"))
    )
    (net (code "151") (name "TDO") (class "Default")
      (node (ref "J3") (pin "13") (pinfunction "13_13") (pintype "passive"))
      (node (ref "U1") (pin "54") (pinfunction "TDO/TRACESWO_54") (pintype "output"))
    )
    (net (code "152") (name "THS1") (class "Default")
      (node (ref "J1") (pin "4") (pinfunction "4_4") (pintype "passive"))
      (node (ref "JP9") (pin "3") (pinfunction "3_3") (pintype "passive"))
      (node (ref "U2") (pin "P93") (pinfunction "IO_L41P_GCLK9_IRDY1_1_P93") (pintype "bidirectional"))
    )
    (net (code "153") (name "THS2") (class "Default")
      (node (ref "J1") (pin "6") (pinfunction "6_6") (pintype "passive"))
      (node (ref "JP9") (pin "2") (pinfunction "2_2") (pintype "passive"))
      (node (ref "U2") (pin "P95") (pinfunction "IO_L40P_GCLK11_1_P95") (pintype "bidirectional"))
    )
    (net (code "154") (name "TIO1") (class "Default")
      (node (ref "J1") (pin "10") (pinfunction "10_10") (pintype "passive"))
      (node (ref "JP9") (pin "6") (pinfunction "6_6") (pintype "passive"))
      (node (ref "U2") (pin "P87") (pinfunction "IO_L42N_GCLK6_TRDY1_1_P87") (pintype "bidirectional"))
    )
    (net (code "155") (name "TIO2") (class "Default")
      (node (ref "J1") (pin "12") (pinfunction "12_12") (pintype "passive"))
      (node (ref "JP9") (pin "7") (pinfunction "7_7") (pintype "passive"))
      (node (ref "U2") (pin "P84") (pinfunction "IO_L43N_GCLK4_1_P84") (pintype "bidirectional"))
    )
    (net (code "156") (name "TIO3") (class "Default")
      (node (ref "J1") (pin "14") (pinfunction "14_14") (pintype "passive"))
      (node (ref "JP9") (pin "8") (pinfunction "8_8") (pintype "passive"))
      (node (ref "U2") (pin "P82") (pinfunction "IO_L45N_1_P82") (pintype "bidirectional"))
    )
    (net (code "157") (name "TIO4") (class "Default")
      (node (ref "J1") (pin "16") (pinfunction "16_16") (pintype "passive"))
      (node (ref "JP9") (pin "9") (pinfunction "9_9") (pintype "passive"))
      (node (ref "U2") (pin "P80") (pinfunction "IO_L46N_1_P80") (pintype "bidirectional"))
    )
    (net (code "158") (name "TMISO") (class "Default")
      (node (ref "J1") (pin "7") (pinfunction "7_7") (pintype "passive"))
      (node (ref "U2") (pin "P92") (pinfunction "IO_L41N_GCLK8_1_P92") (pintype "bidirectional"))
    )
    (net (code "159") (name "TMOSI") (class "Default")
      (node (ref "J1") (pin "9") (pinfunction "9_9") (pintype "passive"))
      (node (ref "U2") (pin "P88") (pinfunction "IO_L42P_GCLK7_1_P88") (pintype "bidirectional"))
    )
    (net (code "160") (name "TMS") (class "Default")
      (node (ref "J3") (pin "7") (pinfunction "7_7") (pintype "passive"))
      (node (ref "R19") (pin "1") (pinfunction "1_1") (pintype "passive"))
      (node (ref "U1") (pin "55") (pinfunction "TMS/SWDIO_55") (pintype "bidirectional"))
    )
    (net (code "161") (name "TPDIC") (class "Default")
      (node (ref "J1") (pin "13") (pinfunction "13_13") (pintype "passive"))
      (node (ref "R36") (pin "1") (pinfunction "1_1") (pintype "passive"))
      (node (ref "U2") (pin "P83") (pinfunction "IO_L45P_1_P83") (pintype "bidirectional"))
    )
    (net (code "162") (name "TPDID") (class "Default")
      (node (ref "J1") (pin "15") (pinfunction "15_15") (pintype "passive"))
      (node (ref "R35") (pin "1") (pinfunction "1_1") (pintype "passive"))
      (node (ref "U2") (pin "P81") (pinfunction "IO_L46P_1_P81") (pintype "bidirectional"))
    )
    (net (code "163") (name "TRST") (class "Default")
      (node (ref "J1") (pin "5") (pinfunction "5_5") (pintype "passive"))
      (node (ref "U2") (pin "P94") (pinfunction "IO_L40N_GCLK10_1_P94") (pintype "bidirectional"))
    )
    (net (code "164") (name "TSCK") (class "Default")
      (node (ref "J1") (pin "11") (pinfunction "11_11") (pintype "passive"))
      (node (ref "U2") (pin "P85") (pinfunction "IO_L43P_GCLK5_1_P85") (pintype "bidirectional"))
    )
    (net (code "165") (name "TVREF") (class "Default")
      (node (ref "J1") (pin "8") (pinfunction "8_8") (pintype "passive"))
      (node (ref "JP5") (pin "3") (pinfunction "3_3") (pintype "passive"))
      (node (ref "JP9") (pin "5") (pinfunction "5_5") (pintype "passive"))
    )
    (net (code "166") (name "TXD0") (class "Default")
      (node (ref "U1") (pin "17") (pinfunction "PA18/PGMD10_17") (pintype "bidirectional"))
      (node (ref "U2") (pin "P137") (pinfunction "IO_L4N_0_P137") (pintype "bidirectional"))
    )
    (net (code "167") (name "TXD2") (class "Default")
      (node (ref "J7") (pin "6") (pinfunction "6_6") (pintype "passive"))
      (node (ref "R64") (pin "1") (pinfunction "1_1") (pintype "passive"))
      (node (ref "U1") (pin "5") (pinfunction "PA22/PGMD14_5") (pintype "bidirectional"))
      (node (ref "U2") (pin "P133") (pinfunction "IO_L34N_GCLK18_0_P133") (pintype "bidirectional"))
    )
    (net (code "168") (name "USBCK0") (class "Default")
      (node (ref "C1") (pin "1") (pinfunction "1_1") (pintype "passive"))
      (node (ref "R14") (pin "2") (pinfunction "2_2") (pintype "passive"))
      (node (ref "U2") (pin "P14") (pinfunction "IO_L44N_GCLK20_3_P14") (pintype "bidirectional"))
    )
    (net (code "169") (name "USBCK1") (class "Default")
      (node (ref "C2") (pin "1") (pinfunction "1_1") (pintype "passive"))
      (node (ref "R1") (pin "2") (pinfunction "2_2") (pintype "passive"))
      (node (ref "U2") (pin "P24") (pinfunction "IO_L41P_GCLK27_3_P24") (pintype "bidirectional"))
    )
    (net (code "170") (name "USBSPARE0") (class "Default")
      (node (ref "U1") (pin "68") (pinfunction "PB17_68") (pintype "bidirectional"))
      (node (ref "U2") (pin "P23") (pinfunction "IO_L41N_GCLK26_3_P23") (pintype "bidirectional"))
    )
    (net (code "171") (name "USBSPARE1") (class "Default")
      (node (ref "U1") (pin "67") (pinfunction "PB18_67") (pintype "bidirectional"))
      (node (ref "U2") (pin "P26") (pinfunction "IO_L37N_3_P26") (pintype "bidirectional"))
    )
    (net (code "172") (name "USBSPARE2") (class "Default")
      (node (ref "U1") (pin "63") (pinfunction "PB22_63") (pintype "bidirectional"))
      (node (ref "U2") (pin "P32") (pinfunction "IO_L2N_3_P32") (pintype "bidirectional"))
    )
    (net (code "173") (name "USB_AD0") (class "Default")
      (node (ref "U1") (pin "90") (pinfunction "PB0_90") (pintype "bidirectional"))
      (node (ref "U2") (pin "P12") (pinfunction "IO_L49P_3_P12") (pintype "bidirectional"))
    )
    (net (code "174") (name "USB_AD1") (class "Default")
      (node (ref "U1") (pin "91") (pinfunction "PB1_91") (pintype "bidirectional"))
      (node (ref "U2") (pin "P11") (pinfunction "IO_L49N_3_P11") (pintype "bidirectional"))
    )
    (net (code "175") (name "USB_AD2") (class "Default")
      (node (ref "U1") (pin "92") (pinfunction "PB2_92") (pintype "bidirectional"))
      (node (ref "U2") (pin "P10") (pinfunction "IO_L50P_3_P10") (pintype "bidirectional"))
    )
    (net (code "176") (name "USB_AD3") (class "Default")
      (node (ref "U1") (pin "7") (pinfunction "PB3_7") (pintype "bidirectional"))
      (node (ref "U2") (pin "P15") (pinfunction "IO_L44P_GCLK21_3_P15") (pintype "bidirectional"))
    )
    (net (code "177") (name "USB_AD4") (class "Default")
      (node (ref "U1") (pin "8") (pinfunction "PB4_8") (pintype "bidirectional"))
      (node (ref "U2") (pin "P16") (pinfunction "IO_L43N_GCLK22_IRDY2_3_P16") (pintype "bidirectional"))
    )
    (net (code "178") (name "USB_AD5") (class "Default")
      (node (ref "U1") (pin "97") (pinfunction "PB5_97") (pintype "bidirectional"))
      (node (ref "U2") (pin "P6") (pinfunction "IO_L52P_3_P6") (pintype "bidirectional"))
    )
    (net (code "179") (name "USB_AD6") (class "Default")
      (node (ref "U1") (pin "98") (pinfunction "PB6_98") (pintype "bidirectional"))
      (node (ref "U2") (pin "P5") (pinfunction "IO_L52N_3_P5") (pintype "bidirectional"))
    )
    (net (code "180") (name "USB_AD7") (class "Default")
      (node (ref "U1") (pin "99") (pinfunction "PB7_99") (pintype "bidirectional"))
      (node (ref "U2") (pin "P2") (pinfunction "IO_L83P_3_P2") (pintype "bidirectional"))
    )
    (net (code "181") (name "USB_AD8") (class "Default")
      (node (ref "U1") (pin "100") (pinfunction "PB8_100") (pintype "bidirectional"))
      (node (ref "U2") (pin "P1") (pinfunction "IO_L83N_VREF_3_P1") (pintype "bidirectional"))
    )
    (net (code "182") (name "USB_D0") (class "Default")
      (node (ref "U1") (pin "71") (pinfunction "PB9_71") (pintype "bidirectional"))
      (node (ref "U2") (pin "P17") (pinfunction "IO_L43P_GCLK23_3_P17") (pintype "bidirectional"))
    )
    (net (code "183") (name "USB_D1") (class "Default")
      (node (ref "U1") (pin "70") (pinfunction "PB10_70") (pintype "bidirectional"))
      (node (ref "U2") (pin "P21") (pinfunction "IO_L42N_GCLK24_3_P21") (pintype "bidirectional"))
    )
    (net (code "184") (name "USB_D2") (class "Default")
      (node (ref "U1") (pin "93") (pinfunction "PB11_93") (pintype "bidirectional"))
      (node (ref "U2") (pin "P9") (pinfunction "IO_L50N_3_P9") (pintype "bidirectional"))
    )
    (net (code "185") (name "USB_D3") (class "Default")
      (node (ref "U1") (pin "94") (pinfunction "PB12_94") (pintype "bidirectional"))
      (node (ref "U2") (pin "P8") (pinfunction "IO_L51P_3_P8") (pintype "bidirectional"))
    )
    (net (code "186") (name "USB_D4") (class "Default")
      (node (ref "U1") (pin "95") (pinfunction "PB13_95") (pintype "bidirectional"))
      (node (ref "U2") (pin "P7") (pinfunction "IO_L51N_3_P7") (pintype "bidirectional"))
    )
    (net (code "187") (name "USB_D5") (class "Default")
      (node (ref "U1") (pin "69") (pinfunction "PB14_69") (pintype "bidirectional"))
      (node (ref "U2") (pin "P22") (pinfunction "IO_L42P_GCLK25_TRDY2_3_P22") (pintype "bidirectional"))
    )
    (net (code "188") (name "USB_D6") (class "Default")
      (node (ref "U1") (pin "16") (pinfunction "PB15_16") (pintype "bidirectional"))
      (node (ref "U2") (pin "P35") (pinfunction "IO_L1P_3_P35") (pintype "bidirectional"))
    )
    (net (code "189") (name "USB_D7") (class "Default")
      (node (ref "U1") (pin "15") (pinfunction "PB16_15") (pintype "bidirectional"))
      (node (ref "U2") (pin "P34") (pinfunction "IO_L1N_VREF_3_P34") (pintype "bidirectional"))
    )
    (net (code "190") (name "VBUS") (class "Default")
      (node (ref "C39") (pin "1") (pinfunction "1_1") (pintype "passive"))
      (node (ref "C44") (pin "1") (pinfunction "1_1") (pintype "passive"))
      (node (ref "C45") (pin "1") (pinfunction "1_1") (pintype "passive"))
      (node (ref "L6") (pin "2") (pinfunction "2_2") (pintype "passive"))
      (node (ref "R33") (pin "2") (pinfunction "2_2") (pintype "passive"))
      (node (ref "U7") (pin "1") (pinfunction "IN_1") (pintype "input"))
    )
    (net (code "191") (name "VBUSDETECT") (class "Default")
      (node (ref "R33") (pin "1") (pinfunction "1_1") (pintype "passive"))
      (node (ref "R34") (pin "2") (pinfunction "2_2") (pintype "passive"))
      (node (ref "U1") (pin "6") (pinfunction "PA30_6") (pintype "bidirectional"))
    )
    (net (code "192") (name "VBUS_SWITCHED") (class "Default")
      (node (ref "C36") (pin "1") (pinfunction "1_1") (pintype "passive"))
      (node (ref "C42") (pin "1") (pinfunction "1_1") (pintype "passive"))
      (node (ref "C43") (pin "1") (pinfunction "1_1") (pintype "passive"))
      (node (ref "L4") (pin "2") (pinfunction "2_2") (pintype "passive"))
      (node (ref "U5") (pin "2") (pinfunction "RUN1_2") (pintype "input"))
      (node (ref "U5") (pin "3") (pinfunction "MODE_3") (pintype "input"))
      (node (ref "U5") (pin "7") (pinfunction "VIN_7") (pintype "input"))
    )
    (net (code "193") (name "VCCGLITCH") (class "Default")
      (node (ref "JP11") (pin "2") (pinfunction "2_2") (pintype "passive"))
      (node (ref "T4") (pin "1") (pinfunction "D_1") (pintype "passive"))
      (node (ref "U8") (pin "5") (pinfunction "D_5") (pintype "bidirectional"))
      (node (ref "U8") (pin "6") (pinfunction "D_6") (pintype "bidirectional"))
      (node (ref "U8") (pin "7") (pinfunction "D_7") (pintype "bidirectional"))
      (node (ref "U8") (pin "8") (pinfunction "D_8") (pintype "bidirectional"))
      (node (ref "X4") (pin "1") (pinfunction "1_1") (pintype "passive"))
    )
    (net (code "194") (name "VCCINT") (class "Default")
      (node (ref "C27") (pin "1") (pinfunction "1_1") (pintype "passive"))
      (node (ref "C28") (pin "1") (pinfunction "1_1") (pintype "passive"))
      (node (ref "C29") (pin "1") (pinfunction "1_1") (pintype "passive"))
      (node (ref "C30") (pin "1") (pinfunction "1_1") (pintype "passive"))
      (node (ref "C31") (pin "1") (pinfunction "1_1") (pintype "passive"))
      (node (ref "C32") (pin "1") (pinfunction "1_1") (pintype "passive"))
      (node (ref "C35") (pin "1") (pinfunction "1_1") (pintype "passive"))
      (node (ref "L3") (pin "2") (pinfunction "2_2") (pintype "passive"))
      (node (ref "R30") (pin "1") (pinfunction "1_1") (pintype "passive"))
      (node (ref "U2") (pin "P128") (pinfunction "VCCINT_P128") (pintype "input"))
      (node (ref "U2") (pin "P19") (pinfunction "VCCINT_P19") (pintype "input"))
      (node (ref "U2") (pin "P28") (pinfunction "VCCINT_P28") (pintype "input"))
      (node (ref "U2") (pin "P52") (pinfunction "VCCINT_P52") (pintype "input"))
      (node (ref "U2") (pin "P89") (pinfunction "VCCINT_P89") (pintype "input"))
    )
    (net (code "195") (name "VCCIO") (class "Default")
      (node (ref "C114") (pin "2") (pinfunction "2_2") (pintype "passive"))
      (node (ref "C20") (pin "1") (pinfunction "1_1") (pintype "passive"))
      (node (ref "C22") (pin "1") (pinfunction "1_1") (pintype "passive"))
      (node (ref "C23") (pin "1") (pinfunction "1_1") (pintype "passive"))
      (node (ref "C24") (pin "1") (pinfunction "1_1") (pintype "passive"))
      (node (ref "C25") (pin "1") (pinfunction "1_1") (pintype "passive"))
      (node (ref "C26") (pin "1") (pinfunction "1_1") (pintype "passive"))
      (node (ref "C34") (pin "1") (pinfunction "1_1") (pintype "passive"))
      (node (ref "C49") (pin "2") (pinfunction "2_2") (pintype "passive"))
      (node (ref "C52") (pin "1") (pinfunction "1_1") (pintype "passive"))
      (node (ref "C53") (pin "1") (pinfunction "1_1") (pintype "passive"))
      (node (ref "C54") (pin "1") (pinfunction "1_1") (pintype "passive"))
      (node (ref "C55") (pin "1") (pinfunction "1_1") (pintype "passive"))
      (node (ref "C56") (pin "1") (pinfunction "1_1") (pintype "passive"))
      (node (ref "C57") (pin "1") (pinfunction "1_1") (pintype "passive"))
      (node (ref "C58") (pin "1") (pinfunction "1_1") (pintype "passive"))
      (node (ref "C59") (pin "1") (pinfunction "1_1") (pintype "passive"))
      (node (ref "C60") (pin "1") (pinfunction "1_1") (pintype "passive"))
      (node (ref "C61") (pin "1") (pinfunction "1_1") (pintype "passive"))
      (node (ref "C62") (pin "1") (pinfunction "1_1") (pintype "passive"))
      (node (ref "C83") (pin "2") (pinfunction "2_2") (pintype "passive"))
      (node (ref "C84") (pin "2") (pinfunction "2_2") (pintype "passive"))
      (node (ref "J4") (pin "1") (pinfunction "+V_1") (pintype "passive"))
      (node (ref "JP5") (pin "1") (pinfunction "1_1") (pintype "passive"))
      (node (ref "L2") (pin "2") (pinfunction "2_2") (pintype "passive"))
      (node (ref "L9") (pin "1") (pinfunction "1_1") (pintype "passive"))
      (node (ref "R11") (pin "2") (pinfunction "2_2") (pintype "passive"))
      (node (ref "R12") (pin "2") (pinfunction "2_2") (pintype "passive"))
      (node (ref "R25") (pin "1") (pinfunction "1_1") (pintype "passive"))
      (node (ref "R3") (pin "1") (pinfunction "1_1") (pintype "passive"))
      (node (ref "R59") (pin "1") (pinfunction "1_1") (pintype "passive"))
      (node (ref "R68") (pin "2") (pinfunction "2_2") (pintype "passive"))
      (node (ref "R69") (pin "1") (pinfunction "1_1") (pintype "passive"))
      (node (ref "R7") (pin "1") (pinfunction "1_1") (pintype "passive"))
      (node (ref "R70") (pin "1") (pinfunction "1_1") (pintype "passive"))
      (node (ref "R9") (pin "2") (pinfunction "2_2") (pintype "passive"))
      (node (ref "SJ6") (pin "1") (pinfunction "1_1") (pintype "passive"))
      (node (ref "T3") (pin "2") (pinfunction "S_2") (pintype "passive"))
      (node (ref "U2") (pin "P122") (pinfunction "VCCO_0_P122") (pintype "input"))
      (node (ref "U2") (pin "P125") (pinfunction "VCCO_0_P125") (pintype "input"))
      (node (ref "U2") (pin "P129") (pinfunction "VCCAUX_P129") (pintype "input"))
      (node (ref "U2") (pin "P135") (pinfunction "VCCO_0_P135") (pintype "input"))
      (node (ref "U2") (pin "P18") (pinfunction "VCCO_3_P18") (pintype "input"))
      (node (ref "U2") (pin "P20") (pinfunction "VCCAUX_P20") (pintype "input"))
      (node (ref "U2") (pin "P31") (pinfunction "VCCO_3_P31") (pintype "input"))
      (node (ref "U2") (pin "P36") (pinfunction "VCCAUX_P36") (pintype "input"))
      (node (ref "U2") (pin "P4") (pinfunction "VCCO_3_P4") (pintype "input"))
      (node (ref "U2") (pin "P42") (pinfunction "VCCO_2_P42") (pintype "input"))
      (node (ref "U2") (pin "P53") (pinfunction "VCCAUX_P53") (pintype "input"))
      (node (ref "U2") (pin "P63") (pinfunction "VCCO_2_P63") (pintype "input"))
      (node (ref "U2") (pin "P90") (pinfunction "VCCAUX_P90") (pintype "input"))
      (node (ref "U4") (pin "24") (pinfunction "DRVDD_24") (pintype "bidirectional"))
      (node (ref "U5") (pin "9") (pinfunction "RUN2_9") (pintype "input"))
      (node (ref "U9") (pin "3") (pinfunction "WP_3") (pintype "bidirectional"))
      (node (ref "U9") (pin "7") (pinfunction "HOLD_7") (pintype "bidirectional"))
      (node (ref "U9") (pin "8") (pinfunction "VCC_8") (pintype "bidirectional"))
    )
    (net (code "196") (name "VCCTIO_SWITCHED") (class "Default")
      (node (ref "J1") (pin "18") (pinfunction "18_18") (pintype "passive"))
      (node (ref "J1") (pin "3") (pinfunction "3_3") (pintype "passive"))
      (node (ref "T3") (pin "1") (pinfunction "D_1") (pintype "passive"))
    )
    (net (code "197") (name "VGA_GAIN") (class "Default")
      (node (ref "R53") (pin "1") (pinfunction "1_1") (pintype "passive"))
      (node (ref "U2") (pin "P62") (pinfunction "IO_L12P_D1_MISO2_2_P62") (pintype "bidirectional"))
    )
    (net (code "198") (name "VGA_HILOW") (class "Default")
      (node (ref "U2") (pin "P61") (pinfunction "IO_L12N_D2_MISO3_2_P61") (pintype "bidirectional"))
      (node (ref "U3") (pin "13") (pinfunction "HILO_13") (pintype "bidirectional"))
    )
    (net (code "199") (name "unconnected-(D1-CA-Pad1)") (class "Default")
      (node (ref "D1") (pin "1") (pinfunction "CA_1") (pintype "passive"))
    )
    (net (code "200") (name "unconnected-(H1-MOUNT-PadB2,8)") (class "Default")
      (node (ref "H1") (pin "B2,8") (pinfunction "MOUNT_B2,8") (pintype "passive"))
    )
    (net (code "201") (name "unconnected-(H2-MOUNT-PadB2,8)") (class "Default")
      (node (ref "H2") (pin "B2,8") (pinfunction "MOUNT_B2,8") (pintype "passive"))
    )
    (net (code "202") (name "unconnected-(H3-MOUNT-PadB2,8)") (class "Default")
      (node (ref "H3") (pin "B2,8") (pinfunction "MOUNT_B2,8") (pintype "passive"))
    )
    (net (code "203") (name "unconnected-(H4-MOUNT-PadB2,8)") (class "Default")
      (node (ref "H4") (pin "B2,8") (pinfunction "MOUNT_B2,8") (pintype "passive"))
    )
    (net (code "204") (name "unconnected-(J1-Pad1)") (class "Default")
      (node (ref "J1") (pin "1") (pinfunction "1_1") (pintype "passive"))
    )
    (net (code "205") (name "unconnected-(J1-Pad20)") (class "Default")
      (node (ref "J1") (pin "20") (pinfunction "20_20") (pintype "passive"))
    )
    (net (code "206") (name "unconnected-(J3-Pad17)") (class "Default")
      (node (ref "J3") (pin "17") (pinfunction "17_17") (pintype "passive"))
    )
    (net (code "207") (name "unconnected-(J3-Pad19)") (class "Default")
      (node (ref "J3") (pin "19") (pinfunction "19_19") (pintype "passive"))
    )
    (net (code "208") (name "unconnected-(J8-ID-Pad4)") (class "Default")
      (node (ref "J8") (pin "4") (pinfunction "ID_4") (pintype "bidirectional"))
    )
    (net (code "209") (name "unconnected-(U1-PA26-Pad25)") (class "Default")
      (node (ref "U1") (pin "25") (pinfunction "PA26_25") (pintype "bidirectional"))
    )
    (net (code "210") (name "unconnected-(U1-PA28-Pad84)") (class "Default")
      (node (ref "U1") (pin "84") (pinfunction "PA28_84") (pintype "bidirectional"))
    )
    (net (code "211") (name "unconnected-(U1-PA31-Pad86)") (class "Default")
      (node (ref "U1") (pin "86") (pinfunction "PA31_86") (pintype "bidirectional"))
    )
    (net (code "212") (name "unconnected-(U1-XIN32-Pad50)") (class "Default")
      (node (ref "U1") (pin "50") (pinfunction "XIN32_50") (pintype "input"))
    )
    (net (code "213") (name "unconnected-(U1-XOUT32-Pad49)") (class "Default")
      (node (ref "U1") (pin "49") (pinfunction "XOUT32_49") (pintype "output"))
    )
    (net (code "214") (name "unconnected-(U2B-IO_L1N_VREF_1-PadP104)") (class "Default")
      (node (ref "U2") (pin "P104") (pinfunction "IO_L1N_VREF_1_P104") (pintype "bidirectional"))
    )
    (net (code "215") (name "unconnected-(U2B-IO_L47N_1-PadP78)") (class "Default")
      (node (ref "U2") (pin "P78") (pinfunction "IO_L47N_1_P78") (pintype "bidirectional"))
    )
    (net (code "216") (name "unconnected-(U2B-IO_L47P_1-PadP79)") (class "Default")
      (node (ref "U2") (pin "P79") (pinfunction "IO_L47P_1_P79") (pintype "bidirectional"))
    )
    (net (code "217") (name "unconnected-(U2B-IO_L74N_DOUT_BUSY_1-PadP74)") (class "Default")
      (node (ref "U2") (pin "P74") (pinfunction "IO_L74N_DOUT_BUSY_1_P74") (pintype "bidirectional"))
    )
    (net (code "218") (name "unconnected-(U2B-IO_L74P_AWAKE_1-PadP75)") (class "Default")
      (node (ref "U2") (pin "P75") (pinfunction "IO_L74P_AWAKE_1_P75") (pintype "bidirectional"))
    )
    (net (code "219") (name "unconnected-(U2C-CMPCS_B_2-PadP72)") (class "Default")
      (node (ref "U2") (pin "P72") (pinfunction "CMPCS_B_2_P72") (pintype "bidirectional"))
    )
    (net (code "220") (name "unconnected-(U2C-IO_L31P_GCLK31_D14_2-PadP51)") (class "Default")
      (node (ref "U2") (pin "P51") (pinfunction "IO_L31P_GCLK31_D14_2_P51") (pintype "bidirectional"))
    )
    (net (code "221") (name "~{TIOVCC_ON}") (class "Default")
      (node (ref "R77") (pin "2") (pinfunction "2_2") (pintype "passive"))
      (node (ref "T3") (pin "3") (pinfunction "G_3") (pintype "passive"))
      (node (ref "U2") (pin "P121") (pinfunction "IO_L62P_0_P121") (pintype "bidirectional"))
    )
    (net (code "222") (name "~{USBALE}") (class "Default")
      (node (ref "U1") (pin "64") (pinfunction "PB21_64") (pintype "bidirectional"))
      (node (ref "U2") (pin "P30") (pinfunction "IO_L36P_3_P30") (pintype "bidirectional"))
    )
    (net (code "223") (name "~{USBCE}") (class "Default")
      (node (ref "U1") (pin "65") (pinfunction "PB20_65") (pintype "bidirectional"))
      (node (ref "U2") (pin "P29") (pinfunction "IO_L36N_3_P29") (pintype "bidirectional"))
    )
    (net (code "224") (name "~{USBRD}") (class "Default")
      (node (ref "U1") (pin "66") (pinfunction "PB19_66") (pintype "bidirectional"))
      (node (ref "U2") (pin "P27") (pinfunction "IO_L37P_3_P27") (pintype "bidirectional"))
    )
    (net (code "225") (name "~{USBWR}") (class "Default")
      (node (ref "U1") (pin "62") (pinfunction "PB23_62") (pintype "bidirectional"))
      (node (ref "U2") (pin "P33") (pinfunction "IO_L2P_3_P33") (pintype "bidirectional"))
    )
  )
)
